# PhantomDriver_ER150D.net
KiCad netlist of a schematic drawn in EAGLE
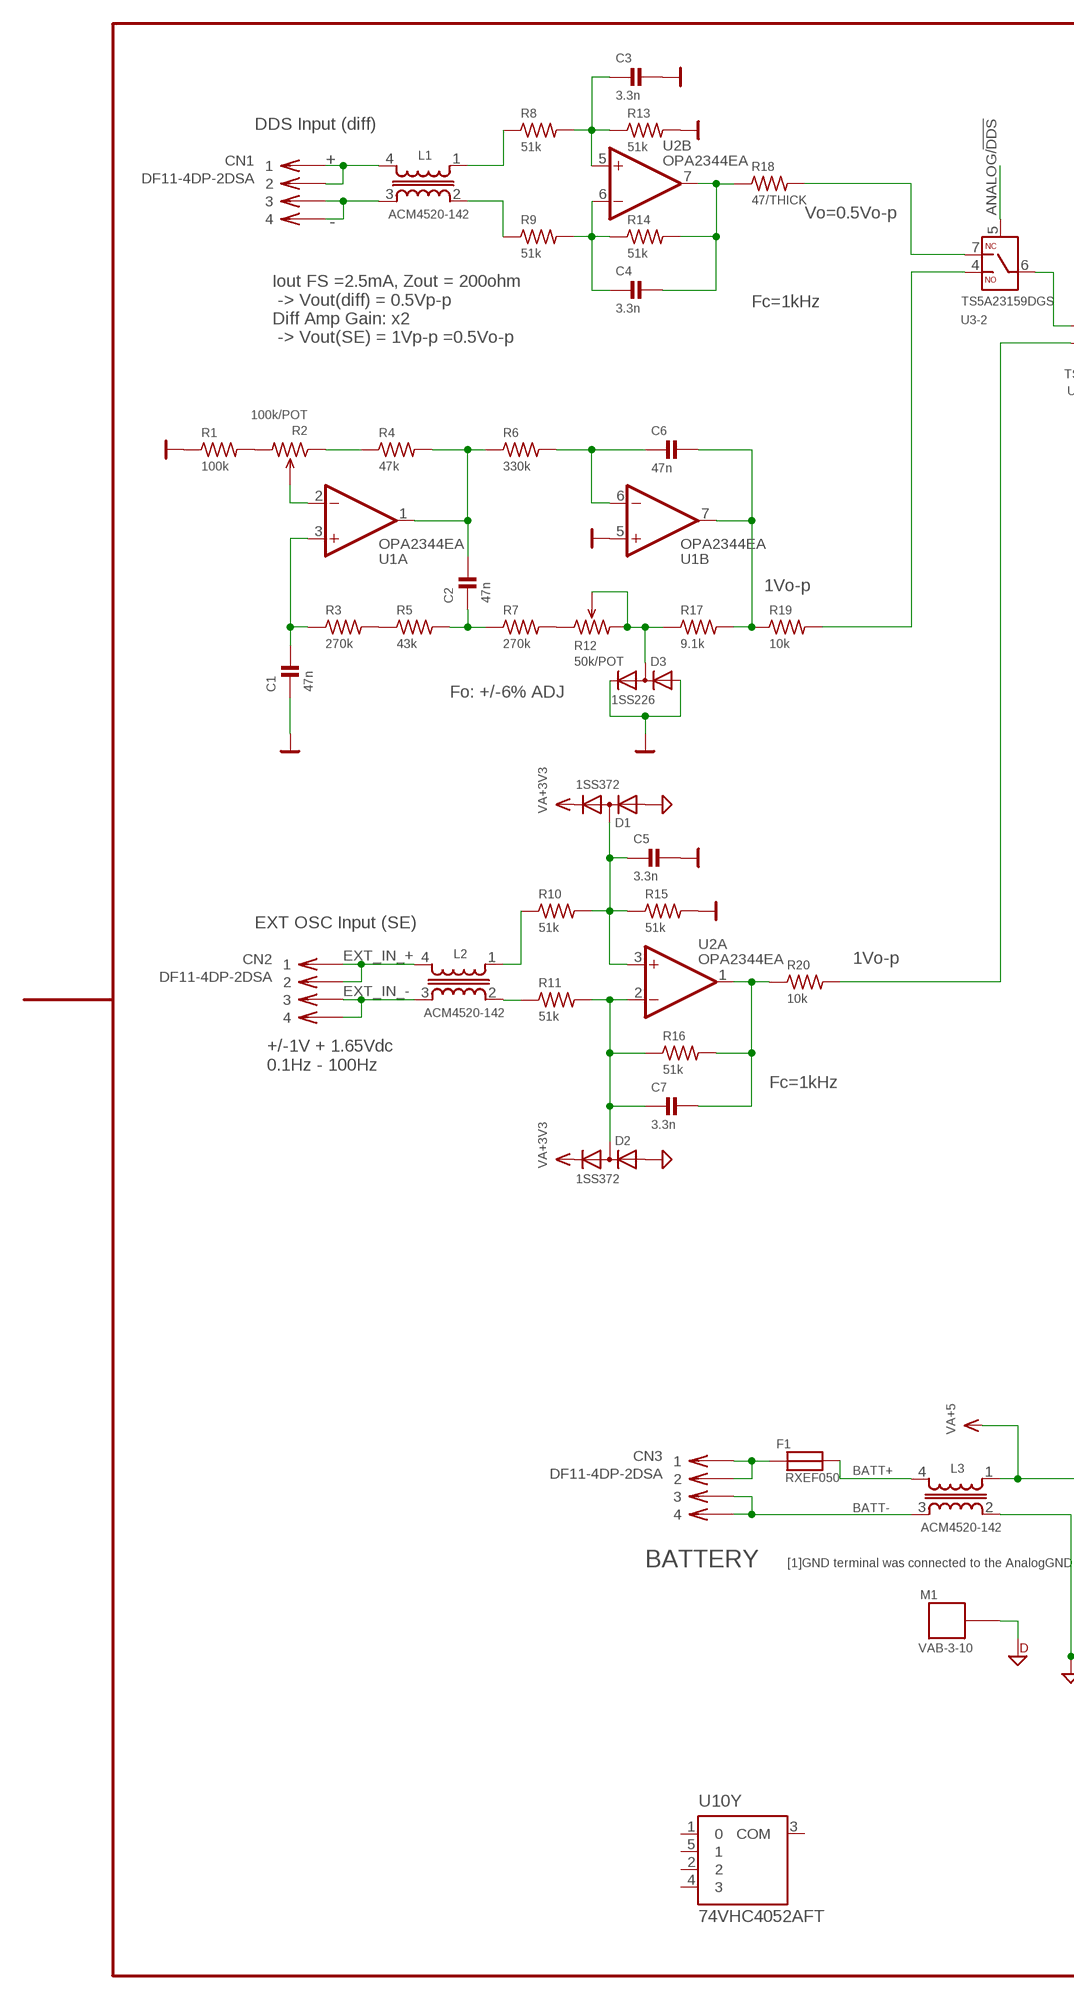
[diagram p0: schematic, sheet 1, part 1 of 2]
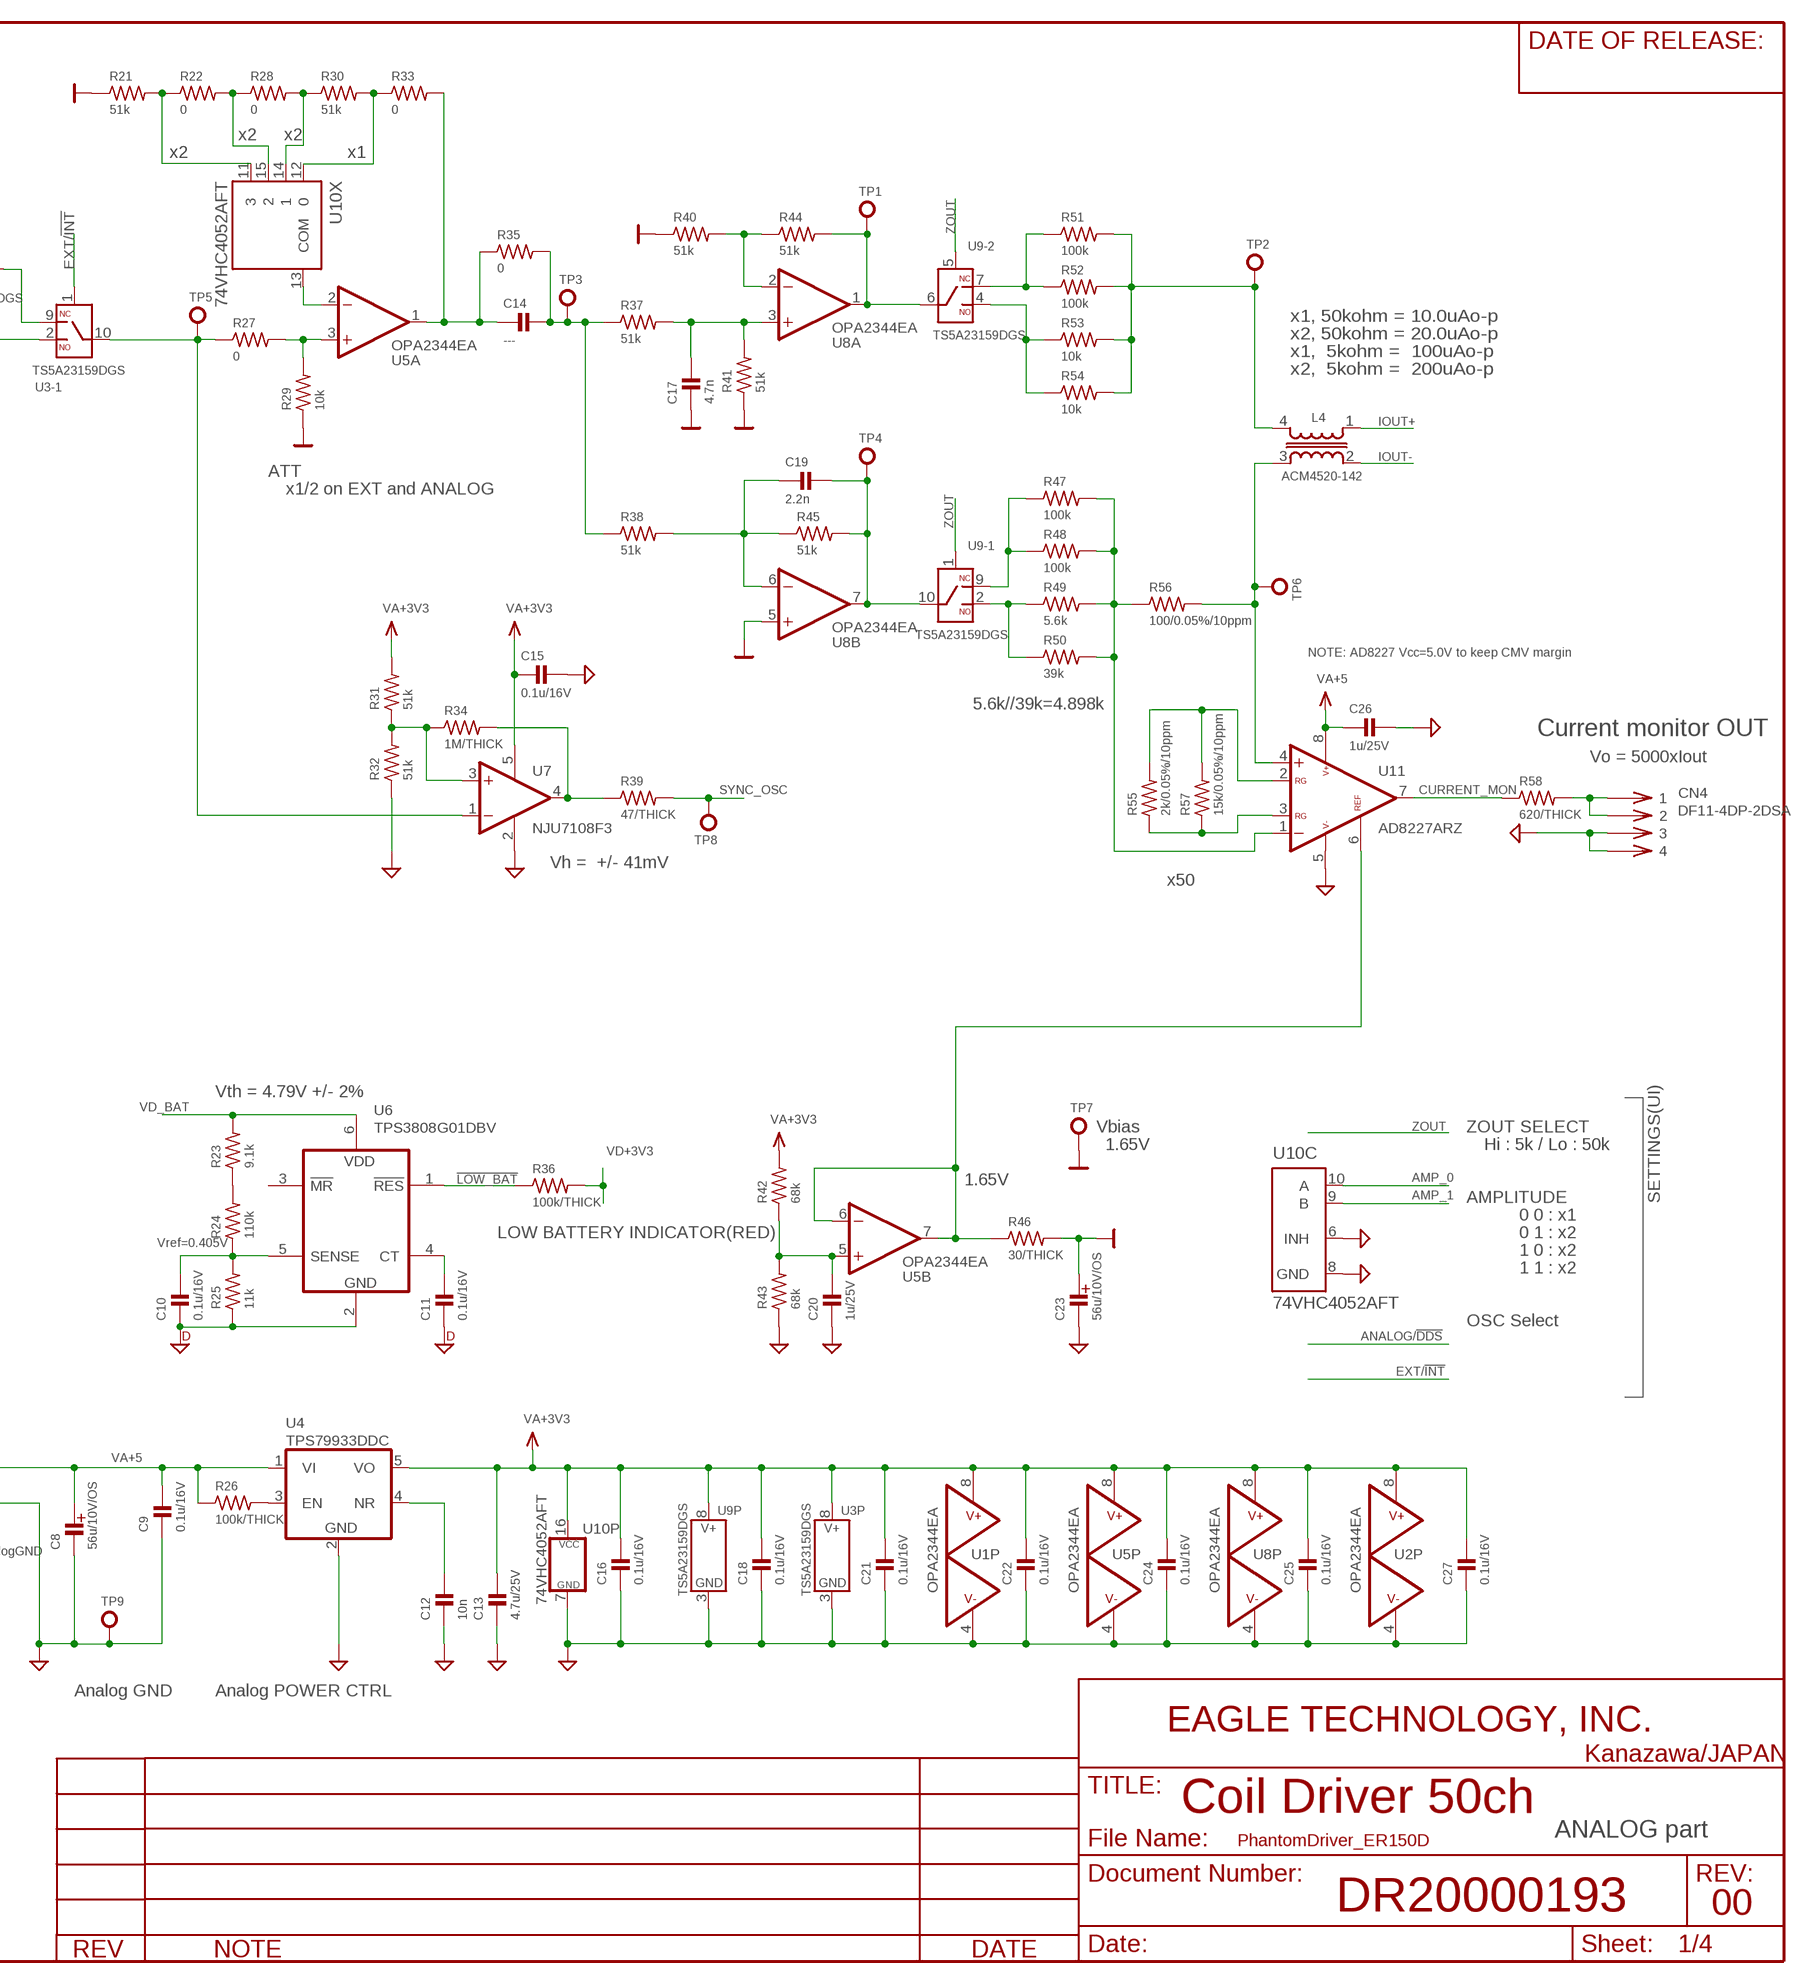
[diagram p1: schematic, sheet 1, part 2 of 2]
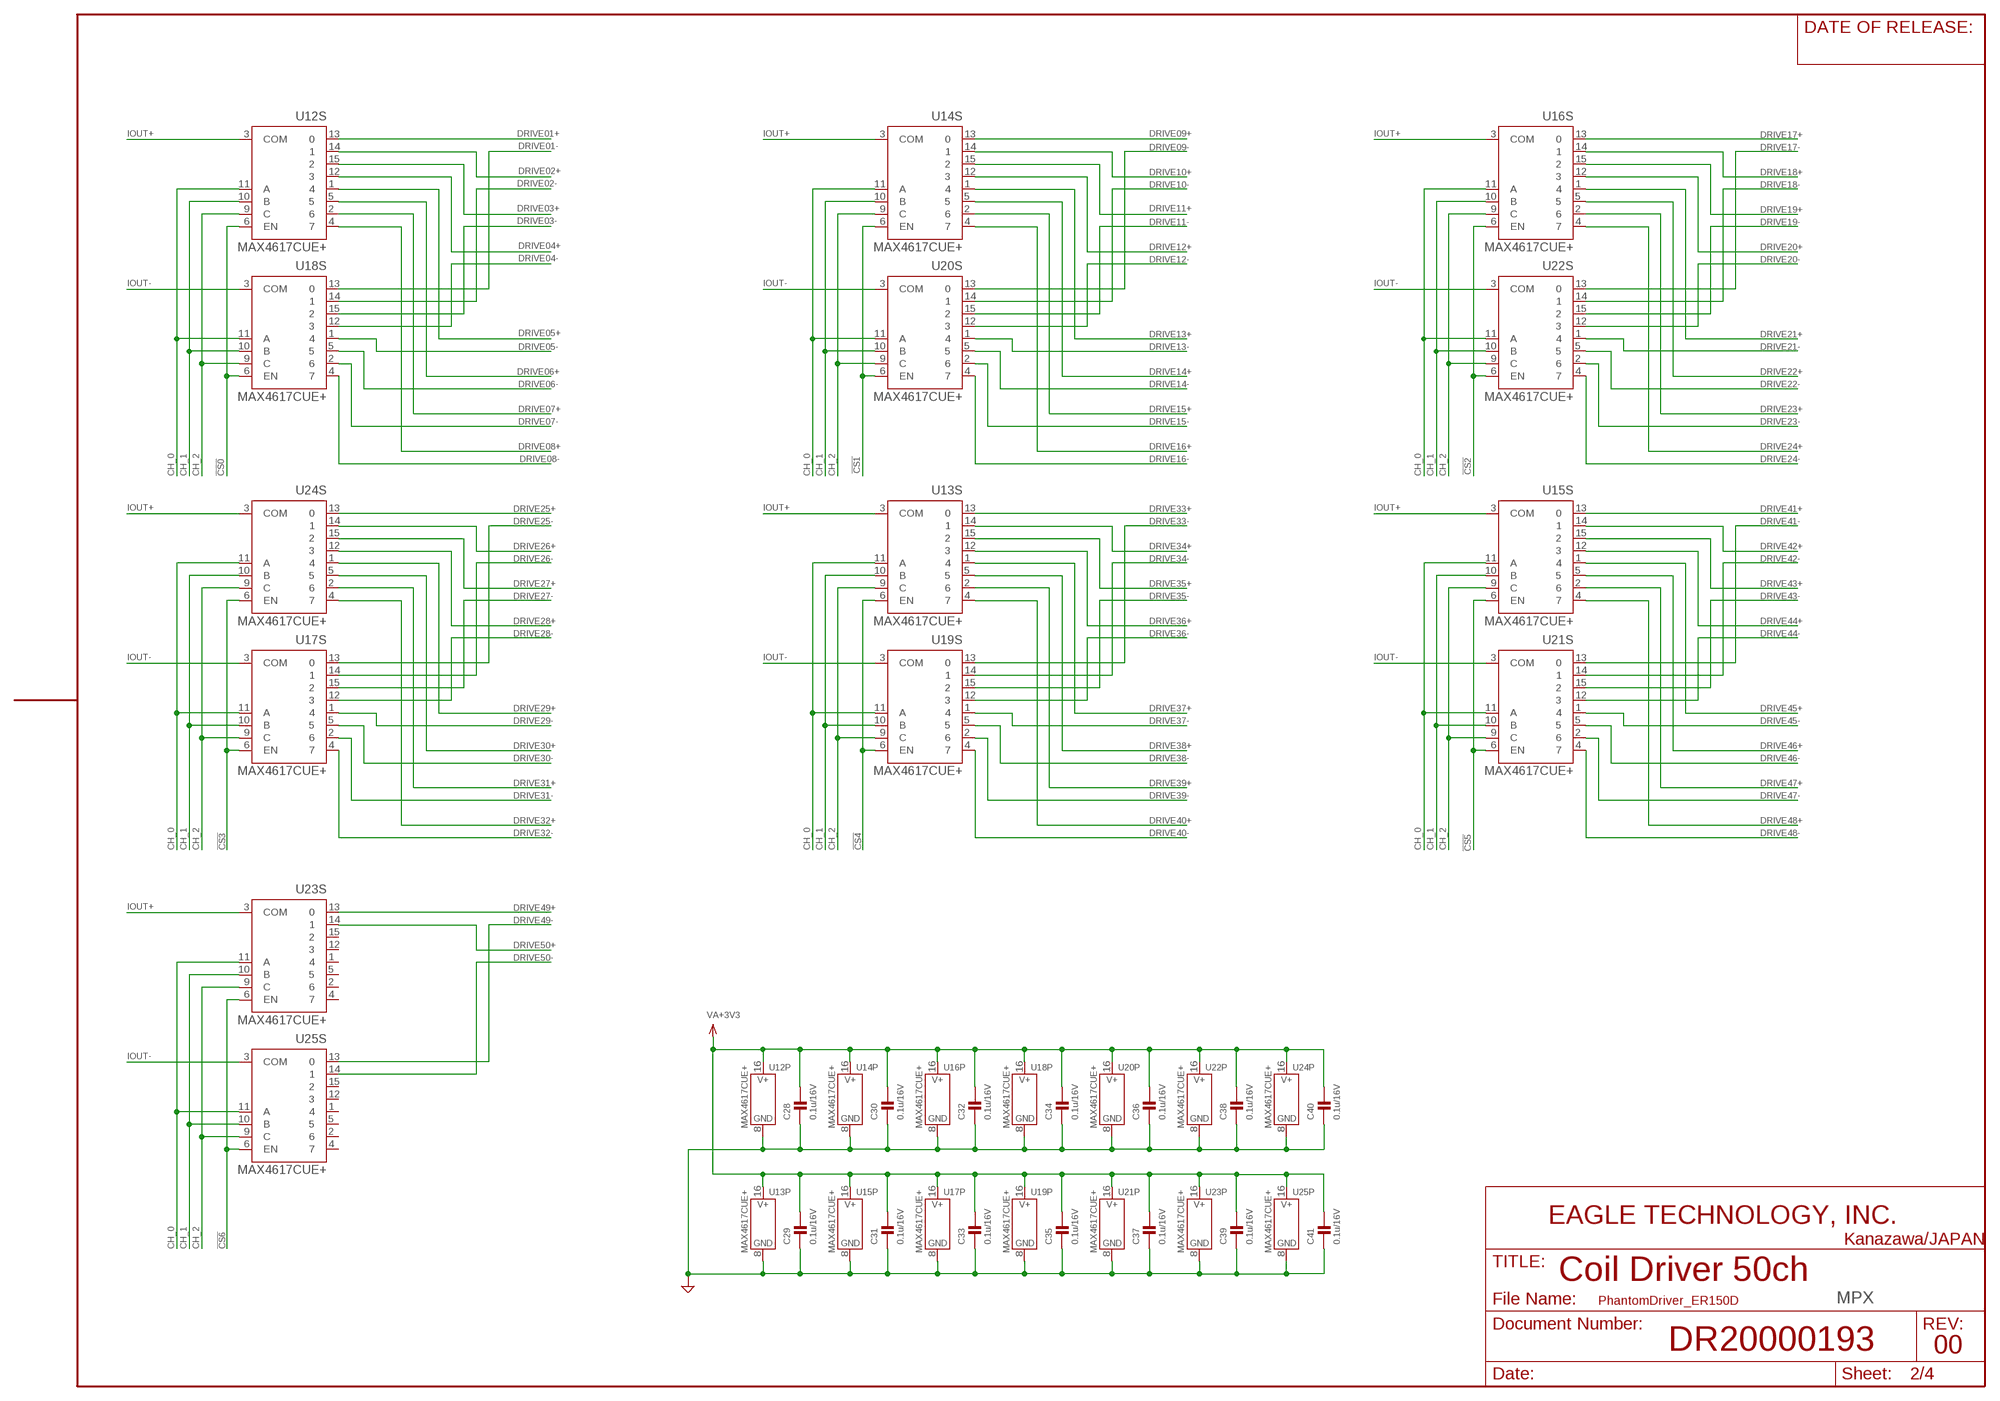
[diagram p2: schematic, sheet 2]
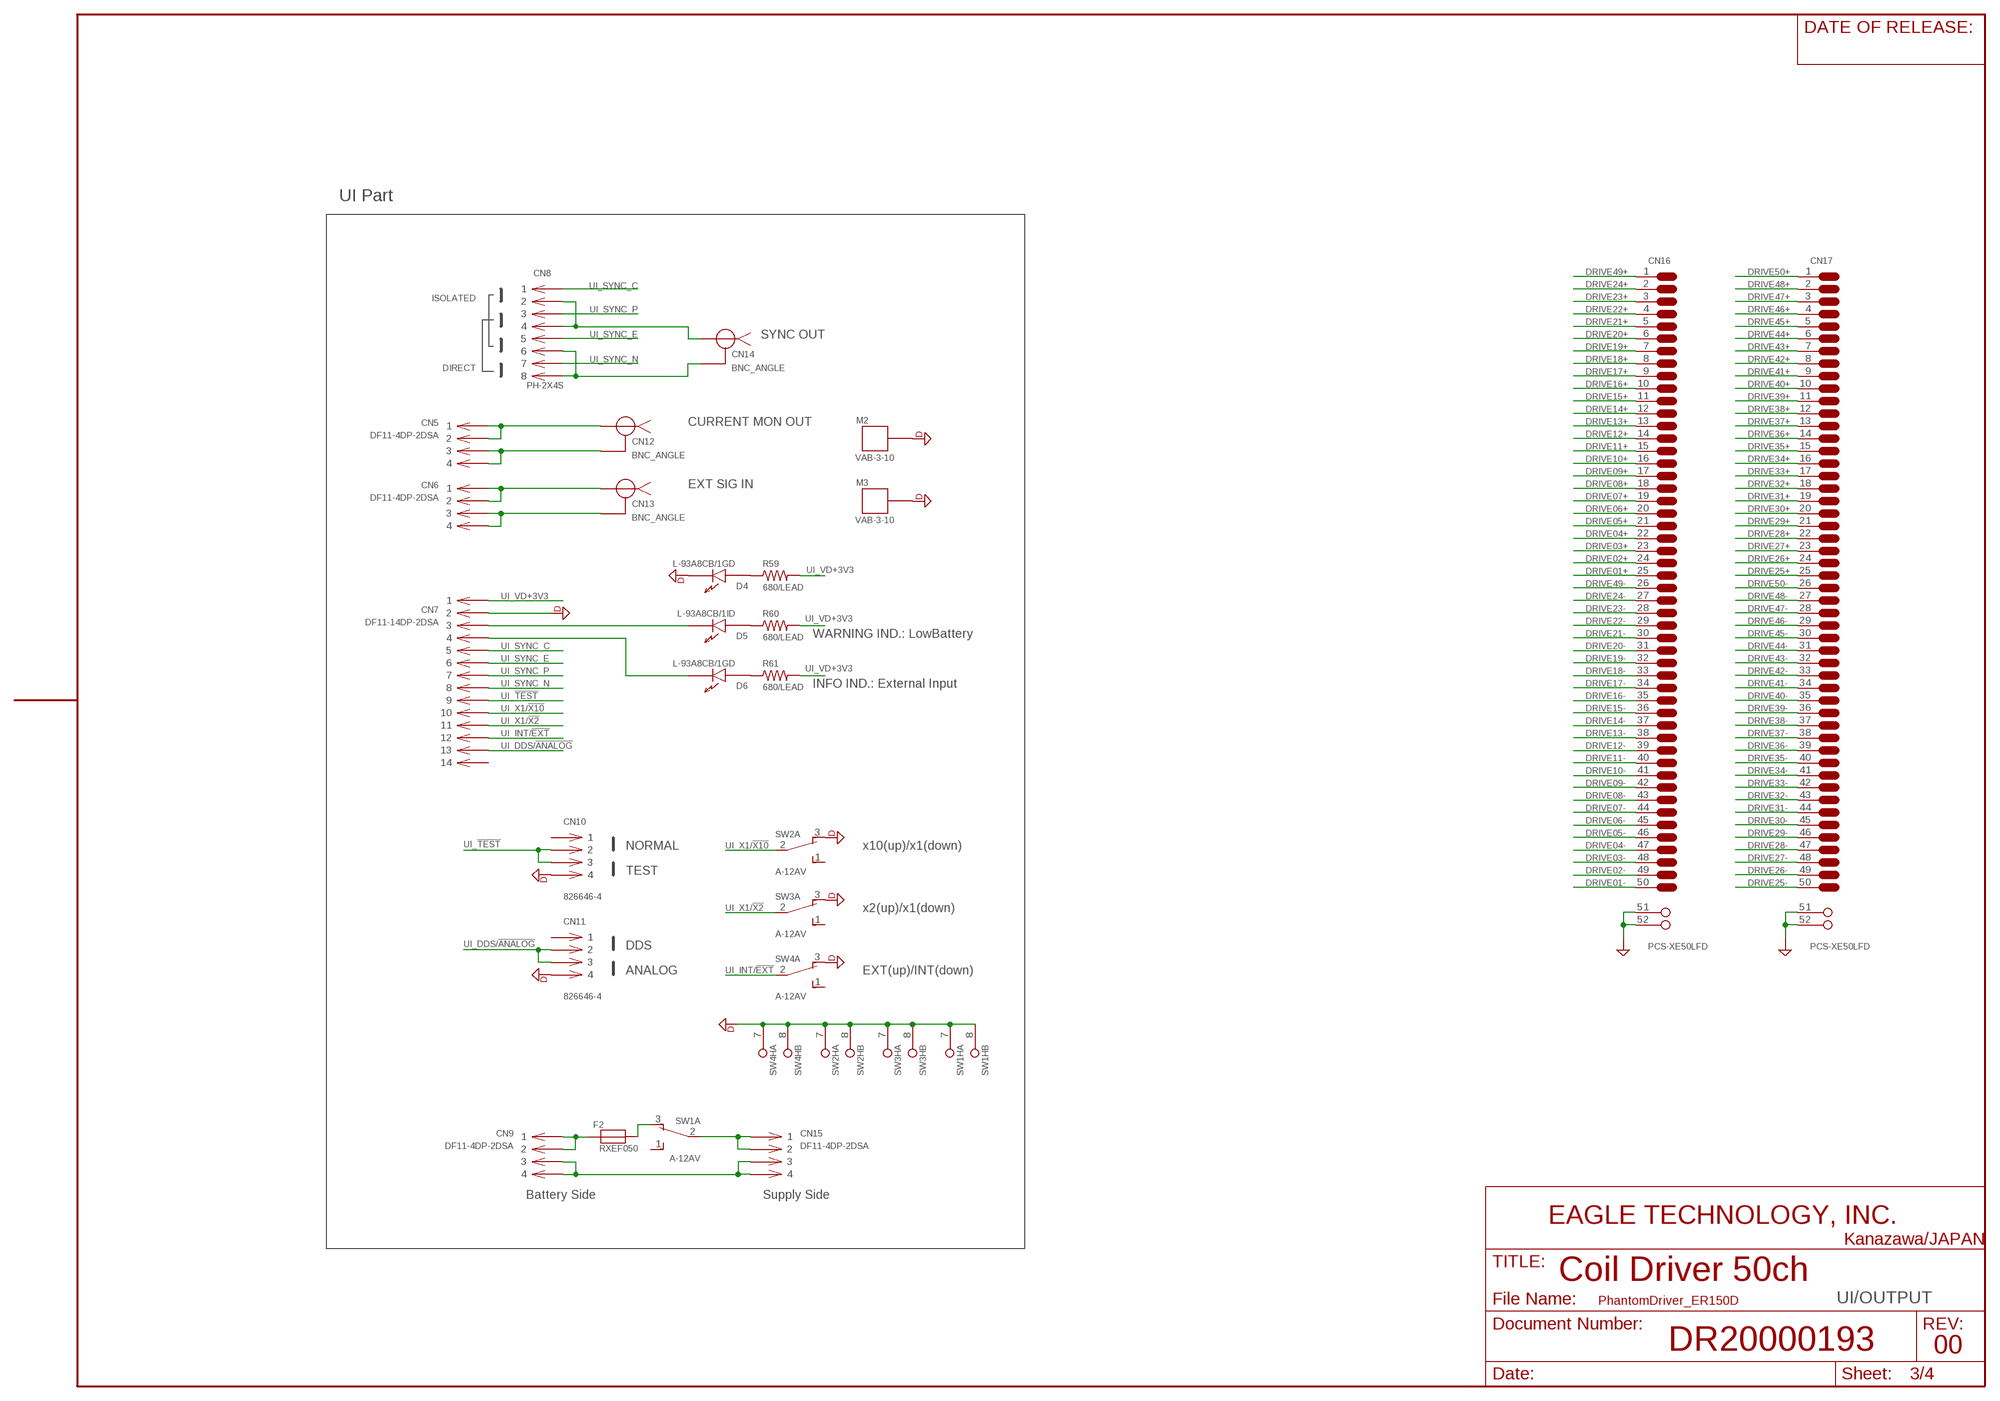
[diagram p3: schematic, sheet 3]
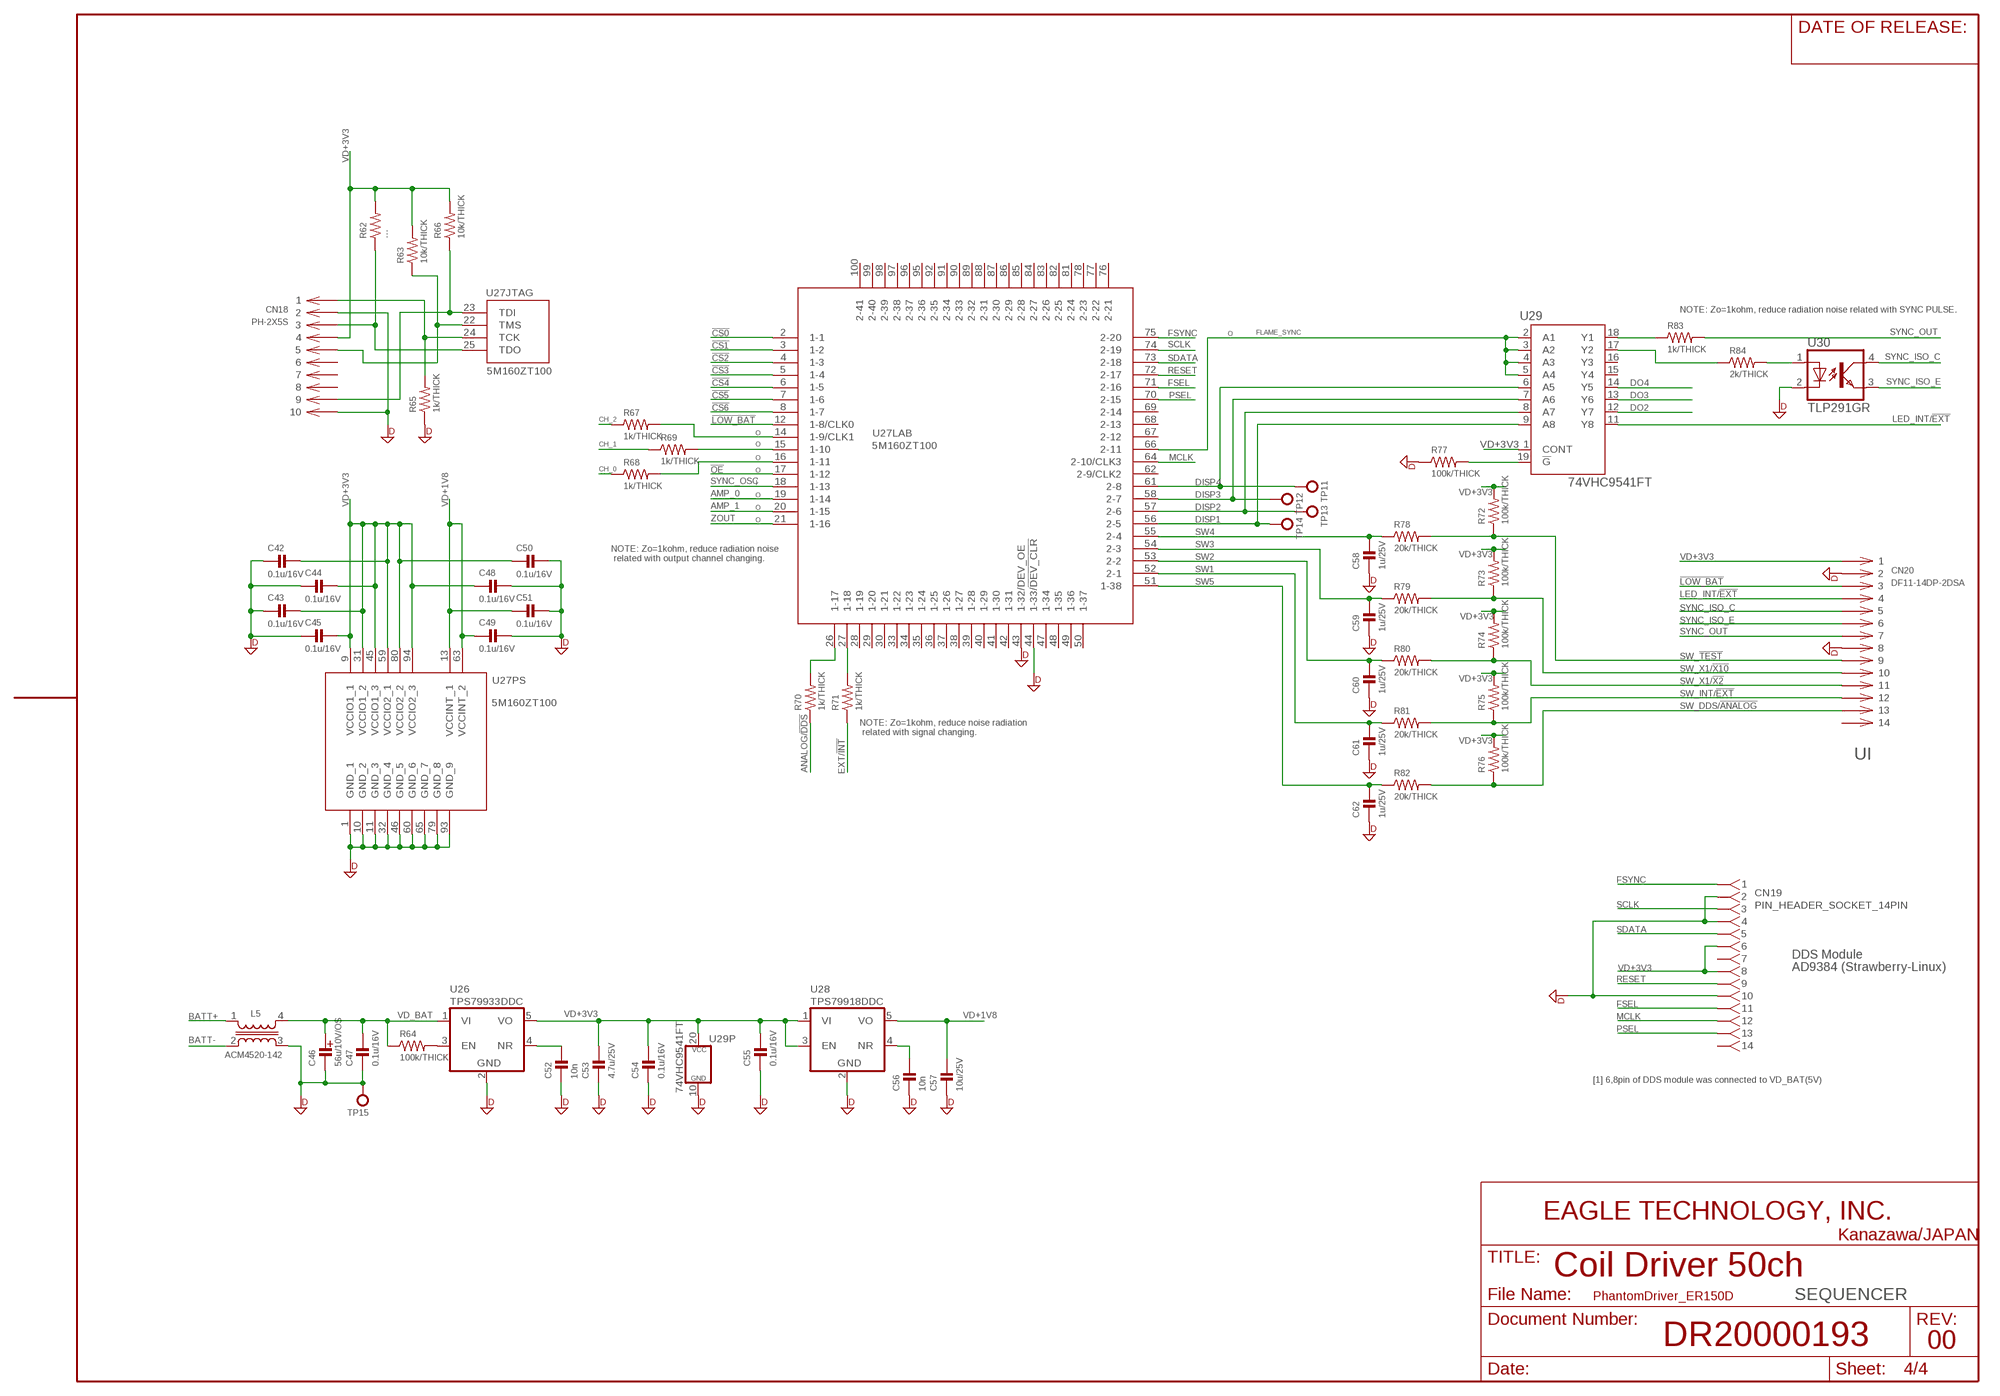
[diagram p4: schematic, sheet 4]

(export (version "E")
  (design (tool "Eeschema 10.0.6"))
  (components
    (comp (ref "C42")
      (value "0.1u/16V")
      (footprint "eagle-import:CM1005")
      (libsource (lib "eagle-import") (part "CSMD1.0X0.5MM"))
    )
    (comp (ref "C43")
      (value "0.1u/16V")
      (footprint "eagle-import:CM1005")
      (libsource (lib "eagle-import") (part "CSMD1.0X0.5MM"))
    )
    (comp (ref "C44")
      (value "0.1u/16V")
      (footprint "eagle-import:CM1005")
      (libsource (lib "eagle-import") (part "CSMD1.0X0.5MM"))
    )
    (comp (ref "C45")
      (value "0.1u/16V")
      (footprint "eagle-import:CM1005")
      (libsource (lib "eagle-import") (part "CSMD1.0X0.5MM"))
    )
    (comp (ref "C46")
      (value "56u/10V/OS")
      (footprint "eagle-import:PHI_6.3")
      (libsource (lib "eagle-import") (part "C_POL6.3-2.5MM"))
    )
    (comp (ref "C47")
      (value "0.1u/16V")
      (footprint "eagle-import:CM1005")
      (libsource (lib "eagle-import") (part "CSMD1.0X0.5MM"))
    )
    (comp (ref "C48")
      (value "0.1u/16V")
      (footprint "eagle-import:CM1005")
      (libsource (lib "eagle-import") (part "CSMD1.0X0.5MM"))
    )
    (comp (ref "C49")
      (value "0.1u/16V")
      (footprint "eagle-import:CM1005")
      (libsource (lib "eagle-import") (part "CSMD1.0X0.5MM"))
    )
    (comp (ref "C50")
      (value "0.1u/16V")
      (footprint "eagle-import:CM1005")
      (libsource (lib "eagle-import") (part "CSMD1.0X0.5MM"))
    )
    (comp (ref "C51")
      (value "0.1u/16V")
      (footprint "eagle-import:CM1005")
      (libsource (lib "eagle-import") (part "CSMD1.0X0.5MM"))
    )
    (comp (ref "C52")
      (value "10n")
      (footprint "eagle-import:CM2012")
      (libsource (lib "eagle-import") (part "CSMD2.0X1.2MM"))
    )
    (comp (ref "C53")
      (value "4.7u/25V")
      (footprint "eagle-import:CM2012")
      (libsource (lib "eagle-import") (part "CSMD2.0X1.2MM"))
    )
    (comp (ref "C54")
      (value "0.1u/16V")
      (footprint "eagle-import:CM1005")
      (libsource (lib "eagle-import") (part "CSMD1.0X0.5MM"))
    )
    (comp (ref "C55")
      (value "0.1u/16V")
      (footprint "eagle-import:CM1005")
      (libsource (lib "eagle-import") (part "CSMD1.0X0.5MM"))
    )
    (comp (ref "C56")
      (value "10n")
      (footprint "eagle-import:CM2012")
      (libsource (lib "eagle-import") (part "CSMD2.0X1.2MM"))
    )
    (comp (ref "C57")
      (value "10u/25V")
      (footprint "eagle-import:CM3216")
      (libsource (lib "eagle-import") (part "CSMD3.2X1.6MM"))
    )
    (comp (ref "C58")
      (value "1u/25V")
      (footprint "eagle-import:CM1608")
      (libsource (lib "eagle-import") (part "CSMD1.6X0.8MM"))
    )
    (comp (ref "C59")
      (value "1u/25V")
      (footprint "eagle-import:CM1608")
      (libsource (lib "eagle-import") (part "CSMD1.6X0.8MM"))
    )
    (comp (ref "C60")
      (value "1u/25V")
      (footprint "eagle-import:CM1608")
      (libsource (lib "eagle-import") (part "CSMD1.6X0.8MM"))
    )
    (comp (ref "C61")
      (value "1u/25V")
      (footprint "eagle-import:CM1608")
      (libsource (lib "eagle-import") (part "CSMD1.6X0.8MM"))
    )
    (comp (ref "C62")
      (value "1u/25V")
      (footprint "eagle-import:CM1608")
      (libsource (lib "eagle-import") (part "CSMD1.6X0.8MM"))
    )
    (comp (ref "CN18")
      (value "PH-2X5S")
      (footprint "eagle-import:PIN_HEADER_10PIN")
      (libsource (lib "eagle-import") (part "PIN_HEADER_10PIN"))
    )
    (comp (ref "CN19")
      (value "PIN_HEADER_SOCKET_14PIN")
      (footprint "eagle-import:PIN_HEADER_SOCKET_14PIN")
      (libsource (lib "eagle-import") (part "PIN_HEADER_SOCKET_14PIN"))
    )
    (comp (ref "CN20")
      (value "DF11-14DP-2DSA")
      (footprint "eagle-import:DF11-14DP-2DSA")
      (libsource (lib "eagle-import") (part "DF11-14DP-2DSA"))
    )
    (comp (ref "L5")
      (value "ACM4520-142")
      (footprint "eagle-import:ACM4520")
      (libsource (lib "eagle-import") (part "ACM4520-142"))
    )
    (comp (ref "R62")
      (value "---")
      (footprint "eagle-import:RM1608")
      (libsource (lib "eagle-import") (part "RSMD1.6X0.8MM"))
    )
    (comp (ref "R63")
      (value "10k/THICK")
      (footprint "eagle-import:RM1608")
      (libsource (lib "eagle-import") (part "RSMD1.6X0.8MM"))
    )
    (comp (ref "R64")
      (value "100k/THICK")
      (footprint "eagle-import:RM1608")
      (libsource (lib "eagle-import") (part "RSMD1.6X0.8MM"))
    )
    (comp (ref "R65")
      (value "1k/THICK")
      (footprint "eagle-import:RM1608")
      (libsource (lib "eagle-import") (part "RSMD1.6X0.8MM"))
    )
    (comp (ref "R66")
      (value "10k/THICK")
      (footprint "eagle-import:RM1608")
      (libsource (lib "eagle-import") (part "RSMD1.6X0.8MM"))
    )
    (comp (ref "R67")
      (value "1k/THICK")
      (footprint "eagle-import:RM1608")
      (libsource (lib "eagle-import") (part "RSMD1.6X0.8MM"))
    )
    (comp (ref "R68")
      (value "1k/THICK")
      (footprint "eagle-import:RM1608")
      (libsource (lib "eagle-import") (part "RSMD1.6X0.8MM"))
    )
    (comp (ref "R69")
      (value "1k/THICK")
      (footprint "eagle-import:RM1608")
      (libsource (lib "eagle-import") (part "RSMD1.6X0.8MM"))
    )
    (comp (ref "R70")
      (value "1k/THICK")
      (footprint "eagle-import:RM1608")
      (libsource (lib "eagle-import") (part "RSMD1.6X0.8MM"))
    )
    (comp (ref "R71")
      (value "1k/THICK")
      (footprint "eagle-import:RM1608")
      (libsource (lib "eagle-import") (part "RSMD1.6X0.8MM"))
    )
    (comp (ref "R72")
      (value "100k/THICK")
      (footprint "eagle-import:RM1608")
      (libsource (lib "eagle-import") (part "RSMD1.6X0.8MM"))
    )
    (comp (ref "R73")
      (value "100k/THICK")
      (footprint "eagle-import:RM1608")
      (libsource (lib "eagle-import") (part "RSMD1.6X0.8MM"))
    )
    (comp (ref "R74")
      (value "100k/THICK")
      (footprint "eagle-import:RM1608")
      (libsource (lib "eagle-import") (part "RSMD1.6X0.8MM"))
    )
    (comp (ref "R75")
      (value "100k/THICK")
      (footprint "eagle-import:RM1608")
      (libsource (lib "eagle-import") (part "RSMD1.6X0.8MM"))
    )
    (comp (ref "R76")
      (value "100k/THICK")
      (footprint "eagle-import:RM1608")
      (libsource (lib "eagle-import") (part "RSMD1.6X0.8MM"))
    )
    (comp (ref "R77")
      (value "100k/THICK")
      (footprint "eagle-import:RM1608")
      (libsource (lib "eagle-import") (part "RSMD1.6X0.8MM"))
    )
    (comp (ref "R78")
      (value "20k/THICK")
      (footprint "eagle-import:RM1608")
      (libsource (lib "eagle-import") (part "RSMD1.6X0.8MM"))
    )
    (comp (ref "R79")
      (value "20k/THICK")
      (footprint "eagle-import:RM1608")
      (libsource (lib "eagle-import") (part "RSMD1.6X0.8MM"))
    )
    (comp (ref "R80")
      (value "20k/THICK")
      (footprint "eagle-import:RM1608")
      (libsource (lib "eagle-import") (part "RSMD1.6X0.8MM"))
    )
    (comp (ref "R81")
      (value "20k/THICK")
      (footprint "eagle-import:RM1608")
      (libsource (lib "eagle-import") (part "RSMD1.6X0.8MM"))
    )
    (comp (ref "R82")
      (value "20k/THICK")
      (footprint "eagle-import:RM1608")
      (libsource (lib "eagle-import") (part "RSMD1.6X0.8MM"))
    )
    (comp (ref "R83")
      (value "1k/THICK")
      (footprint "eagle-import:RM1608")
      (libsource (lib "eagle-import") (part "RSMD1.6X0.8MM"))
    )
    (comp (ref "R84")
      (value "2k/THICK")
      (footprint "eagle-import:RM1608")
      (libsource (lib "eagle-import") (part "RSMD1.6X0.8MM"))
    )
    (comp (ref "TP11")
      (value "TP-1MMPAD")
      (footprint "eagle-import:TP_PAD_1MM")
      (libsource (lib "eagle-import") (part "TP-1MMPAD"))
    )
    (comp (ref "TP12")
      (value "TP-1MMPAD")
      (footprint "eagle-import:TP_PAD_1MM")
      (libsource (lib "eagle-import") (part "TP-1MMPAD"))
    )
    (comp (ref "TP13")
      (value "TP-1MMPAD")
      (footprint "eagle-import:TP_PAD_1MM")
      (libsource (lib "eagle-import") (part "TP-1MMPAD"))
    )
    (comp (ref "TP14")
      (value "TP-1MMPAD")
      (footprint "eagle-import:TP_PAD_1MM")
      (libsource (lib "eagle-import") (part "TP-1MMPAD"))
    )
    (comp (ref "TP15")
      (value "TP-LC3G")
      (footprint "eagle-import:TP_TH_0R9MM")
      (libsource (lib "eagle-import") (part "TP-LC3G"))
    )
    (comp (ref "U26")
      (value "TPS79933DDC")
      (footprint "eagle-import:SOT-23-5")
      (libsource (lib "eagle-import") (part "TPS799DDC33"))
    )
    (comp (ref "U27")
      (value "5M160ZT100")
      (footprint "eagle-import:QFP100_0.5")
      (libsource (lib "eagle-import") (part "5M160ZT100"))
    )
    (comp (ref "U28")
      (value "TPS79918DDC")
      (footprint "eagle-import:SOT-23-5")
      (libsource (lib "eagle-import") (part "TPS799DDC18"))
    )
    (comp (ref "U29")
      (value "74VHC9541FT")
      (footprint "eagle-import:TSSOP20-P-0044-065A")
      (libsource (lib "eagle-import") (part "749541FTVHC"))
    )
    (comp (ref "U30")
      (value "TLP291GR")
      (footprint "eagle-import:SO4(11-3C1)(TOSHIBA)")
      (libsource (lib "eagle-import") (part "TLP291GR"))
    )
    (comp (ref "C28")
      (value "0.1u/16V")
      (footprint "eagle-import:CM1005")
      (libsource (lib "eagle-import") (part "CSMD1.0X0.5MM"))
    )
    (comp (ref "C29")
      (value "0.1u/16V")
      (footprint "eagle-import:CM1005")
      (libsource (lib "eagle-import") (part "CSMD1.0X0.5MM"))
    )
    (comp (ref "C30")
      (value "0.1u/16V")
      (footprint "eagle-import:CM1005")
      (libsource (lib "eagle-import") (part "CSMD1.0X0.5MM"))
    )
    (comp (ref "C31")
      (value "0.1u/16V")
      (footprint "eagle-import:CM1005")
      (libsource (lib "eagle-import") (part "CSMD1.0X0.5MM"))
    )
    (comp (ref "C32")
      (value "0.1u/16V")
      (footprint "eagle-import:CM1005")
      (libsource (lib "eagle-import") (part "CSMD1.0X0.5MM"))
    )
    (comp (ref "C33")
      (value "0.1u/16V")
      (footprint "eagle-import:CM1005")
      (libsource (lib "eagle-import") (part "CSMD1.0X0.5MM"))
    )
    (comp (ref "C34")
      (value "0.1u/16V")
      (footprint "eagle-import:CM1005")
      (libsource (lib "eagle-import") (part "CSMD1.0X0.5MM"))
    )
    (comp (ref "C35")
      (value "0.1u/16V")
      (footprint "eagle-import:CM1005")
      (libsource (lib "eagle-import") (part "CSMD1.0X0.5MM"))
    )
    (comp (ref "C36")
      (value "0.1u/16V")
      (footprint "eagle-import:CM1005")
      (libsource (lib "eagle-import") (part "CSMD1.0X0.5MM"))
    )
    (comp (ref "C37")
      (value "0.1u/16V")
      (footprint "eagle-import:CM1005")
      (libsource (lib "eagle-import") (part "CSMD1.0X0.5MM"))
    )
    (comp (ref "C38")
      (value "0.1u/16V")
      (footprint "eagle-import:CM1005")
      (libsource (lib "eagle-import") (part "CSMD1.0X0.5MM"))
    )
    (comp (ref "C39")
      (value "0.1u/16V")
      (footprint "eagle-import:CM1005")
      (libsource (lib "eagle-import") (part "CSMD1.0X0.5MM"))
    )
    (comp (ref "C40")
      (value "0.1u/16V")
      (footprint "eagle-import:CM1005")
      (libsource (lib "eagle-import") (part "CSMD1.0X0.5MM"))
    )
    (comp (ref "C41")
      (value "0.1u/16V")
      (footprint "eagle-import:CM1005")
      (libsource (lib "eagle-import") (part "CSMD1.0X0.5MM"))
    )
    (comp (ref "U12")
      (value "MAX4617CUE+")
      (footprint "eagle-import:TSSOP16_AEL")
      (libsource (lib "eagle-import") (part "MAX4617CUE+"))
    )
    (comp (ref "U13")
      (value "MAX4617CUE+")
      (footprint "eagle-import:TSSOP16_AEL")
      (libsource (lib "eagle-import") (part "MAX4617CUE+"))
    )
    (comp (ref "U14")
      (value "MAX4617CUE+")
      (footprint "eagle-import:TSSOP16_AEL")
      (libsource (lib "eagle-import") (part "MAX4617CUE+"))
    )
    (comp (ref "U15")
      (value "MAX4617CUE+")
      (footprint "eagle-import:TSSOP16_AEL")
      (libsource (lib "eagle-import") (part "MAX4617CUE+"))
    )
    (comp (ref "U16")
      (value "MAX4617CUE+")
      (footprint "eagle-import:TSSOP16_AEL")
      (libsource (lib "eagle-import") (part "MAX4617CUE+"))
    )
    (comp (ref "U17")
      (value "MAX4617CUE+")
      (footprint "eagle-import:TSSOP16_AEL")
      (libsource (lib "eagle-import") (part "MAX4617CUE+"))
    )
    (comp (ref "U18")
      (value "MAX4617CUE+")
      (footprint "eagle-import:TSSOP16_AEL")
      (libsource (lib "eagle-import") (part "MAX4617CUE+"))
    )
    (comp (ref "U19")
      (value "MAX4617CUE+")
      (footprint "eagle-import:TSSOP16_AEL")
      (libsource (lib "eagle-import") (part "MAX4617CUE+"))
    )
    (comp (ref "U20")
      (value "MAX4617CUE+")
      (footprint "eagle-import:TSSOP16_AEL")
      (libsource (lib "eagle-import") (part "MAX4617CUE+"))
    )
    (comp (ref "U21")
      (value "MAX4617CUE+")
      (footprint "eagle-import:TSSOP16_AEL")
      (libsource (lib "eagle-import") (part "MAX4617CUE+"))
    )
    (comp (ref "U22")
      (value "MAX4617CUE+")
      (footprint "eagle-import:TSSOP16_AEL")
      (libsource (lib "eagle-import") (part "MAX4617CUE+"))
    )
    (comp (ref "U23")
      (value "MAX4617CUE+")
      (footprint "eagle-import:TSSOP16_AEL")
      (libsource (lib "eagle-import") (part "MAX4617CUE+"))
    )
    (comp (ref "U24")
      (value "MAX4617CUE+")
      (footprint "eagle-import:TSSOP16_AEL")
      (libsource (lib "eagle-import") (part "MAX4617CUE+"))
    )
    (comp (ref "U25")
      (value "MAX4617CUE+")
      (footprint "eagle-import:TSSOP16_AEL")
      (libsource (lib "eagle-import") (part "MAX4617CUE+"))
    )
    (comp (ref "C1")
      (value "47n")
      (footprint "eagle-import:CM3216")
      (libsource (lib "eagle-import") (part "CSMD3.2X1.6MM"))
    )
    (comp (ref "C2")
      (value "47n")
      (footprint "eagle-import:CM3216")
      (libsource (lib "eagle-import") (part "CSMD3.2X1.6MM"))
    )
    (comp (ref "C3")
      (value "3.3n")
      (footprint "eagle-import:CM2012")
      (libsource (lib "eagle-import") (part "CSMD2.0X1.2MM"))
    )
    (comp (ref "C4")
      (value "3.3n")
      (footprint "eagle-import:CM2012")
      (libsource (lib "eagle-import") (part "CSMD2.0X1.2MM"))
    )
    (comp (ref "C5")
      (value "3.3n")
      (footprint "eagle-import:CM2012")
      (libsource (lib "eagle-import") (part "CSMD2.0X1.2MM"))
    )
    (comp (ref "C6")
      (value "47n")
      (footprint "eagle-import:CM3216")
      (libsource (lib "eagle-import") (part "CSMD3.2X1.6MM"))
    )
    (comp (ref "C7")
      (value "3.3n")
      (footprint "eagle-import:CM2012")
      (libsource (lib "eagle-import") (part "CSMD2.0X1.2MM"))
    )
    (comp (ref "C8")
      (value "56u/10V/OS")
      (footprint "eagle-import:PHI_6.3")
      (libsource (lib "eagle-import") (part "C_POL6.3-2.5MM"))
    )
    (comp (ref "C9")
      (value "0.1u/16V")
      (footprint "eagle-import:CM1005")
      (libsource (lib "eagle-import") (part "CSMD1.0X0.5MM"))
    )
    (comp (ref "C10")
      (value "0.1u/16V")
      (footprint "eagle-import:CM1005")
      (libsource (lib "eagle-import") (part "CSMD1.0X0.5MM"))
    )
    (comp (ref "C11")
      (value "0.1u/16V")
      (footprint "eagle-import:CM1005")
      (libsource (lib "eagle-import") (part "CSMD1.0X0.5MM"))
    )
    (comp (ref "C12")
      (value "10n")
      (footprint "eagle-import:CM2012")
      (libsource (lib "eagle-import") (part "CSMD2.0X1.2MM"))
    )
    (comp (ref "C13")
      (value "4.7u/25V")
      (footprint "eagle-import:CM2012")
      (libsource (lib "eagle-import") (part "CSMD2.0X1.2MM"))
    )
    (comp (ref "C14")
      (value "---")
      (footprint "eagle-import:CM3216")
      (libsource (lib "eagle-import") (part "CSMD3.2X1.6MM"))
    )
    (comp (ref "C15")
      (value "0.1u/16V")
      (footprint "eagle-import:CM1005")
      (libsource (lib "eagle-import") (part "CSMD1.0X0.5MM"))
    )
    (comp (ref "C16")
      (value "0.1u/16V")
      (footprint "eagle-import:CM1005")
      (libsource (lib "eagle-import") (part "CSMD1.0X0.5MM"))
    )
    (comp (ref "C17")
      (value "4.7n")
      (footprint "eagle-import:CM2012")
      (libsource (lib "eagle-import") (part "CSMD2.0X1.2MM"))
    )
    (comp (ref "C18")
      (value "0.1u/16V")
      (footprint "eagle-import:CM1005")
      (libsource (lib "eagle-import") (part "CSMD1.0X0.5MM"))
    )
    (comp (ref "C19")
      (value "2.2n")
      (footprint "eagle-import:CM2012")
      (libsource (lib "eagle-import") (part "CSMD2.0X1.2MM"))
    )
    (comp (ref "C20")
      (value "1u/25V")
      (footprint "eagle-import:CM1608")
      (libsource (lib "eagle-import") (part "CSMD1.6X0.8MM"))
    )
    (comp (ref "C21")
      (value "0.1u/16V")
      (footprint "eagle-import:CM1005")
      (libsource (lib "eagle-import") (part "CSMD1.0X0.5MM"))
    )
    (comp (ref "C22")
      (value "0.1u/16V")
      (footprint "eagle-import:CM1005")
      (libsource (lib "eagle-import") (part "CSMD1.0X0.5MM"))
    )
    (comp (ref "C23")
      (value "56u/10V/OS")
      (footprint "eagle-import:PHI_6.3")
      (libsource (lib "eagle-import") (part "C_POL6.3-2.5MM"))
    )
    (comp (ref "C24")
      (value "0.1u/16V")
      (footprint "eagle-import:CM1005")
      (libsource (lib "eagle-import") (part "CSMD1.0X0.5MM"))
    )
    (comp (ref "C25")
      (value "0.1u/16V")
      (footprint "eagle-import:CM1005")
      (libsource (lib "eagle-import") (part "CSMD1.0X0.5MM"))
    )
    (comp (ref "C26")
      (value "1u/25V")
      (footprint "eagle-import:CM1608")
      (libsource (lib "eagle-import") (part "CSMD1.6X0.8MM"))
    )
    (comp (ref "C27")
      (value "0.1u/16V")
      (footprint "eagle-import:CM1005")
      (libsource (lib "eagle-import") (part "CSMD1.0X0.5MM"))
    )
    (comp (ref "CN1")
      (value "DF11-4DP-2DSA")
      (footprint "eagle-import:DF11-4DP-2DSA")
      (libsource (lib "eagle-import") (part "DF11-4DP-2DSA"))
    )
    (comp (ref "CN2")
      (value "DF11-4DP-2DSA")
      (footprint "eagle-import:DF11-4DP-2DSA")
      (libsource (lib "eagle-import") (part "DF11-4DP-2DSA"))
    )
    (comp (ref "CN3")
      (value "DF11-4DP-2DSA")
      (footprint "eagle-import:DF11-4DP-2DSA")
      (libsource (lib "eagle-import") (part "DF11-4DP-2DSA"))
    )
    (comp (ref "CN4")
      (value "DF11-4DP-2DSA")
      (footprint "eagle-import:DF11-4DP-2DSA")
      (libsource (lib "eagle-import") (part "DF11-4DP-2DSA"))
    )
    (comp (ref "D1")
      (value "1SS372")
      (footprint "eagle-import:SC70-3-R")
      (libsource (lib "eagle-import") (part "1SS372"))
    )
    (comp (ref "D2")
      (value "1SS372")
      (footprint "eagle-import:SC70-3-R")
      (libsource (lib "eagle-import") (part "1SS372"))
    )
    (comp (ref "D3")
      (value "1SS226")
      (footprint "eagle-import:SOT23")
      (libsource (lib "eagle-import") (part "1SS226"))
    )
    (comp (ref "F1")
      (value "RXEF050")
      (footprint "eagle-import:8X3_5.08")
      (libsource (lib "eagle-import") (part "RXEF050"))
    )
    (comp (ref "L1")
      (value "ACM4520-142")
      (footprint "eagle-import:ACM4520")
      (libsource (lib "eagle-import") (part "ACM4520-142"))
    )
    (comp (ref "L2")
      (value "ACM4520-142")
      (footprint "eagle-import:ACM4520")
      (libsource (lib "eagle-import") (part "ACM4520-142"))
    )
    (comp (ref "L3")
      (value "ACM4520-142")
      (footprint "eagle-import:ACM4520")
      (libsource (lib "eagle-import") (part "ACM4520-142"))
    )
    (comp (ref "L4")
      (value "ACM4520-142")
      (footprint "eagle-import:ACM4520")
      (libsource (lib "eagle-import") (part "ACM4520-142"))
    )
    (comp (ref "M1")
      (value "VAB-3-10")
      (footprint "eagle-import:VAB_3_10_CONTACT")
      (libsource (lib "eagle-import") (part "VAB-3-10"))
    )
    (comp (ref "R1")
      (value "100k")
      (footprint "eagle-import:RM1608")
      (libsource (lib "eagle-import") (part "RSMD1.6X0.8MM"))
    )
    (comp (ref "R2")
      (value "100k/POT")
      (footprint "eagle-import:CT-6")
      (libsource (lib "eagle-import") (part "R_POT"))
    )
    (comp (ref "R3")
      (value "270k")
      (footprint "eagle-import:RM1608")
      (libsource (lib "eagle-import") (part "RSMD1.6X0.8MM"))
    )
    (comp (ref "R4")
      (value "47k")
      (footprint "eagle-import:RM1608")
      (libsource (lib "eagle-import") (part "RSMD1.6X0.8MM"))
    )
    (comp (ref "R5")
      (value "43k")
      (footprint "eagle-import:RM1608")
      (libsource (lib "eagle-import") (part "RSMD1.6X0.8MM"))
    )
    (comp (ref "R6")
      (value "330k")
      (footprint "eagle-import:RM1608")
      (libsource (lib "eagle-import") (part "RSMD1.6X0.8MM"))
    )
    (comp (ref "R7")
      (value "270k")
      (footprint "eagle-import:RM1608")
      (libsource (lib "eagle-import") (part "RSMD1.6X0.8MM"))
    )
    (comp (ref "R8")
      (value "51k")
      (footprint "eagle-import:RM1608")
      (libsource (lib "eagle-import") (part "RSMD1.6X0.8MM"))
    )
    (comp (ref "R9")
      (value "51k")
      (footprint "eagle-import:RM1608")
      (libsource (lib "eagle-import") (part "RSMD1.6X0.8MM"))
    )
    (comp (ref "R10")
      (value "51k")
      (footprint "eagle-import:RM1608")
      (libsource (lib "eagle-import") (part "RSMD1.6X0.8MM"))
    )
    (comp (ref "R11")
      (value "51k")
      (footprint "eagle-import:RM1608")
      (libsource (lib "eagle-import") (part "RSMD1.6X0.8MM"))
    )
    (comp (ref "R12")
      (value "50k/POT")
      (footprint "eagle-import:CT-6")
      (libsource (lib "eagle-import") (part "R_POT"))
    )
    (comp (ref "R13")
      (value "51k")
      (footprint "eagle-import:RM1608")
      (libsource (lib "eagle-import") (part "RSMD1.6X0.8MM"))
    )
    (comp (ref "R14")
      (value "51k")
      (footprint "eagle-import:RM1608")
      (libsource (lib "eagle-import") (part "RSMD1.6X0.8MM"))
    )
    (comp (ref "R15")
      (value "51k")
      (footprint "eagle-import:RM1608")
      (libsource (lib "eagle-import") (part "RSMD1.6X0.8MM"))
    )
    (comp (ref "R16")
      (value "51k")
      (footprint "eagle-import:RM1608")
      (libsource (lib "eagle-import") (part "RSMD1.6X0.8MM"))
    )
    (comp (ref "R17")
      (value "9.1k")
      (footprint "eagle-import:RM1608")
      (libsource (lib "eagle-import") (part "RSMD1.6X0.8MM"))
    )
    (comp (ref "R18")
      (value "47/THICK")
      (footprint "eagle-import:RM1608")
      (libsource (lib "eagle-import") (part "RSMD1.6X0.8MM"))
    )
    (comp (ref "R19")
      (value "10k")
      (footprint "eagle-import:RM1608")
      (libsource (lib "eagle-import") (part "RSMD1.6X0.8MM"))
    )
    (comp (ref "R20")
      (value "10k")
      (footprint "eagle-import:RM1608")
      (libsource (lib "eagle-import") (part "RSMD1.6X0.8MM"))
    )
    (comp (ref "R21")
      (value "51k")
      (footprint "eagle-import:RM1608")
      (libsource (lib "eagle-import") (part "RSMD1.6X0.8MM"))
    )
    (comp (ref "R22")
      (value "0")
      (footprint "eagle-import:RM1608")
      (libsource (lib "eagle-import") (part "RSMD1.6X0.8MM"))
    )
    (comp (ref "R23")
      (value "9.1k")
      (footprint "eagle-import:RM1608")
      (libsource (lib "eagle-import") (part "RSMD1.6X0.8MM"))
    )
    (comp (ref "R24")
      (value "110k")
      (footprint "eagle-import:RM1608")
      (libsource (lib "eagle-import") (part "RSMD1.6X0.8MM"))
    )
    (comp (ref "R25")
      (value "11k")
      (footprint "eagle-import:RM1608")
      (libsource (lib "eagle-import") (part "RSMD1.6X0.8MM"))
    )
    (comp (ref "R26")
      (value "100k/THICK")
      (footprint "eagle-import:RM1608")
      (libsource (lib "eagle-import") (part "RSMD1.6X0.8MM"))
    )
    (comp (ref "R27")
      (value "0")
      (footprint "eagle-import:RM1608")
      (libsource (lib "eagle-import") (part "RSMD1.6X0.8MM"))
    )
    (comp (ref "R28")
      (value "0")
      (footprint "eagle-import:RM1608")
      (libsource (lib "eagle-import") (part "RSMD1.6X0.8MM"))
    )
    (comp (ref "R29")
      (value "10k")
      (footprint "eagle-import:RM1608")
      (libsource (lib "eagle-import") (part "RSMD1.6X0.8MM"))
    )
    (comp (ref "R30")
      (value "51k")
      (footprint "eagle-import:RM1608")
      (libsource (lib "eagle-import") (part "RSMD1.6X0.8MM"))
    )
    (comp (ref "R31")
      (value "51k")
      (footprint "eagle-import:RM1608")
      (libsource (lib "eagle-import") (part "RSMD1.6X0.8MM"))
    )
    (comp (ref "R32")
      (value "51k")
      (footprint "eagle-import:RM1608")
      (libsource (lib "eagle-import") (part "RSMD1.6X0.8MM"))
    )
    (comp (ref "R33")
      (value "0")
      (footprint "eagle-import:RM1608")
      (libsource (lib "eagle-import") (part "RSMD1.6X0.8MM"))
    )
    (comp (ref "R34")
      (value "1M/THICK")
      (footprint "eagle-import:RM1608")
      (libsource (lib "eagle-import") (part "RSMD1.6X0.8MM"))
    )
    (comp (ref "R35")
      (value "0")
      (footprint "eagle-import:RM1608")
      (libsource (lib "eagle-import") (part "RSMD1.6X0.8MM"))
    )
    (comp (ref "R36")
      (value "100k/THICK")
      (footprint "eagle-import:RM1608")
      (libsource (lib "eagle-import") (part "RSMD1.6X0.8MM"))
    )
    (comp (ref "R37")
      (value "51k")
      (footprint "eagle-import:RM1608")
      (libsource (lib "eagle-import") (part "RSMD1.6X0.8MM"))
    )
    (comp (ref "R38")
      (value "51k")
      (footprint "eagle-import:RM1608")
      (libsource (lib "eagle-import") (part "RSMD1.6X0.8MM"))
    )
    (comp (ref "R39")
      (value "47/THICK")
      (footprint "eagle-import:RM1608")
      (libsource (lib "eagle-import") (part "RSMD1.6X0.8MM"))
    )
    (comp (ref "R40")
      (value "51k")
      (footprint "eagle-import:RM1608")
      (libsource (lib "eagle-import") (part "RSMD1.6X0.8MM"))
    )
    (comp (ref "R41")
      (value "51k")
      (footprint "eagle-import:RM1608")
      (libsource (lib "eagle-import") (part "RSMD1.6X0.8MM"))
    )
    (comp (ref "R42")
      (value "68k")
      (footprint "eagle-import:RM1608")
      (libsource (lib "eagle-import") (part "RSMD1.6X0.8MM"))
    )
    (comp (ref "R43")
      (value "68k")
      (footprint "eagle-import:RM1608")
      (libsource (lib "eagle-import") (part "RSMD1.6X0.8MM"))
    )
    (comp (ref "R44")
      (value "51k")
      (footprint "eagle-import:RM1608")
      (libsource (lib "eagle-import") (part "RSMD1.6X0.8MM"))
    )
    (comp (ref "R45")
      (value "51k")
      (footprint "eagle-import:RM1608")
      (libsource (lib "eagle-import") (part "RSMD1.6X0.8MM"))
    )
    (comp (ref "R46")
      (value "30/THICK")
      (footprint "eagle-import:RM1608")
      (libsource (lib "eagle-import") (part "RSMD1.6X0.8MM"))
    )
    (comp (ref "R47")
      (value "100k")
      (footprint "eagle-import:RM1608")
      (libsource (lib "eagle-import") (part "RSMD1.6X0.8MM"))
    )
    (comp (ref "R48")
      (value "100k")
      (footprint "eagle-import:RM1608")
      (libsource (lib "eagle-import") (part "RSMD1.6X0.8MM"))
    )
    (comp (ref "R49")
      (value "5.6k")
      (footprint "eagle-import:RM1608")
      (libsource (lib "eagle-import") (part "RSMD1.6X0.8MM"))
    )
    (comp (ref "R50")
      (value "39k")
      (footprint "eagle-import:RM1608")
      (libsource (lib "eagle-import") (part "RSMD1.6X0.8MM"))
    )
    (comp (ref "R51")
      (value "100k")
      (footprint "eagle-import:RM1608")
      (libsource (lib "eagle-import") (part "RSMD1.6X0.8MM"))
    )
    (comp (ref "R52")
      (value "100k")
      (footprint "eagle-import:RM1608")
      (libsource (lib "eagle-import") (part "RSMD1.6X0.8MM"))
    )
    (comp (ref "R53")
      (value "10k")
      (footprint "eagle-import:RM1608")
      (libsource (lib "eagle-import") (part "RSMD1.6X0.8MM"))
    )
    (comp (ref "R54")
      (value "10k")
      (footprint "eagle-import:RM1608")
      (libsource (lib "eagle-import") (part "RSMD1.6X0.8MM"))
    )
    (comp (ref "R55")
      (value "2k/0.05%/10ppm")
      (footprint "eagle-import:RM1608")
      (libsource (lib "eagle-import") (part "RSMD1.6X0.8MM"))
    )
    (comp (ref "R56")
      (value "100/0.05%/10ppm")
      (footprint "eagle-import:RM1608")
      (libsource (lib "eagle-import") (part "RSMD1.6X0.8MM"))
    )
    (comp (ref "R57")
      (value "15k/0.05%/10ppm")
      (footprint "eagle-import:RM1608")
      (libsource (lib "eagle-import") (part "RSMD1.6X0.8MM"))
    )
    (comp (ref "R58")
      (value "620/THICK")
      (footprint "eagle-import:RM1608")
      (libsource (lib "eagle-import") (part "RSMD1.6X0.8MM"))
    )
    (comp (ref "TP1")
      (value "TP-LC3G")
      (footprint "eagle-import:TP_TH_0R9MM")
      (libsource (lib "eagle-import") (part "TP-LC3G"))
    )
    (comp (ref "TP2")
      (value "TP-LC3G")
      (footprint "eagle-import:TP_TH_0R9MM")
      (libsource (lib "eagle-import") (part "TP-LC3G"))
    )
    (comp (ref "TP3")
      (value "TP-LC3G")
      (footprint "eagle-import:TP_TH_0R9MM")
      (libsource (lib "eagle-import") (part "TP-LC3G"))
    )
    (comp (ref "TP4")
      (value "TP-LC3G")
      (footprint "eagle-import:TP_TH_0R9MM")
      (libsource (lib "eagle-import") (part "TP-LC3G"))
    )
    (comp (ref "TP5")
      (value "TP-LC3G")
      (footprint "eagle-import:TP_TH_0R9MM")
      (libsource (lib "eagle-import") (part "TP-LC3G"))
    )
    (comp (ref "TP6")
      (value "TP-LC3G")
      (footprint "eagle-import:TP_TH_0R9MM")
      (libsource (lib "eagle-import") (part "TP-LC3G"))
    )
    (comp (ref "TP7")
      (value "TP-LC3G")
      (footprint "eagle-import:TP_TH_0R9MM")
      (libsource (lib "eagle-import") (part "TP-LC3G"))
    )
    (comp (ref "TP8")
      (value "TP-LC3G")
      (footprint "eagle-import:TP_TH_0R9MM")
      (libsource (lib "eagle-import") (part "TP-LC3G"))
    )
    (comp (ref "TP9")
      (value "TP-LC3G")
      (footprint "eagle-import:TP_TH_0R9MM")
      (libsource (lib "eagle-import") (part "TP-LC3G"))
    )
    (comp (ref "U1")
      (value "OPA2344EA")
      (footprint "eagle-import:MSO8_AEL")
      (libsource (lib "eagle-import") (part "OPA2344EA"))
    )
    (comp (ref "U2")
      (value "OPA2344EA")
      (footprint "eagle-import:MSO8_AEL")
      (libsource (lib "eagle-import") (part "OPA2344EA"))
    )
    (comp (ref "U3")
      (value "TS5A23159DGS")
      (footprint "eagle-import:MSOP10")
      (libsource (lib "eagle-import") (part "TS5A23159DGS"))
    )
    (comp (ref "U4")
      (value "TPS79933DDC")
      (footprint "eagle-import:SOT-23-5")
      (libsource (lib "eagle-import") (part "TPS799DDC33"))
    )
    (comp (ref "U5")
      (value "OPA2344EA")
      (footprint "eagle-import:MSO8_AEL")
      (libsource (lib "eagle-import") (part "OPA2344EA"))
    )
    (comp (ref "U6")
      (value "TPS3808G01DBV")
      (footprint "eagle-import:SOT-23")
      (libsource (lib "eagle-import") (part "TPS3808GDBV01"))
    )
    (comp (ref "U7")
      (value "NJU7108F3")
      (footprint "eagle-import:SC88A")
      (libsource (lib "eagle-import") (part "NJU7108F3"))
    )
    (comp (ref "U8")
      (value "OPA2344EA")
      (footprint "eagle-import:MSO8_AEL")
      (libsource (lib "eagle-import") (part "OPA2344EA"))
    )
    (comp (ref "U9")
      (value "TS5A23159DGS")
      (footprint "eagle-import:MSOP10")
      (libsource (lib "eagle-import") (part "TS5A23159DGS"))
    )
    (comp (ref "U10")
      (value "74VHC4052AFT")
      (footprint "eagle-import:TSSOP16-P-044-065A")
      (libsource (lib "eagle-import") (part "744052AFTVHC"))
    )
    (comp (ref "U11")
      (value "AD8227ARZ")
      (footprint "eagle-import:SO8_AEL")
      (libsource (lib "eagle-import") (part "AD8227RZA"))
    )
    (comp (ref "CN5")
      (value "DF11-4DP-2DSA")
      (footprint "eagle-import:DF11-4DP-2DSA")
      (libsource (lib "eagle-import") (part "DF11-4DP-2DSA"))
    )
    (comp (ref "CN6")
      (value "DF11-4DP-2DSA")
      (footprint "eagle-import:DF11-4DP-2DSA")
      (libsource (lib "eagle-import") (part "DF11-4DP-2DSA"))
    )
    (comp (ref "CN7")
      (value "DF11-14DP-2DSA")
      (footprint "eagle-import:DF11-14DP-2DSA")
      (libsource (lib "eagle-import") (part "DF11-14DP-2DSA"))
    )
    (comp (ref "CN8")
      (value "PH-2X4S")
      (footprint "eagle-import:PIN_HEADER_8PIN")
      (libsource (lib "eagle-import") (part "PH-2X4S"))
    )
    (comp (ref "CN9")
      (value "DF11-4DP-2DSA")
      (footprint "eagle-import:DF11-4DP-2DSA")
      (libsource (lib "eagle-import") (part "DF11-4DP-2DSA"))
    )
    (comp (ref "CN10")
      (value "826646-4")
      (footprint "eagle-import:PIN_HEADER_4PIN")
      (libsource (lib "eagle-import") (part "PH-1X4"))
    )
    (comp (ref "CN11")
      (value "826646-4")
      (footprint "eagle-import:PIN_HEADER_4PIN")
      (libsource (lib "eagle-import") (part "PH-1X4"))
    )
    (comp (ref "CN12")
      (value "BNC_ANGLE")
      (footprint "eagle-import:BNC_F_ANGLE")
      (libsource (lib "eagle-import") (part "BNC_ANGLE"))
    )
    (comp (ref "CN13")
      (value "BNC_ANGLE")
      (footprint "eagle-import:BNC_F_ANGLE")
      (libsource (lib "eagle-import") (part "BNC_ANGLE"))
    )
    (comp (ref "CN14")
      (value "BNC_ANGLE")
      (footprint "eagle-import:BNC_F_ANGLE")
      (libsource (lib "eagle-import") (part "BNC_ANGLE"))
    )
    (comp (ref "CN15")
      (value "DF11-4DP-2DSA")
      (footprint "eagle-import:DF11-4DP-2DSA")
      (libsource (lib "eagle-import") (part "DF11-4DP-2DSA"))
    )
    (comp (ref "CN16")
      (value "PCS-XE50LFD")
      (footprint "eagle-import:50LFD2")
      (libsource (lib "eagle-import") (part "PCS-XE50LFD"))
    )
    (comp (ref "CN17")
      (value "PCS-XE50LFD")
      (footprint "eagle-import:50LFD2")
      (libsource (lib "eagle-import") (part "PCS-XE50LFD"))
    )
    (comp (ref "D4")
      (value "L-93A8CB/1GD")
      (footprint "eagle-import:L-93A8CB")
      (libsource (lib "eagle-import") (part "L-93A8CB/1GD"))
    )
    (comp (ref "D5")
      (value "L-93A8CB/1ID")
      (footprint "eagle-import:L-93A8CB")
      (libsource (lib "eagle-import") (part "L-93A8CB/1ID"))
    )
    (comp (ref "D6")
      (value "L-93A8CB/1GD")
      (footprint "eagle-import:L-93A8CB")
      (libsource (lib "eagle-import") (part "L-93A8CB/1GD"))
    )
    (comp (ref "F2")
      (value "RXEF050")
      (footprint "eagle-import:8X3_5.08")
      (libsource (lib "eagle-import") (part "RXEF050"))
    )
    (comp (ref "M2")
      (value "VAB-3-10")
      (footprint "eagle-import:VAB_3_10_CONTACT")
      (libsource (lib "eagle-import") (part "VAB-3-10"))
    )
    (comp (ref "M3")
      (value "VAB-3-10")
      (footprint "eagle-import:VAB_3_10_CONTACT")
      (libsource (lib "eagle-import") (part "VAB-3-10"))
    )
    (comp (ref "R59")
      (value "680/LEAD")
      (footprint "eagle-import:0207_2V")
      (libsource (lib "eagle-import") (part "R0207/2V"))
    )
    (comp (ref "R60")
      (value "680/LEAD")
      (footprint "eagle-import:0207_2V")
      (libsource (lib "eagle-import") (part "R0207/2V"))
    )
    (comp (ref "R61")
      (value "680/LEAD")
      (footprint "eagle-import:0207_2V")
      (libsource (lib "eagle-import") (part "R0207/2V"))
    )
    (comp (ref "SW1")
      (value "A-12AV")
      (footprint "eagle-import:A-12_")
      (libsource (lib "eagle-import") (part "A-1V2A"))
    )
    (comp (ref "SW2")
      (value "A-12AV")
      (footprint "eagle-import:A-12_")
      (libsource (lib "eagle-import") (part "A-1V2A"))
    )
    (comp (ref "SW3")
      (value "A-12AV")
      (footprint "eagle-import:A-12_")
      (libsource (lib "eagle-import") (part "A-1V2A"))
    )
    (comp (ref "SW4")
      (value "A-12AV")
      (footprint "eagle-import:A-12_")
      (libsource (lib "eagle-import") (part "A-1V2A"))
    )
  )
  (nets
    (net (code "1") (name "0V") (class "Default")
      (node (ref "C1") (pin "2") (pinfunction "2_2") (pintype "passive"))
      (node (ref "C17") (pin "2") (pinfunction "2_2") (pintype "passive"))
      (node (ref "C23") (pin "POS") (pinfunction "POS_POS") (pintype "passive"))
      (node (ref "C3") (pin "1") (pinfunction "1_1") (pintype "passive"))
      (node (ref "C5") (pin "1") (pinfunction "1_1") (pintype "passive"))
      (node (ref "D3") (pin "1") (pinfunction "A_1") (pintype "passive"))
      (node (ref "D3") (pin "2") (pinfunction "C_2") (pintype "passive"))
      (node (ref "R1") (pin "1") (pinfunction "1_1") (pintype "passive"))
      (node (ref "R13") (pin "2") (pinfunction "2_2") (pintype "passive"))
      (node (ref "R15") (pin "2") (pinfunction "2_2") (pintype "passive"))
      (node (ref "R21") (pin "1") (pinfunction "1_1") (pintype "passive"))
      (node (ref "R29") (pin "1") (pinfunction "1_1") (pintype "passive"))
      (node (ref "R40") (pin "1") (pinfunction "1_1") (pintype "passive"))
      (node (ref "R41") (pin "1") (pinfunction "1_1") (pintype "passive"))
      (node (ref "R46") (pin "2") (pinfunction "2_2") (pintype "passive"))
      (node (ref "TP7") (pin "1") (pinfunction "MP_1") (pintype "passive"))
      (node (ref "U1") (pin "5") (pinfunction "+IN_5") (pintype "input"))
      (node (ref "U8") (pin "5") (pinfunction "+IN_5") (pintype "input"))
    )
    (net (code "2") (name "AGND") (class "Default")
      (node (ref "C12") (pin "2") (pinfunction "2_2") (pintype "passive"))
      (node (ref "C13") (pin "2") (pinfunction "2_2") (pintype "passive"))
      (node (ref "C15") (pin "1") (pinfunction "1_1") (pintype "passive"))
      (node (ref "C16") (pin "2") (pinfunction "2_2") (pintype "passive"))
      (node (ref "C18") (pin "2") (pinfunction "2_2") (pintype "passive"))
      (node (ref "C20") (pin "2") (pinfunction "2_2") (pintype "passive"))
      (node (ref "C21") (pin "2") (pinfunction "2_2") (pintype "passive"))
      (node (ref "C22") (pin "2") (pinfunction "2_2") (pintype "passive"))
      (node (ref "C23") (pin "NEG") (pinfunction "NEG_NEG") (pintype "passive"))
      (node (ref "C24") (pin "2") (pinfunction "2_2") (pintype "passive"))
      (node (ref "C25") (pin "2") (pinfunction "2_2") (pintype "passive"))
      (node (ref "C26") (pin "1") (pinfunction "1_1") (pintype "passive"))
      (node (ref "C27") (pin "2") (pinfunction "2_2") (pintype "passive"))
      (node (ref "C28") (pin "2") (pinfunction "2_2") (pintype "passive"))
      (node (ref "C29") (pin "2") (pinfunction "2_2") (pintype "passive"))
      (node (ref "C30") (pin "2") (pinfunction "2_2") (pintype "passive"))
      (node (ref "C31") (pin "2") (pinfunction "2_2") (pintype "passive"))
      (node (ref "C32") (pin "2") (pinfunction "2_2") (pintype "passive"))
      (node (ref "C33") (pin "2") (pinfunction "2_2") (pintype "passive"))
      (node (ref "C34") (pin "2") (pinfunction "2_2") (pintype "passive"))
      (node (ref "C35") (pin "2") (pinfunction "2_2") (pintype "passive"))
      (node (ref "C36") (pin "2") (pinfunction "2_2") (pintype "passive"))
      (node (ref "C37") (pin "2") (pinfunction "2_2") (pintype "passive"))
      (node (ref "C38") (pin "2") (pinfunction "2_2") (pintype "passive"))
      (node (ref "C39") (pin "2") (pinfunction "2_2") (pintype "passive"))
      (node (ref "C40") (pin "2") (pinfunction "2_2") (pintype "passive"))
      (node (ref "C41") (pin "2") (pinfunction "2_2") (pintype "passive"))
      (node (ref "C8") (pin "NEG") (pinfunction "NEG_NEG") (pintype "passive"))
      (node (ref "C9") (pin "2") (pinfunction "2_2") (pintype "passive"))
      (node (ref "CN16") (pin "51") (pinfunction "G1_51") (pintype "bidirectional"))
      (node (ref "CN16") (pin "52") (pinfunction "G2_52") (pintype "bidirectional"))
      (node (ref "CN17") (pin "51") (pinfunction "G1_51") (pintype "bidirectional"))
      (node (ref "CN17") (pin "52") (pinfunction "G2_52") (pintype "bidirectional"))
      (node (ref "CN4") (pin "3") (pinfunction "3_3") (pintype "bidirectional"))
      (node (ref "CN4") (pin "4") (pinfunction "4_4") (pintype "bidirectional"))
      (node (ref "D1") (pin "1") (pinfunction "A_1") (pintype "passive"))
      (node (ref "D2") (pin "1") (pinfunction "A_1") (pintype "passive"))
      (node (ref "L3") (pin "2") (pinfunction "3_2") (pintype "passive"))
      (node (ref "R32") (pin "1") (pinfunction "1_1") (pintype "passive"))
      (node (ref "R43") (pin "1") (pinfunction "1_1") (pintype "passive"))
      (node (ref "TP9") (pin "1") (pinfunction "MP_1") (pintype "passive"))
      (node (ref "U1") (pin "4") (pinfunction "V-_4") (pintype "power_in"))
      (node (ref "U10") (pin "6") (pinfunction "INH_6") (pintype "input"))
      (node (ref "U10") (pin "7") (pinfunction "GND_7") (pintype "power_in"))
      (node (ref "U10") (pin "8") (pinfunction "GND_8") (pintype "input"))
      (node (ref "U11") (pin "5") (pinfunction "V-_5") (pintype "power_in"))
      (node (ref "U12") (pin "8") (pinfunction "V-_8") (pintype "power_in"))
      (node (ref "U13") (pin "8") (pinfunction "V-_8") (pintype "power_in"))
      (node (ref "U14") (pin "8") (pinfunction "V-_8") (pintype "power_in"))
      (node (ref "U15") (pin "8") (pinfunction "V-_8") (pintype "power_in"))
      (node (ref "U16") (pin "8") (pinfunction "V-_8") (pintype "power_in"))
      (node (ref "U17") (pin "8") (pinfunction "V-_8") (pintype "power_in"))
      (node (ref "U18") (pin "8") (pinfunction "V-_8") (pintype "power_in"))
      (node (ref "U19") (pin "8") (pinfunction "V-_8") (pintype "power_in"))
      (node (ref "U2") (pin "4") (pinfunction "V-_4") (pintype "power_in"))
      (node (ref "U20") (pin "8") (pinfunction "V-_8") (pintype "power_in"))
      (node (ref "U21") (pin "8") (pinfunction "V-_8") (pintype "power_in"))
      (node (ref "U22") (pin "8") (pinfunction "V-_8") (pintype "power_in"))
      (node (ref "U23") (pin "8") (pinfunction "V-_8") (pintype "power_in"))
      (node (ref "U24") (pin "8") (pinfunction "V-_8") (pintype "power_in"))
      (node (ref "U25") (pin "8") (pinfunction "V-_8") (pintype "power_in"))
      (node (ref "U3") (pin "3") (pinfunction "V-_3") (pintype "power_in"))
      (node (ref "U4") (pin "2") (pinfunction "GND_2") (pintype "passive"))
      (node (ref "U5") (pin "4") (pinfunction "V-_4") (pintype "power_in"))
      (node (ref "U7") (pin "2") (pinfunction "V-_2") (pintype "power_in"))
      (node (ref "U8") (pin "4") (pinfunction "V-_4") (pintype "power_in"))
      (node (ref "U9") (pin "3") (pinfunction "V-_3") (pintype "power_in"))
    )
    (net (code "3") (name "AMP_0") (class "Default")
      (node (ref "U10") (pin "10") (pinfunction "A_10") (pintype "input"))
      (node (ref "U27") (pin "19") (pinfunction "1-14_19") (pintype "bidirectional"))
    )
    (net (code "4") (name "AMP_1") (class "Default")
      (node (ref "U10") (pin "9") (pinfunction "B_9") (pintype "input"))
      (node (ref "U27") (pin "20") (pinfunction "1-15_20") (pintype "bidirectional"))
    )
    (net (code "5") (name "ANALOG{slash}~{DDS}") (class "Default")
      (node (ref "R70") (pin "1") (pinfunction "1_1") (pintype "passive"))
      (node (ref "U3") (pin "5") (pinfunction "IN_5") (pintype "input"))
    )
    (net (code "6") (name "BATT+") (class "Default")
      (node (ref "F1") (pin "2") (pinfunction "2_2") (pintype "passive"))
      (node (ref "L3") (pin "4") (pinfunction "2_4") (pintype "passive"))
      (node (ref "L5") (pin "1") (pinfunction "1_1") (pintype "passive"))
    )
    (net (code "7") (name "BATT-") (class "Default")
      (node (ref "CN3") (pin "3") (pinfunction "3_3") (pintype "bidirectional"))
      (node (ref "CN3") (pin "4") (pinfunction "4_4") (pintype "bidirectional"))
      (node (ref "L3") (pin "3") (pinfunction "4_3") (pintype "passive"))
      (node (ref "L5") (pin "2") (pinfunction "3_2") (pintype "passive"))
    )
    (net (code "8") (name "CH_0") (class "Default")
      (node (ref "R68") (pin "1") (pinfunction "1_1") (pintype "passive"))
      (node (ref "U12") (pin "11") (pinfunction "A_11") (pintype "input"))
      (node (ref "U13") (pin "11") (pinfunction "A_11") (pintype "input"))
      (node (ref "U14") (pin "11") (pinfunction "A_11") (pintype "input"))
      (node (ref "U15") (pin "11") (pinfunction "A_11") (pintype "input"))
      (node (ref "U16") (pin "11") (pinfunction "A_11") (pintype "input"))
      (node (ref "U17") (pin "11") (pinfunction "A_11") (pintype "input"))
      (node (ref "U18") (pin "11") (pinfunction "A_11") (pintype "input"))
      (node (ref "U19") (pin "11") (pinfunction "A_11") (pintype "input"))
      (node (ref "U20") (pin "11") (pinfunction "A_11") (pintype "input"))
      (node (ref "U21") (pin "11") (pinfunction "A_11") (pintype "input"))
      (node (ref "U22") (pin "11") (pinfunction "A_11") (pintype "input"))
      (node (ref "U23") (pin "11") (pinfunction "A_11") (pintype "input"))
      (node (ref "U24") (pin "11") (pinfunction "A_11") (pintype "input"))
      (node (ref "U25") (pin "11") (pinfunction "A_11") (pintype "input"))
    )
    (net (code "9") (name "CH_1") (class "Default")
      (node (ref "R69") (pin "1") (pinfunction "1_1") (pintype "passive"))
      (node (ref "U12") (pin "10") (pinfunction "B_10") (pintype "input"))
      (node (ref "U13") (pin "10") (pinfunction "B_10") (pintype "input"))
      (node (ref "U14") (pin "10") (pinfunction "B_10") (pintype "input"))
      (node (ref "U15") (pin "10") (pinfunction "B_10") (pintype "input"))
      (node (ref "U16") (pin "10") (pinfunction "B_10") (pintype "input"))
      (node (ref "U17") (pin "10") (pinfunction "B_10") (pintype "input"))
      (node (ref "U18") (pin "10") (pinfunction "B_10") (pintype "input"))
      (node (ref "U19") (pin "10") (pinfunction "B_10") (pintype "input"))
      (node (ref "U20") (pin "10") (pinfunction "B_10") (pintype "input"))
      (node (ref "U21") (pin "10") (pinfunction "B_10") (pintype "input"))
      (node (ref "U22") (pin "10") (pinfunction "B_10") (pintype "input"))
      (node (ref "U23") (pin "10") (pinfunction "B_10") (pintype "input"))
      (node (ref "U24") (pin "10") (pinfunction "B_10") (pintype "input"))
      (node (ref "U25") (pin "10") (pinfunction "B_10") (pintype "input"))
    )
    (net (code "10") (name "CH_2") (class "Default")
      (node (ref "R67") (pin "1") (pinfunction "1_1") (pintype "passive"))
      (node (ref "U12") (pin "9") (pinfunction "C_9") (pintype "input"))
      (node (ref "U13") (pin "9") (pinfunction "C_9") (pintype "input"))
      (node (ref "U14") (pin "9") (pinfunction "C_9") (pintype "input"))
      (node (ref "U15") (pin "9") (pinfunction "C_9") (pintype "input"))
      (node (ref "U16") (pin "9") (pinfunction "C_9") (pintype "input"))
      (node (ref "U17") (pin "9") (pinfunction "C_9") (pintype "input"))
      (node (ref "U18") (pin "9") (pinfunction "C_9") (pintype "input"))
      (node (ref "U19") (pin "9") (pinfunction "C_9") (pintype "input"))
      (node (ref "U20") (pin "9") (pinfunction "C_9") (pintype "input"))
      (node (ref "U21") (pin "9") (pinfunction "C_9") (pintype "input"))
      (node (ref "U22") (pin "9") (pinfunction "C_9") (pintype "input"))
      (node (ref "U23") (pin "9") (pinfunction "C_9") (pintype "input"))
      (node (ref "U24") (pin "9") (pinfunction "C_9") (pintype "input"))
      (node (ref "U25") (pin "9") (pinfunction "C_9") (pintype "input"))
    )
    (net (code "11") (name "CURRENT_MON") (class "Default")
      (node (ref "R58") (pin "1") (pinfunction "1_1") (pintype "passive"))
      (node (ref "U11") (pin "7") (pinfunction "OUT_7") (pintype "output"))
    )
    (net (code "12") (name "DGND") (class "Default")
      (node (ref "C10") (pin "2") (pinfunction "2_2") (pintype "passive"))
      (node (ref "C11") (pin "2") (pinfunction "2_2") (pintype "passive"))
      (node (ref "C42") (pin "2") (pinfunction "2_2") (pintype "passive"))
      (node (ref "C43") (pin "2") (pinfunction "2_2") (pintype "passive"))
      (node (ref "C44") (pin "2") (pinfunction "2_2") (pintype "passive"))
      (node (ref "C45") (pin "2") (pinfunction "2_2") (pintype "passive"))
      (node (ref "C46") (pin "NEG") (pinfunction "NEG_NEG") (pintype "passive"))
      (node (ref "C47") (pin "2") (pinfunction "2_2") (pintype "passive"))
      (node (ref "C48") (pin "1") (pinfunction "1_1") (pintype "passive"))
      (node (ref "C49") (pin "1") (pinfunction "1_1") (pintype "passive"))
      (node (ref "C50") (pin "1") (pinfunction "1_1") (pintype "passive"))
      (node (ref "C51") (pin "1") (pinfunction "1_1") (pintype "passive"))
      (node (ref "C52") (pin "2") (pinfunction "2_2") (pintype "passive"))
      (node (ref "C53") (pin "2") (pinfunction "2_2") (pintype "passive"))
      (node (ref "C54") (pin "2") (pinfunction "2_2") (pintype "passive"))
      (node (ref "C55") (pin "2") (pinfunction "2_2") (pintype "passive"))
      (node (ref "C56") (pin "2") (pinfunction "2_2") (pintype "passive"))
      (node (ref "C57") (pin "2") (pinfunction "2_2") (pintype "passive"))
      (node (ref "C58") (pin "2") (pinfunction "2_2") (pintype "passive"))
      (node (ref "C59") (pin "2") (pinfunction "2_2") (pintype "passive"))
      (node (ref "C60") (pin "2") (pinfunction "2_2") (pintype "passive"))
      (node (ref "C61") (pin "2") (pinfunction "2_2") (pintype "passive"))
      (node (ref "C62") (pin "2") (pinfunction "2_2") (pintype "passive"))
      (node (ref "CN10") (pin "4") (pinfunction "4_4") (pintype "bidirectional"))
      (node (ref "CN11") (pin "4") (pinfunction "4_4") (pintype "bidirectional"))
      (node (ref "CN18") (pin "10") (pinfunction "10_10") (pintype "bidirectional"))
      (node (ref "CN18") (pin "2") (pinfunction "2_2") (pintype "bidirectional"))
      (node (ref "CN19") (pin "10") (pinfunction "10_10") (pintype "bidirectional"))
      (node (ref "CN19") (pin "2") (pinfunction "2_2") (pintype "bidirectional"))
      (node (ref "CN19") (pin "4") (pinfunction "4_4") (pintype "bidirectional"))
      (node (ref "CN20") (pin "2") (pinfunction "2_2") (pintype "bidirectional"))
      (node (ref "CN20") (pin "8") (pinfunction "8_8") (pintype "bidirectional"))
      (node (ref "CN7") (pin "2") (pinfunction "2_2") (pintype "bidirectional"))
      (node (ref "D4") (pin "C") (pinfunction "K1_C") (pintype "passive"))
      (node (ref "L5") (pin "3") (pinfunction "4_3") (pintype "passive"))
      (node (ref "M1") (pin "CASE1") (pinfunction "P$1_CASE1") (pintype "bidirectional"))
      (node (ref "M2") (pin "CASE1") (pinfunction "P$1_CASE1") (pintype "bidirectional"))
      (node (ref "M3") (pin "CASE1") (pinfunction "P$1_CASE1") (pintype "bidirectional"))
      (node (ref "R25") (pin "1") (pinfunction "1_1") (pintype "passive"))
      (node (ref "R65") (pin "1") (pinfunction "1_1") (pintype "passive"))
      (node (ref "R77") (pin "1") (pinfunction "1_1") (pintype "passive"))
      (node (ref "SW1") (pin "7") (pinfunction "BRACKET_7") (pintype "passive"))
      (node (ref "SW1") (pin "8") (pinfunction "BRACKET_8") (pintype "passive"))
      (node (ref "SW2") (pin "3") (pinfunction "NC_3") (pintype "passive"))
      (node (ref "SW2") (pin "7") (pinfunction "BRACKET_7") (pintype "passive"))
      (node (ref "SW2") (pin "8") (pinfunction "BRACKET_8") (pintype "passive"))
      (node (ref "SW3") (pin "3") (pinfunction "NC_3") (pintype "passive"))
      (node (ref "SW3") (pin "7") (pinfunction "BRACKET_7") (pintype "passive"))
      (node (ref "SW3") (pin "8") (pinfunction "BRACKET_8") (pintype "passive"))
      (node (ref "SW4") (pin "3") (pinfunction "NC_3") (pintype "passive"))
      (node (ref "SW4") (pin "7") (pinfunction "BRACKET_7") (pintype "passive"))
      (node (ref "SW4") (pin "8") (pinfunction "BRACKET_8") (pintype "passive"))
      (node (ref "TP15") (pin "1") (pinfunction "MP_1") (pintype "passive"))
      (node (ref "U26") (pin "2") (pinfunction "GND_2") (pintype "passive"))
      (node (ref "U27") (pin "1") (pinfunction "GND_1_1") (pintype "power_in"))
      (node (ref "U27") (pin "10") (pinfunction "GND_2_10") (pintype "power_in"))
      (node (ref "U27") (pin "11") (pinfunction "GND_3_11") (pintype "power_in"))
      (node (ref "U27") (pin "32") (pinfunction "GND_4_32") (pintype "power_in"))
      (node (ref "U27") (pin "43") (pinfunction "1-32/DEV_OE_43") (pintype "bidirectional"))
      (node (ref "U27") (pin "44") (pinfunction "1-33/~{DEV_CLR}_44") (pintype "bidirectional"))
      (node (ref "U27") (pin "46") (pinfunction "GND_5_46") (pintype "power_in"))
      (node (ref "U27") (pin "60") (pinfunction "GND_6_60") (pintype "power_in"))
      (node (ref "U27") (pin "65") (pinfunction "GND_7_65") (pintype "power_in"))
      (node (ref "U27") (pin "79") (pinfunction "GND_8_79") (pintype "power_in"))
      (node (ref "U27") (pin "93") (pinfunction "GND_9_93") (pintype "power_in"))
      (node (ref "U28") (pin "2") (pinfunction "GND_2") (pintype "passive"))
      (node (ref "U29") (pin "10") (pinfunction "GND_10") (pintype "power_in"))
      (node (ref "U30") (pin "2") (pinfunction "C_2") (pintype "passive"))
      (node (ref "U6") (pin "2") (pinfunction "GND_2") (pintype "power_in"))
    )
    (net (code "13") (name "DISP1") (class "Default")
      (node (ref "TP14") (pin "P$1") (pinfunction "MP_P$1") (pintype "passive"))
      (node (ref "U27") (pin "56") (pinfunction "2-5_56") (pintype "bidirectional"))
      (node (ref "U29") (pin "9") (pinfunction "A8_9") (pintype "input"))
    )
    (net (code "14") (name "DISP2") (class "Default")
      (node (ref "TP13") (pin "P$1") (pinfunction "MP_P$1") (pintype "passive"))
      (node (ref "U27") (pin "57") (pinfunction "2-6_57") (pintype "bidirectional"))
      (node (ref "U29") (pin "8") (pinfunction "A7_8") (pintype "input"))
    )
    (net (code "15") (name "DISP3") (class "Default")
      (node (ref "TP12") (pin "P$1") (pinfunction "MP_P$1") (pintype "passive"))
      (node (ref "U27") (pin "58") (pinfunction "2-7_58") (pintype "bidirectional"))
      (node (ref "U29") (pin "7") (pinfunction "A6_7") (pintype "input"))
    )
    (net (code "16") (name "DISP4") (class "Default")
      (node (ref "TP11") (pin "P$1") (pinfunction "MP_P$1") (pintype "passive"))
      (node (ref "U27") (pin "61") (pinfunction "2-8_61") (pintype "bidirectional"))
      (node (ref "U29") (pin "6") (pinfunction "A5_6") (pintype "input"))
    )
    (net (code "17") (name "DO2") (class "Default")
      (node (ref "U29") (pin "12") (pinfunction "Y7_12") (pintype "output"))
    )
    (net (code "18") (name "DO3") (class "Default")
      (node (ref "U29") (pin "13") (pinfunction "Y6_13") (pintype "output"))
    )
    (net (code "19") (name "DO4") (class "Default")
      (node (ref "U29") (pin "14") (pinfunction "Y5_14") (pintype "output"))
    )
    (net (code "20") (name "DRIVE01+") (class "Default")
      (node (ref "CN16") (pin "25") (pinfunction "25_25") (pintype "bidirectional"))
      (node (ref "U12") (pin "13") (pinfunction "0_13") (pintype "bidirectional"))
    )
    (net (code "21") (name "DRIVE01-") (class "Default")
      (node (ref "CN16") (pin "50") (pinfunction "50_50") (pintype "bidirectional"))
      (node (ref "U18") (pin "13") (pinfunction "0_13") (pintype "bidirectional"))
    )
    (net (code "22") (name "DRIVE02+") (class "Default")
      (node (ref "CN16") (pin "24") (pinfunction "24_24") (pintype "bidirectional"))
      (node (ref "U12") (pin "14") (pinfunction "1_14") (pintype "bidirectional"))
    )
    (net (code "23") (name "DRIVE02-") (class "Default")
      (node (ref "CN16") (pin "49") (pinfunction "49_49") (pintype "bidirectional"))
      (node (ref "U18") (pin "14") (pinfunction "1_14") (pintype "bidirectional"))
    )
    (net (code "24") (name "DRIVE03+") (class "Default")
      (node (ref "CN16") (pin "23") (pinfunction "23_23") (pintype "bidirectional"))
      (node (ref "U12") (pin "15") (pinfunction "2_15") (pintype "bidirectional"))
    )
    (net (code "25") (name "DRIVE03-") (class "Default")
      (node (ref "CN16") (pin "48") (pinfunction "48_48") (pintype "bidirectional"))
      (node (ref "U18") (pin "15") (pinfunction "2_15") (pintype "bidirectional"))
    )
    (net (code "26") (name "DRIVE04+") (class "Default")
      (node (ref "CN16") (pin "22") (pinfunction "22_22") (pintype "bidirectional"))
      (node (ref "U12") (pin "12") (pinfunction "3_12") (pintype "bidirectional"))
    )
    (net (code "27") (name "DRIVE04-") (class "Default")
      (node (ref "CN16") (pin "47") (pinfunction "47_47") (pintype "bidirectional"))
      (node (ref "U18") (pin "12") (pinfunction "3_12") (pintype "bidirectional"))
    )
    (net (code "28") (name "DRIVE05+") (class "Default")
      (node (ref "CN16") (pin "21") (pinfunction "21_21") (pintype "bidirectional"))
      (node (ref "U12") (pin "1") (pinfunction "4_1") (pintype "bidirectional"))
    )
    (net (code "29") (name "DRIVE05-") (class "Default")
      (node (ref "CN16") (pin "46") (pinfunction "46_46") (pintype "bidirectional"))
      (node (ref "U18") (pin "1") (pinfunction "4_1") (pintype "bidirectional"))
    )
    (net (code "30") (name "DRIVE06+") (class "Default")
      (node (ref "CN16") (pin "20") (pinfunction "20_20") (pintype "bidirectional"))
      (node (ref "U12") (pin "5") (pinfunction "5_5") (pintype "bidirectional"))
    )
    (net (code "31") (name "DRIVE06-") (class "Default")
      (node (ref "CN16") (pin "45") (pinfunction "45_45") (pintype "bidirectional"))
      (node (ref "U18") (pin "5") (pinfunction "5_5") (pintype "bidirectional"))
    )
    (net (code "32") (name "DRIVE07+") (class "Default")
      (node (ref "CN16") (pin "19") (pinfunction "19_19") (pintype "bidirectional"))
      (node (ref "U12") (pin "2") (pinfunction "6_2") (pintype "bidirectional"))
    )
    (net (code "33") (name "DRIVE07-") (class "Default")
      (node (ref "CN16") (pin "44") (pinfunction "44_44") (pintype "bidirectional"))
      (node (ref "U18") (pin "2") (pinfunction "6_2") (pintype "bidirectional"))
    )
    (net (code "34") (name "DRIVE08+") (class "Default")
      (node (ref "CN16") (pin "18") (pinfunction "18_18") (pintype "bidirectional"))
      (node (ref "U12") (pin "4") (pinfunction "7_4") (pintype "bidirectional"))
    )
    (net (code "35") (name "DRIVE08-") (class "Default")
      (node (ref "CN16") (pin "43") (pinfunction "43_43") (pintype "bidirectional"))
      (node (ref "U18") (pin "4") (pinfunction "7_4") (pintype "bidirectional"))
    )
    (net (code "36") (name "DRIVE09+") (class "Default")
      (node (ref "CN16") (pin "17") (pinfunction "17_17") (pintype "bidirectional"))
      (node (ref "U14") (pin "13") (pinfunction "0_13") (pintype "bidirectional"))
    )
    (net (code "37") (name "DRIVE09-") (class "Default")
      (node (ref "CN16") (pin "42") (pinfunction "42_42") (pintype "bidirectional"))
      (node (ref "U20") (pin "13") (pinfunction "0_13") (pintype "bidirectional"))
    )
    (net (code "38") (name "DRIVE10+") (class "Default")
      (node (ref "CN16") (pin "16") (pinfunction "16_16") (pintype "bidirectional"))
      (node (ref "U14") (pin "14") (pinfunction "1_14") (pintype "bidirectional"))
    )
    (net (code "39") (name "DRIVE10-") (class "Default")
      (node (ref "CN16") (pin "41") (pinfunction "41_41") (pintype "bidirectional"))
      (node (ref "U20") (pin "14") (pinfunction "1_14") (pintype "bidirectional"))
    )
    (net (code "40") (name "DRIVE11+") (class "Default")
      (node (ref "CN16") (pin "15") (pinfunction "15_15") (pintype "bidirectional"))
      (node (ref "U14") (pin "15") (pinfunction "2_15") (pintype "bidirectional"))
    )
    (net (code "41") (name "DRIVE11-") (class "Default")
      (node (ref "CN16") (pin "40") (pinfunction "40_40") (pintype "bidirectional"))
      (node (ref "U20") (pin "15") (pinfunction "2_15") (pintype "bidirectional"))
    )
    (net (code "42") (name "DRIVE12+") (class "Default")
      (node (ref "CN16") (pin "14") (pinfunction "14_14") (pintype "bidirectional"))
      (node (ref "U14") (pin "12") (pinfunction "3_12") (pintype "bidirectional"))
    )
    (net (code "43") (name "DRIVE12-") (class "Default")
      (node (ref "CN16") (pin "39") (pinfunction "39_39") (pintype "bidirectional"))
      (node (ref "U20") (pin "12") (pinfunction "3_12") (pintype "bidirectional"))
    )
    (net (code "44") (name "DRIVE13+") (class "Default")
      (node (ref "CN16") (pin "13") (pinfunction "13_13") (pintype "bidirectional"))
      (node (ref "U14") (pin "1") (pinfunction "4_1") (pintype "bidirectional"))
    )
    (net (code "45") (name "DRIVE13-") (class "Default")
      (node (ref "CN16") (pin "38") (pinfunction "38_38") (pintype "bidirectional"))
      (node (ref "U20") (pin "1") (pinfunction "4_1") (pintype "bidirectional"))
    )
    (net (code "46") (name "DRIVE14+") (class "Default")
      (node (ref "CN16") (pin "12") (pinfunction "12_12") (pintype "bidirectional"))
      (node (ref "U14") (pin "5") (pinfunction "5_5") (pintype "bidirectional"))
    )
    (net (code "47") (name "DRIVE14-") (class "Default")
      (node (ref "CN16") (pin "37") (pinfunction "37_37") (pintype "bidirectional"))
      (node (ref "U20") (pin "5") (pinfunction "5_5") (pintype "bidirectional"))
    )
    (net (code "48") (name "DRIVE15+") (class "Default")
      (node (ref "CN16") (pin "11") (pinfunction "11_11") (pintype "bidirectional"))
      (node (ref "U14") (pin "2") (pinfunction "6_2") (pintype "bidirectional"))
    )
    (net (code "49") (name "DRIVE15-") (class "Default")
      (node (ref "CN16") (pin "36") (pinfunction "36_36") (pintype "bidirectional"))
      (node (ref "U20") (pin "2") (pinfunction "6_2") (pintype "bidirectional"))
    )
    (net (code "50") (name "DRIVE16+") (class "Default")
      (node (ref "CN16") (pin "10") (pinfunction "10_10") (pintype "bidirectional"))
      (node (ref "U14") (pin "4") (pinfunction "7_4") (pintype "bidirectional"))
    )
    (net (code "51") (name "DRIVE16-") (class "Default")
      (node (ref "CN16") (pin "35") (pinfunction "35_35") (pintype "bidirectional"))
      (node (ref "U20") (pin "4") (pinfunction "7_4") (pintype "bidirectional"))
    )
    (net (code "52") (name "DRIVE17+") (class "Default")
      (node (ref "CN16") (pin "9") (pinfunction "9_9") (pintype "bidirectional"))
      (node (ref "U16") (pin "13") (pinfunction "0_13") (pintype "bidirectional"))
    )
    (net (code "53") (name "DRIVE17-") (class "Default")
      (node (ref "CN16") (pin "34") (pinfunction "34_34") (pintype "bidirectional"))
      (node (ref "U22") (pin "13") (pinfunction "0_13") (pintype "bidirectional"))
    )
    (net (code "54") (name "DRIVE18+") (class "Default")
      (node (ref "CN16") (pin "8") (pinfunction "8_8") (pintype "bidirectional"))
      (node (ref "U16") (pin "14") (pinfunction "1_14") (pintype "bidirectional"))
    )
    (net (code "55") (name "DRIVE18-") (class "Default")
      (node (ref "CN16") (pin "33") (pinfunction "33_33") (pintype "bidirectional"))
      (node (ref "U22") (pin "14") (pinfunction "1_14") (pintype "bidirectional"))
    )
    (net (code "56") (name "DRIVE19+") (class "Default")
      (node (ref "CN16") (pin "7") (pinfunction "7_7") (pintype "bidirectional"))
      (node (ref "U16") (pin "15") (pinfunction "2_15") (pintype "bidirectional"))
    )
    (net (code "57") (name "DRIVE19-") (class "Default")
      (node (ref "CN16") (pin "32") (pinfunction "32_32") (pintype "bidirectional"))
      (node (ref "U22") (pin "15") (pinfunction "2_15") (pintype "bidirectional"))
    )
    (net (code "58") (name "DRIVE20+") (class "Default")
      (node (ref "CN16") (pin "6") (pinfunction "6_6") (pintype "bidirectional"))
      (node (ref "U16") (pin "12") (pinfunction "3_12") (pintype "bidirectional"))
    )
    (net (code "59") (name "DRIVE20-") (class "Default")
      (node (ref "CN16") (pin "31") (pinfunction "31_31") (pintype "bidirectional"))
      (node (ref "U22") (pin "12") (pinfunction "3_12") (pintype "bidirectional"))
    )
    (net (code "60") (name "DRIVE21+") (class "Default")
      (node (ref "CN16") (pin "5") (pinfunction "5_5") (pintype "bidirectional"))
      (node (ref "U16") (pin "1") (pinfunction "4_1") (pintype "bidirectional"))
    )
    (net (code "61") (name "DRIVE21-") (class "Default")
      (node (ref "CN16") (pin "30") (pinfunction "30_30") (pintype "bidirectional"))
      (node (ref "U22") (pin "1") (pinfunction "4_1") (pintype "bidirectional"))
    )
    (net (code "62") (name "DRIVE22+") (class "Default")
      (node (ref "CN16") (pin "4") (pinfunction "4_4") (pintype "bidirectional"))
      (node (ref "U16") (pin "5") (pinfunction "5_5") (pintype "bidirectional"))
    )
    (net (code "63") (name "DRIVE22-") (class "Default")
      (node (ref "CN16") (pin "29") (pinfunction "29_29") (pintype "bidirectional"))
      (node (ref "U22") (pin "5") (pinfunction "5_5") (pintype "bidirectional"))
    )
    (net (code "64") (name "DRIVE23+") (class "Default")
      (node (ref "CN16") (pin "3") (pinfunction "3_3") (pintype "bidirectional"))
      (node (ref "U16") (pin "2") (pinfunction "6_2") (pintype "bidirectional"))
    )
    (net (code "65") (name "DRIVE23-") (class "Default")
      (node (ref "CN16") (pin "28") (pinfunction "28_28") (pintype "bidirectional"))
      (node (ref "U22") (pin "2") (pinfunction "6_2") (pintype "bidirectional"))
    )
    (net (code "66") (name "DRIVE24+") (class "Default")
      (node (ref "CN16") (pin "2") (pinfunction "2_2") (pintype "bidirectional"))
      (node (ref "U16") (pin "4") (pinfunction "7_4") (pintype "bidirectional"))
    )
    (net (code "67") (name "DRIVE24-") (class "Default")
      (node (ref "CN16") (pin "27") (pinfunction "27_27") (pintype "bidirectional"))
      (node (ref "U22") (pin "4") (pinfunction "7_4") (pintype "bidirectional"))
    )
    (net (code "68") (name "DRIVE25+") (class "Default")
      (node (ref "CN17") (pin "25") (pinfunction "25_25") (pintype "bidirectional"))
      (node (ref "U24") (pin "13") (pinfunction "0_13") (pintype "bidirectional"))
    )
    (net (code "69") (name "DRIVE25-") (class "Default")
      (node (ref "CN17") (pin "50") (pinfunction "50_50") (pintype "bidirectional"))
      (node (ref "U17") (pin "13") (pinfunction "0_13") (pintype "bidirectional"))
    )
    (net (code "70") (name "DRIVE26+") (class "Default")
      (node (ref "CN17") (pin "24") (pinfunction "24_24") (pintype "bidirectional"))
      (node (ref "U24") (pin "14") (pinfunction "1_14") (pintype "bidirectional"))
    )
    (net (code "71") (name "DRIVE26-") (class "Default")
      (node (ref "CN17") (pin "49") (pinfunction "49_49") (pintype "bidirectional"))
      (node (ref "U17") (pin "14") (pinfunction "1_14") (pintype "bidirectional"))
    )
    (net (code "72") (name "DRIVE27+") (class "Default")
      (node (ref "CN17") (pin "23") (pinfunction "23_23") (pintype "bidirectional"))
      (node (ref "U24") (pin "15") (pinfunction "2_15") (pintype "bidirectional"))
    )
    (net (code "73") (name "DRIVE27-") (class "Default")
      (node (ref "CN17") (pin "48") (pinfunction "48_48") (pintype "bidirectional"))
      (node (ref "U17") (pin "15") (pinfunction "2_15") (pintype "bidirectional"))
    )
    (net (code "74") (name "DRIVE28+") (class "Default")
      (node (ref "CN17") (pin "22") (pinfunction "22_22") (pintype "bidirectional"))
      (node (ref "U24") (pin "12") (pinfunction "3_12") (pintype "bidirectional"))
    )
    (net (code "75") (name "DRIVE28-") (class "Default")
      (node (ref "CN17") (pin "47") (pinfunction "47_47") (pintype "bidirectional"))
      (node (ref "U17") (pin "12") (pinfunction "3_12") (pintype "bidirectional"))
    )
    (net (code "76") (name "DRIVE29+") (class "Default")
      (node (ref "CN17") (pin "21") (pinfunction "21_21") (pintype "bidirectional"))
      (node (ref "U24") (pin "1") (pinfunction "4_1") (pintype "bidirectional"))
    )
    (net (code "77") (name "DRIVE29-") (class "Default")
      (node (ref "CN17") (pin "46") (pinfunction "46_46") (pintype "bidirectional"))
      (node (ref "U17") (pin "1") (pinfunction "4_1") (pintype "bidirectional"))
    )
    (net (code "78") (name "DRIVE30+") (class "Default")
      (node (ref "CN17") (pin "20") (pinfunction "20_20") (pintype "bidirectional"))
      (node (ref "U24") (pin "5") (pinfunction "5_5") (pintype "bidirectional"))
    )
    (net (code "79") (name "DRIVE30-") (class "Default")
      (node (ref "CN17") (pin "45") (pinfunction "45_45") (pintype "bidirectional"))
      (node (ref "U17") (pin "5") (pinfunction "5_5") (pintype "bidirectional"))
    )
    (net (code "80") (name "DRIVE31+") (class "Default")
      (node (ref "CN17") (pin "19") (pinfunction "19_19") (pintype "bidirectional"))
      (node (ref "U24") (pin "2") (pinfunction "6_2") (pintype "bidirectional"))
    )
    (net (code "81") (name "DRIVE31-") (class "Default")
      (node (ref "CN17") (pin "44") (pinfunction "44_44") (pintype "bidirectional"))
      (node (ref "U17") (pin "2") (pinfunction "6_2") (pintype "bidirectional"))
    )
    (net (code "82") (name "DRIVE32+") (class "Default")
      (node (ref "CN17") (pin "18") (pinfunction "18_18") (pintype "bidirectional"))
      (node (ref "U24") (pin "4") (pinfunction "7_4") (pintype "bidirectional"))
    )
    (net (code "83") (name "DRIVE32-") (class "Default")
      (node (ref "CN17") (pin "43") (pinfunction "43_43") (pintype "bidirectional"))
      (node (ref "U17") (pin "4") (pinfunction "7_4") (pintype "bidirectional"))
    )
    (net (code "84") (name "DRIVE33+") (class "Default")
      (node (ref "CN17") (pin "17") (pinfunction "17_17") (pintype "bidirectional"))
      (node (ref "U13") (pin "13") (pinfunction "0_13") (pintype "bidirectional"))
    )
    (net (code "85") (name "DRIVE33-") (class "Default")
      (node (ref "CN17") (pin "42") (pinfunction "42_42") (pintype "bidirectional"))
      (node (ref "U19") (pin "13") (pinfunction "0_13") (pintype "bidirectional"))
    )
    (net (code "86") (name "DRIVE34+") (class "Default")
      (node (ref "CN17") (pin "16") (pinfunction "16_16") (pintype "bidirectional"))
      (node (ref "U13") (pin "14") (pinfunction "1_14") (pintype "bidirectional"))
    )
    (net (code "87") (name "DRIVE34-") (class "Default")
      (node (ref "CN17") (pin "41") (pinfunction "41_41") (pintype "bidirectional"))
      (node (ref "U19") (pin "14") (pinfunction "1_14") (pintype "bidirectional"))
    )
    (net (code "88") (name "DRIVE35+") (class "Default")
      (node (ref "CN17") (pin "15") (pinfunction "15_15") (pintype "bidirectional"))
      (node (ref "U13") (pin "15") (pinfunction "2_15") (pintype "bidirectional"))
    )
    (net (code "89") (name "DRIVE35-") (class "Default")
      (node (ref "CN17") (pin "40") (pinfunction "40_40") (pintype "bidirectional"))
      (node (ref "U19") (pin "15") (pinfunction "2_15") (pintype "bidirectional"))
    )
    (net (code "90") (name "DRIVE36+") (class "Default")
      (node (ref "CN17") (pin "14") (pinfunction "14_14") (pintype "bidirectional"))
      (node (ref "U13") (pin "12") (pinfunction "3_12") (pintype "bidirectional"))
    )
    (net (code "91") (name "DRIVE36-") (class "Default")
      (node (ref "CN17") (pin "39") (pinfunction "39_39") (pintype "bidirectional"))
      (node (ref "U19") (pin "12") (pinfunction "3_12") (pintype "bidirectional"))
    )
    (net (code "92") (name "DRIVE37+") (class "Default")
      (node (ref "CN17") (pin "13") (pinfunction "13_13") (pintype "bidirectional"))
      (node (ref "U13") (pin "1") (pinfunction "4_1") (pintype "bidirectional"))
    )
    (net (code "93") (name "DRIVE37-") (class "Default")
      (node (ref "CN17") (pin "38") (pinfunction "38_38") (pintype "bidirectional"))
      (node (ref "U19") (pin "1") (pinfunction "4_1") (pintype "bidirectional"))
    )
    (net (code "94") (name "DRIVE38+") (class "Default")
      (node (ref "CN17") (pin "12") (pinfunction "12_12") (pintype "bidirectional"))
      (node (ref "U13") (pin "5") (pinfunction "5_5") (pintype "bidirectional"))
    )
    (net (code "95") (name "DRIVE38-") (class "Default")
      (node (ref "CN17") (pin "37") (pinfunction "37_37") (pintype "bidirectional"))
      (node (ref "U19") (pin "5") (pinfunction "5_5") (pintype "bidirectional"))
    )
    (net (code "96") (name "DRIVE39+") (class "Default")
      (node (ref "CN17") (pin "11") (pinfunction "11_11") (pintype "bidirectional"))
      (node (ref "U13") (pin "2") (pinfunction "6_2") (pintype "bidirectional"))
    )
    (net (code "97") (name "DRIVE39-") (class "Default")
      (node (ref "CN17") (pin "36") (pinfunction "36_36") (pintype "bidirectional"))
      (node (ref "U19") (pin "2") (pinfunction "6_2") (pintype "bidirectional"))
    )
    (net (code "98") (name "DRIVE40+") (class "Default")
      (node (ref "CN17") (pin "10") (pinfunction "10_10") (pintype "bidirectional"))
      (node (ref "U13") (pin "4") (pinfunction "7_4") (pintype "bidirectional"))
    )
    (net (code "99") (name "DRIVE40-") (class "Default")
      (node (ref "CN17") (pin "35") (pinfunction "35_35") (pintype "bidirectional"))
      (node (ref "U19") (pin "4") (pinfunction "7_4") (pintype "bidirectional"))
    )
    (net (code "100") (name "DRIVE41+") (class "Default")
      (node (ref "CN17") (pin "9") (pinfunction "9_9") (pintype "bidirectional"))
      (node (ref "U15") (pin "13") (pinfunction "0_13") (pintype "bidirectional"))
    )
    (net (code "101") (name "DRIVE41-") (class "Default")
      (node (ref "CN17") (pin "34") (pinfunction "34_34") (pintype "bidirectional"))
      (node (ref "U21") (pin "13") (pinfunction "0_13") (pintype "bidirectional"))
    )
    (net (code "102") (name "DRIVE42+") (class "Default")
      (node (ref "CN17") (pin "8") (pinfunction "8_8") (pintype "bidirectional"))
      (node (ref "U15") (pin "14") (pinfunction "1_14") (pintype "bidirectional"))
    )
    (net (code "103") (name "DRIVE42-") (class "Default")
      (node (ref "CN17") (pin "33") (pinfunction "33_33") (pintype "bidirectional"))
      (node (ref "U21") (pin "14") (pinfunction "1_14") (pintype "bidirectional"))
    )
    (net (code "104") (name "DRIVE43+") (class "Default")
      (node (ref "CN17") (pin "7") (pinfunction "7_7") (pintype "bidirectional"))
      (node (ref "U15") (pin "15") (pinfunction "2_15") (pintype "bidirectional"))
    )
    (net (code "105") (name "DRIVE43-") (class "Default")
      (node (ref "CN17") (pin "32") (pinfunction "32_32") (pintype "bidirectional"))
      (node (ref "U21") (pin "15") (pinfunction "2_15") (pintype "bidirectional"))
    )
    (net (code "106") (name "DRIVE44+") (class "Default")
      (node (ref "CN17") (pin "6") (pinfunction "6_6") (pintype "bidirectional"))
      (node (ref "U15") (pin "12") (pinfunction "3_12") (pintype "bidirectional"))
    )
    (net (code "107") (name "DRIVE44-") (class "Default")
      (node (ref "CN17") (pin "31") (pinfunction "31_31") (pintype "bidirectional"))
      (node (ref "U21") (pin "12") (pinfunction "3_12") (pintype "bidirectional"))
    )
    (net (code "108") (name "DRIVE45+") (class "Default")
      (node (ref "CN17") (pin "5") (pinfunction "5_5") (pintype "bidirectional"))
      (node (ref "U15") (pin "1") (pinfunction "4_1") (pintype "bidirectional"))
    )
    (net (code "109") (name "DRIVE45-") (class "Default")
      (node (ref "CN17") (pin "30") (pinfunction "30_30") (pintype "bidirectional"))
      (node (ref "U21") (pin "1") (pinfunction "4_1") (pintype "bidirectional"))
    )
    (net (code "110") (name "DRIVE46+") (class "Default")
      (node (ref "CN17") (pin "4") (pinfunction "4_4") (pintype "bidirectional"))
      (node (ref "U15") (pin "5") (pinfunction "5_5") (pintype "bidirectional"))
    )
    (net (code "111") (name "DRIVE46-") (class "Default")
      (node (ref "CN17") (pin "29") (pinfunction "29_29") (pintype "bidirectional"))
      (node (ref "U21") (pin "5") (pinfunction "5_5") (pintype "bidirectional"))
    )
    (net (code "112") (name "DRIVE47+") (class "Default")
      (node (ref "CN17") (pin "3") (pinfunction "3_3") (pintype "bidirectional"))
      (node (ref "U15") (pin "2") (pinfunction "6_2") (pintype "bidirectional"))
    )
    (net (code "113") (name "DRIVE47-") (class "Default")
      (node (ref "CN17") (pin "28") (pinfunction "28_28") (pintype "bidirectional"))
      (node (ref "U21") (pin "2") (pinfunction "6_2") (pintype "bidirectional"))
    )
    (net (code "114") (name "DRIVE48+") (class "Default")
      (node (ref "CN17") (pin "2") (pinfunction "2_2") (pintype "bidirectional"))
      (node (ref "U15") (pin "4") (pinfunction "7_4") (pintype "bidirectional"))
    )
    (net (code "115") (name "DRIVE48-") (class "Default")
      (node (ref "CN17") (pin "27") (pinfunction "27_27") (pintype "bidirectional"))
      (node (ref "U21") (pin "4") (pinfunction "7_4") (pintype "bidirectional"))
    )
    (net (code "116") (name "DRIVE49+") (class "Default")
      (node (ref "CN16") (pin "1") (pinfunction "1_1") (pintype "bidirectional"))
      (node (ref "U23") (pin "13") (pinfunction "0_13") (pintype "bidirectional"))
    )
    (net (code "117") (name "DRIVE49-") (class "Default")
      (node (ref "CN16") (pin "26") (pinfunction "26_26") (pintype "bidirectional"))
      (node (ref "U25") (pin "13") (pinfunction "0_13") (pintype "bidirectional"))
    )
    (net (code "118") (name "DRIVE50+") (class "Default")
      (node (ref "CN17") (pin "1") (pinfunction "1_1") (pintype "bidirectional"))
      (node (ref "U23") (pin "14") (pinfunction "1_14") (pintype "bidirectional"))
    )
    (net (code "119") (name "DRIVE50-") (class "Default")
      (node (ref "CN17") (pin "26") (pinfunction "26_26") (pintype "bidirectional"))
      (node (ref "U25") (pin "14") (pinfunction "1_14") (pintype "bidirectional"))
    )
    (net (code "120") (name "EXT_IN_+") (class "Default")
      (node (ref "CN2") (pin "1") (pinfunction "1_1") (pintype "bidirectional"))
      (node (ref "CN2") (pin "2") (pinfunction "2_2") (pintype "bidirectional"))
      (node (ref "L2") (pin "4") (pinfunction "2_4") (pintype "passive"))
    )
    (net (code "121") (name "EXT_IN_-") (class "Default")
      (node (ref "CN2") (pin "3") (pinfunction "3_3") (pintype "bidirectional"))
      (node (ref "CN2") (pin "4") (pinfunction "4_4") (pintype "bidirectional"))
      (node (ref "L2") (pin "3") (pinfunction "4_3") (pintype "passive"))
    )
    (net (code "122") (name "EXT{slash}~{INT}") (class "Default")
      (node (ref "R71") (pin "1") (pinfunction "1_1") (pintype "passive"))
      (node (ref "U3") (pin "1") (pinfunction "IN_1") (pintype "input"))
    )
    (net (code "123") (name "FLAME_SYNC") (class "Default")
      (node (ref "U27") (pin "66") (pinfunction "2-11_66") (pintype "bidirectional"))
      (node (ref "U29") (pin "2") (pinfunction "A1_2") (pintype "input"))
      (node (ref "U29") (pin "3") (pinfunction "A2_3") (pintype "input"))
      (node (ref "U29") (pin "4") (pinfunction "A3_4") (pintype "input"))
      (node (ref "U29") (pin "5") (pinfunction "A4_5") (pintype "input"))
    )
    (net (code "124") (name "FSEL") (class "Default")
      (node (ref "CN19") (pin "11") (pinfunction "11_11") (pintype "bidirectional"))
      (node (ref "U27") (pin "71") (pinfunction "2-16_71") (pintype "bidirectional"))
    )
    (net (code "125") (name "FSYNC") (class "Default")
      (node (ref "CN19") (pin "1") (pinfunction "1_1") (pintype "bidirectional"))
      (node (ref "U27") (pin "75") (pinfunction "2-20_75") (pintype "bidirectional"))
    )
    (net (code "126") (name "IOUT+") (class "Default")
      (node (ref "L4") (pin "1") (pinfunction "1_1") (pintype "passive"))
      (node (ref "U12") (pin "3") (pinfunction "COM_3") (pintype "bidirectional"))
      (node (ref "U13") (pin "3") (pinfunction "COM_3") (pintype "bidirectional"))
      (node (ref "U14") (pin "3") (pinfunction "COM_3") (pintype "bidirectional"))
      (node (ref "U15") (pin "3") (pinfunction "COM_3") (pintype "bidirectional"))
      (node (ref "U16") (pin "3") (pinfunction "COM_3") (pintype "bidirectional"))
      (node (ref "U23") (pin "3") (pinfunction "COM_3") (pintype "bidirectional"))
      (node (ref "U24") (pin "3") (pinfunction "COM_3") (pintype "bidirectional"))
    )
    (net (code "127") (name "IOUT-") (class "Default")
      (node (ref "L4") (pin "2") (pinfunction "3_2") (pintype "passive"))
      (node (ref "U17") (pin "3") (pinfunction "COM_3") (pintype "bidirectional"))
      (node (ref "U18") (pin "3") (pinfunction "COM_3") (pintype "bidirectional"))
      (node (ref "U19") (pin "3") (pinfunction "COM_3") (pintype "bidirectional"))
      (node (ref "U20") (pin "3") (pinfunction "COM_3") (pintype "bidirectional"))
      (node (ref "U21") (pin "3") (pinfunction "COM_3") (pintype "bidirectional"))
      (node (ref "U22") (pin "3") (pinfunction "COM_3") (pintype "bidirectional"))
      (node (ref "U25") (pin "3") (pinfunction "COM_3") (pintype "bidirectional"))
    )
    (net (code "128") (name "LED_INT{slash}~{EXT}") (class "Default")
      (node (ref "CN20") (pin "4") (pinfunction "4_4") (pintype "bidirectional"))
      (node (ref "U29") (pin "11") (pinfunction "Y8_11") (pintype "output"))
    )
    (net (code "129") (name "MCLK") (class "Default")
      (node (ref "CN19") (pin "12") (pinfunction "12_12") (pintype "bidirectional"))
      (node (ref "U27") (pin "64") (pinfunction "2-10/CLK3_64") (pintype "bidirectional"))
    )
    (net (code "130") (name "Net-(C2-Pad2)") (class "Default")
      (node (ref "C2") (pin "2") (pinfunction "2_2") (pintype "passive"))
      (node (ref "R5") (pin "2") (pinfunction "2_2") (pintype "passive"))
      (node (ref "R7") (pin "1") (pinfunction "1_1") (pintype "passive"))
    )
    (net (code "131") (name "Net-(CN3-Pad1)") (class "Default")
      (node (ref "CN3") (pin "1") (pinfunction "1_1") (pintype "bidirectional"))
      (node (ref "CN3") (pin "2") (pinfunction "2_2") (pintype "bidirectional"))
      (node (ref "F1") (pin "1") (pinfunction "1_1") (pintype "passive"))
    )
    (net (code "132") (name "Net-(CN4-Pad1)") (class "Default")
      (node (ref "CN4") (pin "1") (pinfunction "1_1") (pintype "bidirectional"))
      (node (ref "CN4") (pin "2") (pinfunction "2_2") (pintype "bidirectional"))
      (node (ref "R58") (pin "2") (pinfunction "2_2") (pintype "passive"))
    )
    (net (code "133") (name "Net-(CN9-Pad1)") (class "Default")
      (node (ref "CN9") (pin "1") (pinfunction "1_1") (pintype "bidirectional"))
      (node (ref "CN9") (pin "2") (pinfunction "2_2") (pintype "bidirectional"))
      (node (ref "F2") (pin "1") (pinfunction "1_1") (pintype "passive"))
    )
    (net (code "134") (name "Net-(CN12-PadP$1)") (class "Default")
      (node (ref "CN12") (pin "P$1") (pinfunction "P$1_P$1") (pintype "bidirectional"))
      (node (ref "CN5") (pin "1") (pinfunction "1_1") (pintype "bidirectional"))
      (node (ref "CN5") (pin "2") (pinfunction "2_2") (pintype "bidirectional"))
    )
    (net (code "135") (name "Net-(CN12-PadP$2)") (class "Default")
      (node (ref "CN12") (pin "P$2") (pinfunction "P$2_P$2") (pintype "bidirectional"))
      (node (ref "CN5") (pin "3") (pinfunction "3_3") (pintype "bidirectional"))
      (node (ref "CN5") (pin "4") (pinfunction "4_4") (pintype "bidirectional"))
    )
    (net (code "136") (name "Net-(CN13-PadP$1)") (class "Default")
      (node (ref "CN13") (pin "P$1") (pinfunction "P$1_P$1") (pintype "bidirectional"))
      (node (ref "CN6") (pin "1") (pinfunction "1_1") (pintype "bidirectional"))
      (node (ref "CN6") (pin "2") (pinfunction "2_2") (pintype "bidirectional"))
    )
    (net (code "137") (name "Net-(CN13-PadP$2)") (class "Default")
      (node (ref "CN13") (pin "P$2") (pinfunction "P$2_P$2") (pintype "bidirectional"))
      (node (ref "CN6") (pin "3") (pinfunction "3_3") (pintype "bidirectional"))
      (node (ref "CN6") (pin "4") (pinfunction "4_4") (pintype "bidirectional"))
    )
    (net (code "138") (name "Net-(CN14-PadP$1)") (class "Default")
      (node (ref "CN14") (pin "P$1") (pinfunction "P$1_P$1") (pintype "bidirectional"))
      (node (ref "CN8") (pin "2") (pinfunction "2_2") (pintype "bidirectional"))
      (node (ref "CN8") (pin "4") (pinfunction "4_4") (pintype "bidirectional"))
    )
    (net (code "139") (name "Net-(CN14-PadP$2)") (class "Default")
      (node (ref "CN14") (pin "P$2") (pinfunction "P$2_P$2") (pintype "bidirectional"))
      (node (ref "CN8") (pin "6") (pinfunction "6_6") (pintype "bidirectional"))
      (node (ref "CN8") (pin "8") (pinfunction "8_8") (pintype "bidirectional"))
    )
    (net (code "140") (name "Net-(CN15-Pad3)") (class "Default")
      (node (ref "CN15") (pin "3") (pinfunction "3_3") (pintype "bidirectional"))
      (node (ref "CN15") (pin "4") (pinfunction "4_4") (pintype "bidirectional"))
      (node (ref "CN9") (pin "3") (pinfunction "3_3") (pintype "bidirectional"))
      (node (ref "CN9") (pin "4") (pinfunction "4_4") (pintype "bidirectional"))
    )
    (net (code "141") (name "Net-(D1-AC)") (class "Default")
      (node (ref "C5") (pin "2") (pinfunction "2_2") (pintype "passive"))
      (node (ref "D1") (pin "3") (pinfunction "AC_3") (pintype "passive"))
      (node (ref "R10") (pin "2") (pinfunction "2_2") (pintype "passive"))
      (node (ref "R15") (pin "1") (pinfunction "1_1") (pintype "passive"))
      (node (ref "U2") (pin "3") (pinfunction "+IN_3") (pintype "input"))
    )
    (net (code "142") (name "Net-(D2-AC)") (class "Default")
      (node (ref "C7") (pin "2") (pinfunction "2_2") (pintype "passive"))
      (node (ref "D2") (pin "3") (pinfunction "AC_3") (pintype "passive"))
      (node (ref "R11") (pin "2") (pinfunction "2_2") (pintype "passive"))
      (node (ref "R16") (pin "1") (pinfunction "1_1") (pintype "passive"))
      (node (ref "U2") (pin "2") (pinfunction "-IN_2") (pintype "input"))
    )
    (net (code "143") (name "Net-(D3-AC)") (class "Default")
      (node (ref "D3") (pin "3") (pinfunction "AC_3") (pintype "passive"))
      (node (ref "R12") (pin "2") (pinfunction "2_2") (pintype "passive"))
      (node (ref "R12") (pin "3") (pinfunction "3_3") (pintype "passive"))
      (node (ref "R17") (pin "1") (pinfunction "1_1") (pintype "passive"))
    )
    (net (code "144") (name "Net-(D4-A1)") (class "Default")
      (node (ref "D4") (pin "A") (pinfunction "A1_A") (pintype "passive"))
      (node (ref "R59") (pin "1") (pinfunction "1_1") (pintype "passive"))
    )
    (net (code "145") (name "Net-(D5-A1)") (class "Default")
      (node (ref "D5") (pin "A") (pinfunction "A1_A") (pintype "passive"))
      (node (ref "R60") (pin "1") (pinfunction "1_1") (pintype "passive"))
    )
    (net (code "146") (name "Net-(D5-K1)") (class "Default")
      (node (ref "CN7") (pin "3") (pinfunction "3_3") (pintype "bidirectional"))
      (node (ref "D5") (pin "C") (pinfunction "K1_C") (pintype "passive"))
    )
    (net (code "147") (name "Net-(D6-A1)") (class "Default")
      (node (ref "D6") (pin "A") (pinfunction "A1_A") (pintype "passive"))
      (node (ref "R61") (pin "1") (pinfunction "1_1") (pintype "passive"))
    )
    (net (code "148") (name "Net-(D6-K1)") (class "Default")
      (node (ref "CN7") (pin "4") (pinfunction "4_4") (pintype "bidirectional"))
      (node (ref "D6") (pin "C") (pinfunction "K1_C") (pintype "passive"))
    )
    (net (code "149") (name "Net-(L1-2)") (class "Default")
      (node (ref "CN1") (pin "1") (pinfunction "1_1") (pintype "bidirectional"))
      (node (ref "CN1") (pin "2") (pinfunction "2_2") (pintype "bidirectional"))
      (node (ref "L1") (pin "4") (pinfunction "2_4") (pintype "passive"))
    )
    (net (code "150") (name "Net-(L1-3)") (class "Default")
      (node (ref "L1") (pin "2") (pinfunction "3_2") (pintype "passive"))
      (node (ref "R9") (pin "1") (pinfunction "1_1") (pintype "passive"))
    )
    (net (code "151") (name "Net-(L1-4)") (class "Default")
      (node (ref "CN1") (pin "3") (pinfunction "3_3") (pintype "bidirectional"))
      (node (ref "CN1") (pin "4") (pinfunction "4_4") (pintype "bidirectional"))
      (node (ref "L1") (pin "3") (pinfunction "4_3") (pintype "passive"))
    )
    (net (code "152") (name "Net-(L1-Pad1)") (class "Default")
      (node (ref "L1") (pin "1") (pinfunction "1_1") (pintype "passive"))
      (node (ref "R8") (pin "1") (pinfunction "1_1") (pintype "passive"))
    )
    (net (code "153") (name "Net-(L2-3)") (class "Default")
      (node (ref "L2") (pin "2") (pinfunction "3_2") (pintype "passive"))
      (node (ref "R11") (pin "1") (pinfunction "1_1") (pintype "passive"))
    )
    (net (code "154") (name "Net-(L2-Pad1)") (class "Default")
      (node (ref "L2") (pin "1") (pinfunction "1_1") (pintype "passive"))
      (node (ref "R10") (pin "1") (pinfunction "1_1") (pintype "passive"))
    )
    (net (code "155") (name "Net-(L4-2)") (class "Default")
      (node (ref "L4") (pin "4") (pinfunction "2_4") (pintype "passive"))
      (node (ref "R51") (pin "2") (pinfunction "2_2") (pintype "passive"))
      (node (ref "R52") (pin "2") (pinfunction "2_2") (pintype "passive"))
      (node (ref "R53") (pin "2") (pinfunction "2_2") (pintype "passive"))
      (node (ref "R54") (pin "2") (pinfunction "2_2") (pintype "passive"))
      (node (ref "TP2") (pin "1") (pinfunction "MP_1") (pintype "passive"))
    )
    (net (code "156") (name "Net-(L4-4)") (class "Default")
      (node (ref "L4") (pin "3") (pinfunction "4_3") (pintype "passive"))
      (node (ref "R56") (pin "2") (pinfunction "2_2") (pintype "passive"))
      (node (ref "TP6") (pin "1") (pinfunction "MP_1") (pintype "passive"))
      (node (ref "U11") (pin "4") (pinfunction "+IN_4") (pintype "input"))
    )
    (net (code "157") (name "Net-(R1-Pad2)") (class "Default")
      (node (ref "R1") (pin "2") (pinfunction "2_2") (pintype "passive"))
      (node (ref "R2") (pin "3") (pinfunction "3_3") (pintype "passive"))
    )
    (net (code "158") (name "Net-(R2-Pad1)") (class "Default")
      (node (ref "R2") (pin "1") (pinfunction "1_1") (pintype "passive"))
      (node (ref "R4") (pin "1") (pinfunction "1_1") (pintype "passive"))
    )
    (net (code "159") (name "Net-(R3-Pad2)") (class "Default")
      (node (ref "R3") (pin "2") (pinfunction "2_2") (pintype "passive"))
      (node (ref "R5") (pin "1") (pinfunction "1_1") (pintype "passive"))
    )
    (net (code "160") (name "Net-(R12-Pad1)") (class "Default")
      (node (ref "R12") (pin "1") (pinfunction "1_1") (pintype "passive"))
      (node (ref "R7") (pin "2") (pinfunction "2_2") (pintype "passive"))
    )
    (net (code "161") (name "Net-(R23-Pad1)") (class "Default")
      (node (ref "R23") (pin "1") (pinfunction "1_1") (pintype "passive"))
      (node (ref "R24") (pin "2") (pinfunction "2_2") (pintype "passive"))
    )
    (net (code "162") (name "Net-(SW1A-C)") (class "Default")
      (node (ref "CN15") (pin "1") (pinfunction "1_1") (pintype "bidirectional"))
      (node (ref "CN15") (pin "2") (pinfunction "2_2") (pintype "bidirectional"))
      (node (ref "SW1") (pin "2") (pinfunction "C_2") (pintype "passive"))
    )
    (net (code "163") (name "Net-(SW1A-NC)") (class "Default")
      (node (ref "F2") (pin "2") (pinfunction "2_2") (pintype "passive"))
      (node (ref "SW1") (pin "3") (pinfunction "NC_3") (pintype "passive"))
    )
    (net (code "164") (name "Net-(TP1-MP)") (class "Default")
      (node (ref "R44") (pin "2") (pinfunction "2_2") (pintype "passive"))
      (node (ref "TP1") (pin "1") (pinfunction "MP_1") (pintype "passive"))
      (node (ref "U8") (pin "1") (pinfunction "OUT_1") (pintype "output"))
      (node (ref "U9") (pin "6") (pinfunction "COM_6") (pintype "bidirectional"))
    )
    (net (code "165") (name "Net-(TP3-MP)") (class "Default")
      (node (ref "C14") (pin "1") (pinfunction "1_1") (pintype "passive"))
      (node (ref "R35") (pin "2") (pinfunction "2_2") (pintype "passive"))
      (node (ref "R37") (pin "1") (pinfunction "1_1") (pintype "passive"))
      (node (ref "R38") (pin "1") (pinfunction "1_1") (pintype "passive"))
      (node (ref "TP3") (pin "1") (pinfunction "MP_1") (pintype "passive"))
    )
    (net (code "166") (name "Net-(TP4-MP)") (class "Default")
      (node (ref "C19") (pin "1") (pinfunction "1_1") (pintype "passive"))
      (node (ref "R45") (pin "2") (pinfunction "2_2") (pintype "passive"))
      (node (ref "TP4") (pin "1") (pinfunction "MP_1") (pintype "passive"))
      (node (ref "U8") (pin "7") (pinfunction "OUT_7") (pintype "output"))
      (node (ref "U9") (pin "10") (pinfunction "COM_10") (pintype "bidirectional"))
    )
    (net (code "167") (name "Net-(TP5-MP)") (class "Default")
      (node (ref "R27") (pin "1") (pinfunction "1_1") (pintype "passive"))
      (node (ref "TP5") (pin "1") (pinfunction "MP_1") (pintype "passive"))
      (node (ref "U3") (pin "10") (pinfunction "COM_10") (pintype "bidirectional"))
      (node (ref "U7") (pin "1") (pinfunction "-IN_1") (pintype "input"))
    )
    (net (code "168") (name "Net-(U1A-+IN)") (class "Default")
      (node (ref "C1") (pin "1") (pinfunction "1_1") (pintype "passive"))
      (node (ref "R3") (pin "1") (pinfunction "1_1") (pintype "passive"))
      (node (ref "U1") (pin "3") (pinfunction "+IN_3") (pintype "input"))
    )
    (net (code "169") (name "Net-(U1A--IN)") (class "Default")
      (node (ref "R2") (pin "2") (pinfunction "2_2") (pintype "passive"))
      (node (ref "U1") (pin "2") (pinfunction "-IN_2") (pintype "input"))
    )
    (net (code "170") (name "Net-(U1A-OUT)") (class "Default")
      (node (ref "C2") (pin "1") (pinfunction "1_1") (pintype "passive"))
      (node (ref "R4") (pin "2") (pinfunction "2_2") (pintype "passive"))
      (node (ref "R6") (pin "1") (pinfunction "1_1") (pintype "passive"))
      (node (ref "U1") (pin "1") (pinfunction "OUT_1") (pintype "output"))
    )
    (net (code "171") (name "Net-(U1B--IN)") (class "Default")
      (node (ref "C6") (pin "2") (pinfunction "2_2") (pintype "passive"))
      (node (ref "R6") (pin "2") (pinfunction "2_2") (pintype "passive"))
      (node (ref "U1") (pin "6") (pinfunction "-IN_6") (pintype "input"))
    )
    (net (code "172") (name "Net-(U1B-OUT)") (class "Default")
      (node (ref "C6") (pin "1") (pinfunction "1_1") (pintype "passive"))
      (node (ref "R17") (pin "2") (pinfunction "2_2") (pintype "passive"))
      (node (ref "R19") (pin "1") (pinfunction "1_1") (pintype "passive"))
      (node (ref "U1") (pin "7") (pinfunction "OUT_7") (pintype "output"))
    )
    (net (code "173") (name "Net-(U2A-OUT)") (class "Default")
      (node (ref "C7") (pin "1") (pinfunction "1_1") (pintype "passive"))
      (node (ref "R16") (pin "2") (pinfunction "2_2") (pintype "passive"))
      (node (ref "R20") (pin "1") (pinfunction "1_1") (pintype "passive"))
      (node (ref "U2") (pin "1") (pinfunction "OUT_1") (pintype "output"))
    )
    (net (code "174") (name "Net-(U2B-+IN)") (class "Default")
      (node (ref "C3") (pin "2") (pinfunction "2_2") (pintype "passive"))
      (node (ref "R13") (pin "1") (pinfunction "1_1") (pintype "passive"))
      (node (ref "R8") (pin "2") (pinfunction "2_2") (pintype "passive"))
      (node (ref "U2") (pin "5") (pinfunction "+IN_5") (pintype "input"))
    )
    (net (code "175") (name "Net-(U2B--IN)") (class "Default")
      (node (ref "C4") (pin "2") (pinfunction "2_2") (pintype "passive"))
      (node (ref "R14") (pin "1") (pinfunction "1_1") (pintype "passive"))
      (node (ref "R9") (pin "2") (pinfunction "2_2") (pintype "passive"))
      (node (ref "U2") (pin "6") (pinfunction "-IN_6") (pintype "input"))
    )
    (net (code "176") (name "Net-(U2B-OUT)") (class "Default")
      (node (ref "C4") (pin "1") (pinfunction "1_1") (pintype "passive"))
      (node (ref "R14") (pin "2") (pinfunction "2_2") (pintype "passive"))
      (node (ref "R18") (pin "1") (pinfunction "1_1") (pintype "passive"))
      (node (ref "U2") (pin "7") (pinfunction "OUT_7") (pintype "output"))
    )
    (net (code "177") (name "Net-(U3A-NC)") (class "Default")
      (node (ref "U3") (pin "6") (pinfunction "COM_6") (pintype "bidirectional"))
      (node (ref "U3") (pin "9") (pinfunction "NC_9") (pintype "bidirectional"))
    )
    (net (code "178") (name "Net-(U3A-NO)") (class "Default")
      (node (ref "R20") (pin "2") (pinfunction "2_2") (pintype "passive"))
      (node (ref "U3") (pin "2") (pinfunction "NO_2") (pintype "bidirectional"))
    )
    (net (code "179") (name "Net-(U3B-NC)") (class "Default")
      (node (ref "R18") (pin "2") (pinfunction "2_2") (pintype "passive"))
      (node (ref "U3") (pin "7") (pinfunction "NC_7") (pintype "bidirectional"))
    )
    (net (code "180") (name "Net-(U3B-NO)") (class "Default")
      (node (ref "R19") (pin "2") (pinfunction "2_2") (pintype "passive"))
      (node (ref "U3") (pin "4") (pinfunction "NO_4") (pintype "bidirectional"))
    )
    (net (code "181") (name "Net-(U4-EN)") (class "Default")
      (node (ref "R26") (pin "2") (pinfunction "2_2") (pintype "passive"))
      (node (ref "U4") (pin "3") (pinfunction "EN_3") (pintype "input"))
    )
    (net (code "182") (name "Net-(U4-NR)") (class "Default")
      (node (ref "C12") (pin "1") (pinfunction "1_1") (pintype "passive"))
      (node (ref "U4") (pin "4") (pinfunction "NR_4") (pintype "passive"))
    )
    (net (code "183") (name "Net-(U5A-+IN)") (class "Default")
      (node (ref "R27") (pin "2") (pinfunction "2_2") (pintype "passive"))
      (node (ref "R29") (pin "2") (pinfunction "2_2") (pintype "passive"))
      (node (ref "U5") (pin "3") (pinfunction "+IN_3") (pintype "input"))
    )
    (net (code "184") (name "Net-(U5A-OUT)") (class "Default")
      (node (ref "C14") (pin "2") (pinfunction "2_2") (pintype "passive"))
      (node (ref "R33") (pin "2") (pinfunction "2_2") (pintype "passive"))
      (node (ref "R35") (pin "1") (pinfunction "1_1") (pintype "passive"))
      (node (ref "U5") (pin "1") (pinfunction "OUT_1") (pintype "output"))
    )
    (net (code "185") (name "Net-(U5B-+IN)") (class "Default")
      (node (ref "C20") (pin "1") (pinfunction "1_1") (pintype "passive"))
      (node (ref "R42") (pin "1") (pinfunction "1_1") (pintype "passive"))
      (node (ref "R43") (pin "2") (pinfunction "2_2") (pintype "passive"))
      (node (ref "U5") (pin "5") (pinfunction "+IN_5") (pintype "input"))
    )
    (net (code "186") (name "Net-(U6-CT)") (class "Default")
      (node (ref "C11") (pin "1") (pinfunction "1_1") (pintype "passive"))
      (node (ref "U6") (pin "4") (pinfunction "CT_4") (pintype "passive"))
    )
    (net (code "187") (name "Net-(U6-SENSE)") (class "Default")
      (node (ref "C10") (pin "1") (pinfunction "1_1") (pintype "passive"))
      (node (ref "R24") (pin "1") (pinfunction "1_1") (pintype "passive"))
      (node (ref "R25") (pin "2") (pinfunction "2_2") (pintype "passive"))
      (node (ref "U6") (pin "5") (pinfunction "SENSE_5") (pintype "bidirectional"))
    )
    (net (code "188") (name "Net-(U7-+IN)") (class "Default")
      (node (ref "R31") (pin "1") (pinfunction "1_1") (pintype "passive"))
      (node (ref "R32") (pin "2") (pinfunction "2_2") (pintype "passive"))
      (node (ref "R34") (pin "1") (pinfunction "1_1") (pintype "passive"))
      (node (ref "U7") (pin "3") (pinfunction "+IN_3") (pintype "input"))
    )
    (net (code "189") (name "Net-(U7-OUT)") (class "Default")
      (node (ref "R34") (pin "2") (pinfunction "2_2") (pintype "passive"))
      (node (ref "R39") (pin "1") (pinfunction "1_1") (pintype "passive"))
      (node (ref "U7") (pin "4") (pinfunction "OUT_4") (pintype "output"))
    )
    (net (code "190") (name "Net-(U8A-+IN)") (class "Default")
      (node (ref "C17") (pin "1") (pinfunction "1_1") (pintype "passive"))
      (node (ref "R37") (pin "2") (pinfunction "2_2") (pintype "passive"))
      (node (ref "R41") (pin "2") (pinfunction "2_2") (pintype "passive"))
      (node (ref "U8") (pin "3") (pinfunction "+IN_3") (pintype "input"))
    )
    (net (code "191") (name "Net-(U8A--IN)") (class "Default")
      (node (ref "R40") (pin "2") (pinfunction "2_2") (pintype "passive"))
      (node (ref "R44") (pin "1") (pinfunction "1_1") (pintype "passive"))
      (node (ref "U8") (pin "2") (pinfunction "-IN_2") (pintype "input"))
    )
    (net (code "192") (name "Net-(U8B--IN)") (class "Default")
      (node (ref "C19") (pin "2") (pinfunction "2_2") (pintype "passive"))
      (node (ref "R38") (pin "2") (pinfunction "2_2") (pintype "passive"))
      (node (ref "R45") (pin "1") (pinfunction "1_1") (pintype "passive"))
      (node (ref "U8") (pin "6") (pinfunction "-IN_6") (pintype "input"))
    )
    (net (code "193") (name "Net-(U9A-NC)") (class "Default")
      (node (ref "R47") (pin "1") (pinfunction "1_1") (pintype "passive"))
      (node (ref "R48") (pin "1") (pinfunction "1_1") (pintype "passive"))
      (node (ref "U9") (pin "9") (pinfunction "NC_9") (pintype "bidirectional"))
    )
    (net (code "194") (name "Net-(U9A-NO)") (class "Default")
      (node (ref "R49") (pin "1") (pinfunction "1_1") (pintype "passive"))
      (node (ref "R50") (pin "1") (pinfunction "1_1") (pintype "passive"))
      (node (ref "U9") (pin "2") (pinfunction "NO_2") (pintype "bidirectional"))
    )
    (net (code "195") (name "Net-(U9B-NC)") (class "Default")
      (node (ref "R51") (pin "1") (pinfunction "1_1") (pintype "passive"))
      (node (ref "R52") (pin "1") (pinfunction "1_1") (pintype "passive"))
      (node (ref "U9") (pin "7") (pinfunction "NC_7") (pintype "bidirectional"))
    )
    (net (code "196") (name "Net-(U9B-NO)") (class "Default")
      (node (ref "R53") (pin "1") (pinfunction "1_1") (pintype "passive"))
      (node (ref "R54") (pin "1") (pinfunction "1_1") (pintype "passive"))
      (node (ref "U9") (pin "4") (pinfunction "NO_4") (pintype "bidirectional"))
    )
    (net (code "197") (name "Net-(U10C-0)") (class "Default")
      (node (ref "R30") (pin "2") (pinfunction "2_2") (pintype "passive"))
      (node (ref "R33") (pin "1") (pinfunction "1_1") (pintype "passive"))
      (node (ref "U10") (pin "12") (pinfunction "0_12") (pintype "bidirectional"))
    )
    (net (code "198") (name "Net-(U10C-1)") (class "Default")
      (node (ref "R28") (pin "2") (pinfunction "2_2") (pintype "passive"))
      (node (ref "R30") (pin "1") (pinfunction "1_1") (pintype "passive"))
      (node (ref "U10") (pin "14") (pinfunction "1_14") (pintype "bidirectional"))
    )
    (net (code "199") (name "Net-(U10C-2)") (class "Default")
      (node (ref "R22") (pin "2") (pinfunction "2_2") (pintype "passive"))
      (node (ref "R28") (pin "1") (pinfunction "1_1") (pintype "passive"))
      (node (ref "U10") (pin "15") (pinfunction "2_15") (pintype "bidirectional"))
    )
    (net (code "200") (name "Net-(U10C-3)") (class "Default")
      (node (ref "R21") (pin "2") (pinfunction "2_2") (pintype "passive"))
      (node (ref "R22") (pin "1") (pinfunction "1_1") (pintype "passive"))
      (node (ref "U10") (pin "11") (pinfunction "3_11") (pintype "bidirectional"))
    )
    (net (code "201") (name "Net-(U10C-COM)") (class "Default")
      (node (ref "U10") (pin "13") (pinfunction "COM_13") (pintype "bidirectional"))
      (node (ref "U5") (pin "2") (pinfunction "-IN_2") (pintype "input"))
    )
    (net (code "202") (name "Net-(U11--IN)") (class "Default")
      (node (ref "R47") (pin "2") (pinfunction "2_2") (pintype "passive"))
      (node (ref "R48") (pin "2") (pinfunction "2_2") (pintype "passive"))
      (node (ref "R49") (pin "2") (pinfunction "2_2") (pintype "passive"))
      (node (ref "R50") (pin "2") (pinfunction "2_2") (pintype "passive"))
      (node (ref "R56") (pin "1") (pinfunction "1_1") (pintype "passive"))
      (node (ref "U11") (pin "1") (pinfunction "-IN_1") (pintype "input"))
    )
    (net (code "203") (name "Net-(U11-REF)") (class "Default")
      (node (ref "R46") (pin "1") (pinfunction "1_1") (pintype "passive"))
      (node (ref "U11") (pin "6") (pinfunction "REF_6") (pintype "passive"))
      (node (ref "U5") (pin "6") (pinfunction "-IN_6") (pintype "input"))
      (node (ref "U5") (pin "7") (pinfunction "OUT_7") (pintype "output"))
    )
    (net (code "204") (name "Net-(U11-RG1)") (class "Default")
      (node (ref "R55") (pin "2") (pinfunction "2_2") (pintype "passive"))
      (node (ref "R57") (pin "2") (pinfunction "2_2") (pintype "passive"))
      (node (ref "U11") (pin "2") (pinfunction "RG1_2") (pintype "passive"))
    )
    (net (code "205") (name "Net-(U11-RG2)") (class "Default")
      (node (ref "R55") (pin "1") (pinfunction "1_1") (pintype "passive"))
      (node (ref "R57") (pin "1") (pinfunction "1_1") (pintype "passive"))
      (node (ref "U11") (pin "3") (pinfunction "RG2_3") (pintype "passive"))
    )
    (net (code "206") (name "Net-(U26-EN)") (class "Default")
      (node (ref "R64") (pin "2") (pinfunction "2_2") (pintype "passive"))
      (node (ref "U26") (pin "3") (pinfunction "EN_3") (pintype "input"))
    )
    (net (code "207") (name "Net-(U26-NR)") (class "Default")
      (node (ref "C52") (pin "1") (pinfunction "1_1") (pintype "passive"))
      (node (ref "U26") (pin "4") (pinfunction "NR_4") (pintype "passive"))
    )
    (net (code "208") (name "Net-(U27A-TCK)") (class "Default")
      (node (ref "CN18") (pin "1") (pinfunction "1_1") (pintype "bidirectional"))
      (node (ref "R65") (pin "2") (pinfunction "2_2") (pintype "passive"))
      (node (ref "U27") (pin "24") (pinfunction "TCK_24") (pintype "bidirectional"))
    )
    (net (code "209") (name "Net-(U27A-TDI)") (class "Default")
      (node (ref "CN18") (pin "9") (pinfunction "9_9") (pintype "bidirectional"))
      (node (ref "R66") (pin "1") (pinfunction "1_1") (pintype "passive"))
      (node (ref "U27") (pin "23") (pinfunction "TDI_23") (pintype "bidirectional"))
    )
    (net (code "210") (name "Net-(U27A-TDO)") (class "Default")
      (node (ref "CN18") (pin "3") (pinfunction "3_3") (pintype "bidirectional"))
      (node (ref "R62") (pin "1") (pinfunction "1_1") (pintype "passive"))
      (node (ref "U27") (pin "25") (pinfunction "TDO_25") (pintype "bidirectional"))
    )
    (net (code "211") (name "Net-(U27A-TMS)") (class "Default")
      (node (ref "CN18") (pin "5") (pinfunction "5_5") (pintype "bidirectional"))
      (node (ref "R63") (pin "1") (pinfunction "1_1") (pintype "passive"))
      (node (ref "U27") (pin "22") (pinfunction "TMS_22") (pintype "bidirectional"))
    )
    (net (code "212") (name "Net-(U27B-1-9{slash}CLK1)") (class "Default")
      (node (ref "R67") (pin "2") (pinfunction "2_2") (pintype "passive"))
      (node (ref "U27") (pin "14") (pinfunction "1-9/CLK1_14") (pintype "bidirectional"))
    )
    (net (code "213") (name "Net-(U27B-1-10)") (class "Default")
      (node (ref "R69") (pin "2") (pinfunction "2_2") (pintype "passive"))
      (node (ref "U27") (pin "15") (pinfunction "1-10_15") (pintype "bidirectional"))
    )
    (net (code "214") (name "Net-(U27B-1-11)") (class "Default")
      (node (ref "R68") (pin "2") (pinfunction "2_2") (pintype "passive"))
      (node (ref "U27") (pin "16") (pinfunction "1-11_16") (pintype "bidirectional"))
    )
    (net (code "215") (name "Net-(U27B-1-17)") (class "Default")
      (node (ref "R70") (pin "2") (pinfunction "2_2") (pintype "passive"))
      (node (ref "U27") (pin "26") (pinfunction "1-17_26") (pintype "bidirectional"))
    )
    (net (code "216") (name "Net-(U27B-1-18)") (class "Default")
      (node (ref "R71") (pin "2") (pinfunction "2_2") (pintype "passive"))
      (node (ref "U27") (pin "27") (pinfunction "1-18_27") (pintype "bidirectional"))
    )
    (net (code "217") (name "Net-(U28-NR)") (class "Default")
      (node (ref "C56") (pin "1") (pinfunction "1_1") (pintype "passive"))
      (node (ref "U28") (pin "4") (pinfunction "NR_4") (pintype "passive"))
    )
    (net (code "218") (name "Net-(U29A-Y1)") (class "Default")
      (node (ref "R83") (pin "1") (pinfunction "1_1") (pintype "passive"))
      (node (ref "U29") (pin "18") (pinfunction "Y1_18") (pintype "output"))
    )
    (net (code "219") (name "Net-(U29A-Y2)") (class "Default")
      (node (ref "R84") (pin "1") (pinfunction "1_1") (pintype "passive"))
      (node (ref "U29") (pin "17") (pinfunction "Y2_17") (pintype "output"))
    )
    (net (code "220") (name "Net-(U29A-~{G})") (class "Default")
      (node (ref "R77") (pin "2") (pinfunction "2_2") (pintype "passive"))
      (node (ref "U29") (pin "19") (pinfunction "~{G}_19") (pintype "input"))
    )
    (net (code "221") (name "Net-(U30-A)") (class "Default")
      (node (ref "R84") (pin "2") (pinfunction "2_2") (pintype "passive"))
      (node (ref "U30") (pin "1") (pinfunction "A_1") (pintype "passive"))
    )
    (net (code "222") (name "PSEL") (class "Default")
      (node (ref "CN19") (pin "13") (pinfunction "13_13") (pintype "bidirectional"))
      (node (ref "U27") (pin "70") (pinfunction "2-15_70") (pintype "bidirectional"))
    )
    (net (code "223") (name "RESET") (class "Default")
      (node (ref "CN19") (pin "9") (pinfunction "9_9") (pintype "bidirectional"))
      (node (ref "U27") (pin "72") (pinfunction "2-17_72") (pintype "bidirectional"))
    )
    (net (code "224") (name "SCLK") (class "Default")
      (node (ref "CN19") (pin "3") (pinfunction "3_3") (pintype "bidirectional"))
      (node (ref "U27") (pin "74") (pinfunction "2-19_74") (pintype "bidirectional"))
    )
    (net (code "225") (name "SDATA") (class "Default")
      (node (ref "CN19") (pin "5") (pinfunction "5_5") (pintype "bidirectional"))
      (node (ref "U27") (pin "73") (pinfunction "2-18_73") (pintype "bidirectional"))
    )
    (net (code "226") (name "SW1") (class "Default")
      (node (ref "C61") (pin "1") (pinfunction "1_1") (pintype "passive"))
      (node (ref "R81") (pin "1") (pinfunction "1_1") (pintype "passive"))
      (node (ref "U27") (pin "52") (pinfunction "2-1_52") (pintype "bidirectional"))
    )
    (net (code "227") (name "SW2") (class "Default")
      (node (ref "C60") (pin "1") (pinfunction "1_1") (pintype "passive"))
      (node (ref "R80") (pin "1") (pinfunction "1_1") (pintype "passive"))
      (node (ref "U27") (pin "53") (pinfunction "2-2_53") (pintype "bidirectional"))
    )
    (net (code "228") (name "SW3") (class "Default")
      (node (ref "C59") (pin "1") (pinfunction "1_1") (pintype "passive"))
      (node (ref "R79") (pin "1") (pinfunction "1_1") (pintype "passive"))
      (node (ref "U27") (pin "54") (pinfunction "2-3_54") (pintype "bidirectional"))
    )
    (net (code "229") (name "SW4") (class "Default")
      (node (ref "C58") (pin "1") (pinfunction "1_1") (pintype "passive"))
      (node (ref "R78") (pin "1") (pinfunction "1_1") (pintype "passive"))
      (node (ref "U27") (pin "55") (pinfunction "2-4_55") (pintype "bidirectional"))
    )
    (net (code "230") (name "SW5") (class "Default")
      (node (ref "C62") (pin "1") (pinfunction "1_1") (pintype "passive"))
      (node (ref "R82") (pin "1") (pinfunction "1_1") (pintype "passive"))
      (node (ref "U27") (pin "51") (pinfunction "1-38_51") (pintype "bidirectional"))
    )
    (net (code "231") (name "SW_DDS{slash}~{ANALOG}") (class "Default")
      (node (ref "CN20") (pin "13") (pinfunction "13_13") (pintype "bidirectional"))
      (node (ref "R76") (pin "1") (pinfunction "1_1") (pintype "passive"))
      (node (ref "R82") (pin "2") (pinfunction "2_2") (pintype "passive"))
    )
    (net (code "232") (name "SW_INT{slash}~{EXT}") (class "Default")
      (node (ref "CN20") (pin "12") (pinfunction "12_12") (pintype "bidirectional"))
      (node (ref "R75") (pin "1") (pinfunction "1_1") (pintype "passive"))
      (node (ref "R81") (pin "2") (pinfunction "2_2") (pintype "passive"))
    )
    (net (code "233") (name "SW_X1{slash}~{X2}") (class "Default")
      (node (ref "CN20") (pin "11") (pinfunction "11_11") (pintype "bidirectional"))
      (node (ref "R74") (pin "1") (pinfunction "1_1") (pintype "passive"))
      (node (ref "R80") (pin "2") (pinfunction "2_2") (pintype "passive"))
    )
    (net (code "234") (name "SW_X1{slash}~{X10}") (class "Default")
      (node (ref "CN20") (pin "10") (pinfunction "10_10") (pintype "bidirectional"))
      (node (ref "R73") (pin "1") (pinfunction "1_1") (pintype "passive"))
      (node (ref "R79") (pin "2") (pinfunction "2_2") (pintype "passive"))
    )
    (net (code "235") (name "SW_~{TEST}") (class "Default")
      (node (ref "CN20") (pin "9") (pinfunction "9_9") (pintype "bidirectional"))
      (node (ref "R72") (pin "1") (pinfunction "1_1") (pintype "passive"))
      (node (ref "R78") (pin "2") (pinfunction "2_2") (pintype "passive"))
    )
    (net (code "236") (name "SYNC_ISO_C") (class "Default")
      (node (ref "CN20") (pin "5") (pinfunction "5_5") (pintype "bidirectional"))
      (node (ref "U30") (pin "4") (pinfunction "COL_4") (pintype "passive"))
    )
    (net (code "237") (name "SYNC_ISO_E") (class "Default")
      (node (ref "CN20") (pin "6") (pinfunction "6_6") (pintype "bidirectional"))
      (node (ref "U30") (pin "3") (pinfunction "EMI_3") (pintype "passive"))
    )
    (net (code "238") (name "SYNC_OSC") (class "Default")
      (node (ref "R39") (pin "2") (pinfunction "2_2") (pintype "passive"))
      (node (ref "TP8") (pin "1") (pinfunction "MP_1") (pintype "passive"))
      (node (ref "U27") (pin "18") (pinfunction "1-13_18") (pintype "bidirectional"))
    )
    (net (code "239") (name "SYNC_OUT") (class "Default")
      (node (ref "CN20") (pin "7") (pinfunction "7_7") (pintype "bidirectional"))
      (node (ref "R83") (pin "2") (pinfunction "2_2") (pintype "passive"))
    )
    (net (code "240") (name "UI_DDS{slash}~{ANALOG}") (class "Default")
      (node (ref "CN11") (pin "2") (pinfunction "2_2") (pintype "bidirectional"))
      (node (ref "CN11") (pin "3") (pinfunction "3_3") (pintype "bidirectional"))
      (node (ref "CN7") (pin "13") (pinfunction "13_13") (pintype "bidirectional"))
    )
    (net (code "241") (name "UI_INT{slash}~{EXT}") (class "Default")
      (node (ref "CN7") (pin "12") (pinfunction "12_12") (pintype "bidirectional"))
      (node (ref "SW4") (pin "2") (pinfunction "C_2") (pintype "passive"))
    )
    (net (code "242") (name "UI_SYNC_C") (class "Default")
      (node (ref "CN7") (pin "5") (pinfunction "5_5") (pintype "bidirectional"))
      (node (ref "CN8") (pin "1") (pinfunction "1_1") (pintype "bidirectional"))
    )
    (net (code "243") (name "UI_SYNC_E") (class "Default")
      (node (ref "CN7") (pin "6") (pinfunction "6_6") (pintype "bidirectional"))
      (node (ref "CN8") (pin "5") (pinfunction "5_5") (pintype "bidirectional"))
    )
    (net (code "244") (name "UI_SYNC_N") (class "Default")
      (node (ref "CN7") (pin "8") (pinfunction "8_8") (pintype "bidirectional"))
      (node (ref "CN8") (pin "7") (pinfunction "7_7") (pintype "bidirectional"))
    )
    (net (code "245") (name "UI_SYNC_P") (class "Default")
      (node (ref "CN7") (pin "7") (pinfunction "7_7") (pintype "bidirectional"))
      (node (ref "CN8") (pin "3") (pinfunction "3_3") (pintype "bidirectional"))
    )
    (net (code "246") (name "UI_VD+3V3") (class "Default")
      (node (ref "CN7") (pin "1") (pinfunction "1_1") (pintype "bidirectional"))
      (node (ref "R59") (pin "2") (pinfunction "2_2") (pintype "passive"))
      (node (ref "R60") (pin "2") (pinfunction "2_2") (pintype "passive"))
      (node (ref "R61") (pin "2") (pinfunction "2_2") (pintype "passive"))
    )
    (net (code "247") (name "UI_X1{slash}~{X2}") (class "Default")
      (node (ref "CN7") (pin "11") (pinfunction "11_11") (pintype "bidirectional"))
      (node (ref "SW3") (pin "2") (pinfunction "C_2") (pintype "passive"))
    )
    (net (code "248") (name "UI_X1{slash}~{X10}") (class "Default")
      (node (ref "CN7") (pin "10") (pinfunction "10_10") (pintype "bidirectional"))
      (node (ref "SW2") (pin "2") (pinfunction "C_2") (pintype "passive"))
    )
    (net (code "249") (name "UI_~{TEST}") (class "Default")
      (node (ref "CN10") (pin "2") (pinfunction "2_2") (pintype "bidirectional"))
      (node (ref "CN10") (pin "3") (pinfunction "3_3") (pintype "bidirectional"))
      (node (ref "CN7") (pin "9") (pinfunction "9_9") (pintype "bidirectional"))
    )
    (net (code "250") (name "VA+3V3") (class "Default")
      (node (ref "C13") (pin "1") (pinfunction "1_1") (pintype "passive"))
      (node (ref "C15") (pin "2") (pinfunction "2_2") (pintype "passive"))
      (node (ref "C16") (pin "1") (pinfunction "1_1") (pintype "passive"))
      (node (ref "C18") (pin "1") (pinfunction "1_1") (pintype "passive"))
      (node (ref "C21") (pin "1") (pinfunction "1_1") (pintype "passive"))
      (node (ref "C22") (pin "1") (pinfunction "1_1") (pintype "passive"))
      (node (ref "C24") (pin "1") (pinfunction "1_1") (pintype "passive"))
      (node (ref "C25") (pin "1") (pinfunction "1_1") (pintype "passive"))
      (node (ref "C27") (pin "1") (pinfunction "1_1") (pintype "passive"))
      (node (ref "C28") (pin "1") (pinfunction "1_1") (pintype "passive"))
      (node (ref "C29") (pin "1") (pinfunction "1_1") (pintype "passive"))
      (node (ref "C30") (pin "1") (pinfunction "1_1") (pintype "passive"))
      (node (ref "C31") (pin "1") (pinfunction "1_1") (pintype "passive"))
      (node (ref "C32") (pin "1") (pinfunction "1_1") (pintype "passive"))
      (node (ref "C33") (pin "1") (pinfunction "1_1") (pintype "passive"))
      (node (ref "C34") (pin "1") (pinfunction "1_1") (pintype "passive"))
      (node (ref "C35") (pin "1") (pinfunction "1_1") (pintype "passive"))
      (node (ref "C36") (pin "1") (pinfunction "1_1") (pintype "passive"))
      (node (ref "C37") (pin "1") (pinfunction "1_1") (pintype "passive"))
      (node (ref "C38") (pin "1") (pinfunction "1_1") (pintype "passive"))
      (node (ref "C39") (pin "1") (pinfunction "1_1") (pintype "passive"))
      (node (ref "C40") (pin "1") (pinfunction "1_1") (pintype "passive"))
      (node (ref "C41") (pin "1") (pinfunction "1_1") (pintype "passive"))
      (node (ref "D1") (pin "2") (pinfunction "C_2") (pintype "passive"))
      (node (ref "D2") (pin "2") (pinfunction "C_2") (pintype "passive"))
      (node (ref "R31") (pin "2") (pinfunction "2_2") (pintype "passive"))
      (node (ref "R42") (pin "2") (pinfunction "2_2") (pintype "passive"))
      (node (ref "U1") (pin "8") (pinfunction "V+_8") (pintype "power_in"))
      (node (ref "U10") (pin "16") (pinfunction "VCC_16") (pintype "power_in"))
      (node (ref "U12") (pin "16") (pinfunction "V+_16") (pintype "power_in"))
      (node (ref "U13") (pin "16") (pinfunction "V+_16") (pintype "power_in"))
      (node (ref "U14") (pin "16") (pinfunction "V+_16") (pintype "power_in"))
      (node (ref "U15") (pin "16") (pinfunction "V+_16") (pintype "power_in"))
      (node (ref "U16") (pin "16") (pinfunction "V+_16") (pintype "power_in"))
      (node (ref "U17") (pin "16") (pinfunction "V+_16") (pintype "power_in"))
      (node (ref "U18") (pin "16") (pinfunction "V+_16") (pintype "power_in"))
      (node (ref "U19") (pin "16") (pinfunction "V+_16") (pintype "power_in"))
      (node (ref "U2") (pin "8") (pinfunction "V+_8") (pintype "power_in"))
      (node (ref "U20") (pin "16") (pinfunction "V+_16") (pintype "power_in"))
      (node (ref "U21") (pin "16") (pinfunction "V+_16") (pintype "power_in"))
      (node (ref "U22") (pin "16") (pinfunction "V+_16") (pintype "power_in"))
      (node (ref "U23") (pin "16") (pinfunction "V+_16") (pintype "power_in"))
      (node (ref "U24") (pin "16") (pinfunction "V+_16") (pintype "power_in"))
      (node (ref "U25") (pin "16") (pinfunction "V+_16") (pintype "power_in"))
      (node (ref "U3") (pin "8") (pinfunction "V+_8") (pintype "power_in"))
      (node (ref "U4") (pin "5") (pinfunction "VO_5") (pintype "passive"))
      (node (ref "U5") (pin "8") (pinfunction "V+_8") (pintype "power_in"))
      (node (ref "U7") (pin "5") (pinfunction "V+_5") (pintype "power_in"))
      (node (ref "U8") (pin "8") (pinfunction "V+_8") (pintype "power_in"))
      (node (ref "U9") (pin "8") (pinfunction "V+_8") (pintype "power_in"))
    )
    (net (code "251") (name "VA+5") (class "Default")
      (node (ref "C26") (pin "2") (pinfunction "2_2") (pintype "passive"))
      (node (ref "C8") (pin "POS") (pinfunction "POS_POS") (pintype "passive"))
      (node (ref "C9") (pin "1") (pinfunction "1_1") (pintype "passive"))
      (node (ref "L3") (pin "1") (pinfunction "1_1") (pintype "passive"))
      (node (ref "R26") (pin "1") (pinfunction "1_1") (pintype "passive"))
      (node (ref "U11") (pin "8") (pinfunction "V+_8") (pintype "power_in"))
      (node (ref "U4") (pin "1") (pinfunction "VI_1") (pintype "input"))
    )
    (net (code "252") (name "VD+1V8") (class "Default")
      (node (ref "C49") (pin "2") (pinfunction "2_2") (pintype "passive"))
      (node (ref "C51") (pin "2") (pinfunction "2_2") (pintype "passive"))
      (node (ref "C57") (pin "1") (pinfunction "1_1") (pintype "passive"))
      (node (ref "U27") (pin "13") (pinfunction "VCCINT_1_13") (pintype "power_in"))
      (node (ref "U27") (pin "63") (pinfunction "VCCINT_2_63") (pintype "power_in"))
      (node (ref "U28") (pin "5") (pinfunction "VO_5") (pintype "passive"))
    )
    (net (code "253") (name "VD+3V3") (class "Default")
      (node (ref "C42") (pin "1") (pinfunction "1_1") (pintype "passive"))
      (node (ref "C43") (pin "1") (pinfunction "1_1") (pintype "passive"))
      (node (ref "C44") (pin "1") (pinfunction "1_1") (pintype "passive"))
      (node (ref "C45") (pin "1") (pinfunction "1_1") (pintype "passive"))
      (node (ref "C48") (pin "2") (pinfunction "2_2") (pintype "passive"))
      (node (ref "C50") (pin "2") (pinfunction "2_2") (pintype "passive"))
      (node (ref "C53") (pin "1") (pinfunction "1_1") (pintype "passive"))
      (node (ref "C54") (pin "1") (pinfunction "1_1") (pintype "passive"))
      (node (ref "C55") (pin "1") (pinfunction "1_1") (pintype "passive"))
      (node (ref "CN18") (pin "4") (pinfunction "4_4") (pintype "bidirectional"))
      (node (ref "CN19") (pin "6") (pinfunction "6_6") (pintype "bidirectional"))
      (node (ref "CN19") (pin "8") (pinfunction "8_8") (pintype "bidirectional"))
      (node (ref "CN20") (pin "1") (pinfunction "1_1") (pintype "bidirectional"))
      (node (ref "R36") (pin "2") (pinfunction "2_2") (pintype "passive"))
      (node (ref "R62") (pin "2") (pinfunction "2_2") (pintype "passive"))
      (node (ref "R63") (pin "2") (pinfunction "2_2") (pintype "passive"))
      (node (ref "R66") (pin "2") (pinfunction "2_2") (pintype "passive"))
      (node (ref "R72") (pin "2") (pinfunction "2_2") (pintype "passive"))
      (node (ref "R73") (pin "2") (pinfunction "2_2") (pintype "passive"))
      (node (ref "R74") (pin "2") (pinfunction "2_2") (pintype "passive"))
      (node (ref "R75") (pin "2") (pinfunction "2_2") (pintype "passive"))
      (node (ref "R76") (pin "2") (pinfunction "2_2") (pintype "passive"))
      (node (ref "U26") (pin "5") (pinfunction "VO_5") (pintype "passive"))
      (node (ref "U27") (pin "31") (pinfunction "VCCIO1_2_31") (pintype "power_in"))
      (node (ref "U27") (pin "45") (pinfunction "VCCIO1_3_45") (pintype "power_in"))
      (node (ref "U27") (pin "59") (pinfunction "VCCIO2_1_59") (pintype "power_in"))
      (node (ref "U27") (pin "80") (pinfunction "VCCIO2_2_80") (pintype "power_in"))
      (node (ref "U27") (pin "9") (pinfunction "VCCIO1_1_9") (pintype "power_in"))
      (node (ref "U27") (pin "94") (pinfunction "VCCIO2_3_94") (pintype "power_in"))
      (node (ref "U28") (pin "1") (pinfunction "VI_1") (pintype "input"))
      (node (ref "U28") (pin "3") (pinfunction "EN_3") (pintype "input"))
      (node (ref "U29") (pin "1") (pinfunction "CONT_1") (pintype "input"))
      (node (ref "U29") (pin "20") (pinfunction "VCC_20") (pintype "power_in"))
    )
    (net (code "254") (name "VD_BAT") (class "Default")
      (node (ref "C46") (pin "POS") (pinfunction "POS_POS") (pintype "passive"))
      (node (ref "C47") (pin "1") (pinfunction "1_1") (pintype "passive"))
      (node (ref "L5") (pin "4") (pinfunction "2_4") (pintype "passive"))
      (node (ref "R23") (pin "2") (pinfunction "2_2") (pintype "passive"))
      (node (ref "R64") (pin "1") (pinfunction "1_1") (pintype "passive"))
      (node (ref "U26") (pin "1") (pinfunction "VI_1") (pintype "input"))
      (node (ref "U6") (pin "6") (pinfunction "VDD_6") (pintype "power_in"))
    )
    (net (code "255") (name "ZOUT") (class "Default")
      (node (ref "U27") (pin "21") (pinfunction "1-16_21") (pintype "bidirectional"))
      (node (ref "U9") (pin "1") (pinfunction "IN_1") (pintype "input"))
      (node (ref "U9") (pin "5") (pinfunction "IN_5") (pintype "input"))
    )
    (net (code "256") (name "unconnected-(CN7-Pad14)") (class "Default")
      (node (ref "CN7") (pin "14") (pinfunction "14_14") (pintype "bidirectional"))
    )
    (net (code "257") (name "unconnected-(CN10-Pad1)") (class "Default")
      (node (ref "CN10") (pin "1") (pinfunction "1_1") (pintype "bidirectional"))
    )
    (net (code "258") (name "unconnected-(CN11-Pad1)") (class "Default")
      (node (ref "CN11") (pin "1") (pinfunction "1_1") (pintype "bidirectional"))
    )
    (net (code "259") (name "unconnected-(CN18-Pad6)") (class "Default")
      (node (ref "CN18") (pin "6") (pinfunction "6_6") (pintype "bidirectional"))
    )
    (net (code "260") (name "unconnected-(CN18-Pad7)") (class "Default")
      (node (ref "CN18") (pin "7") (pinfunction "7_7") (pintype "bidirectional"))
    )
    (net (code "261") (name "unconnected-(CN18-Pad8)") (class "Default")
      (node (ref "CN18") (pin "8") (pinfunction "8_8") (pintype "bidirectional"))
    )
    (net (code "262") (name "unconnected-(CN19-Pad7)") (class "Default")
      (node (ref "CN19") (pin "7") (pinfunction "7_7") (pintype "bidirectional"))
    )
    (net (code "263") (name "unconnected-(CN19-Pad14)") (class "Default")
      (node (ref "CN19") (pin "14") (pinfunction "14_14") (pintype "bidirectional"))
    )
    (net (code "264") (name "unconnected-(CN20-Pad14)") (class "Default")
      (node (ref "CN20") (pin "14") (pinfunction "14_14") (pintype "bidirectional"))
    )
    (net (code "265") (name "unconnected-(SW1A-NO-Pad1)") (class "Default")
      (node (ref "SW1") (pin "1") (pinfunction "NO_1") (pintype "passive"))
    )
    (net (code "266") (name "unconnected-(SW2A-NO-Pad1)") (class "Default")
      (node (ref "SW2") (pin "1") (pinfunction "NO_1") (pintype "passive"))
    )
    (net (code "267") (name "unconnected-(SW3A-NO-Pad1)") (class "Default")
      (node (ref "SW3") (pin "1") (pinfunction "NO_1") (pintype "passive"))
    )
    (net (code "268") (name "unconnected-(SW4A-NO-Pad1)") (class "Default")
      (node (ref "SW4") (pin "1") (pinfunction "NO_1") (pintype "passive"))
    )
    (net (code "269") (name "unconnected-(U6-~{MR}-Pad3)") (class "Default")
      (node (ref "U6") (pin "3") (pinfunction "~{MR}_3") (pintype "bidirectional"))
    )
    (net (code "270") (name "unconnected-(U10-Pad2)") (class "Default")
      (node (ref "U10") (pin "2") (pinfunction "2_2") (pintype "bidirectional"))
    )
    (net (code "271") (name "unconnected-(U10D-0-Pad1)") (class "Default")
      (node (ref "U10") (pin "1") (pinfunction "0_1") (pintype "bidirectional"))
    )
    (net (code "272") (name "unconnected-(U10D-1-Pad5)") (class "Default")
      (node (ref "U10") (pin "5") (pinfunction "1_5") (pintype "bidirectional"))
    )
    (net (code "273") (name "unconnected-(U10D-3-Pad4)") (class "Default")
      (node (ref "U10") (pin "4") (pinfunction "3_4") (pintype "bidirectional"))
    )
    (net (code "274") (name "unconnected-(U10D-COM-Pad3)") (class "Default")
      (node (ref "U10") (pin "3") (pinfunction "COM_3") (pintype "bidirectional"))
    )
    (net (code "275") (name "unconnected-(U23-Pad5)") (class "Default")
      (node (ref "U23") (pin "5") (pinfunction "5_5") (pintype "bidirectional"))
    )
    (net (code "276") (name "unconnected-(U23B-2-Pad15)") (class "Default")
      (node (ref "U23") (pin "15") (pinfunction "2_15") (pintype "bidirectional"))
    )
    (net (code "277") (name "unconnected-(U23B-3-Pad12)") (class "Default")
      (node (ref "U23") (pin "12") (pinfunction "3_12") (pintype "bidirectional"))
    )
    (net (code "278") (name "unconnected-(U23B-4-Pad1)") (class "Default")
      (node (ref "U23") (pin "1") (pinfunction "4_1") (pintype "bidirectional"))
    )
    (net (code "279") (name "unconnected-(U23B-6-Pad2)") (class "Default")
      (node (ref "U23") (pin "2") (pinfunction "6_2") (pintype "bidirectional"))
    )
    (net (code "280") (name "unconnected-(U23B-7-Pad4)") (class "Default")
      (node (ref "U23") (pin "4") (pinfunction "7_4") (pintype "bidirectional"))
    )
    (net (code "281") (name "unconnected-(U25-Pad5)") (class "Default")
      (node (ref "U25") (pin "5") (pinfunction "5_5") (pintype "bidirectional"))
    )
    (net (code "282") (name "unconnected-(U25B-2-Pad15)") (class "Default")
      (node (ref "U25") (pin "15") (pinfunction "2_15") (pintype "bidirectional"))
    )
    (net (code "283") (name "unconnected-(U25B-3-Pad12)") (class "Default")
      (node (ref "U25") (pin "12") (pinfunction "3_12") (pintype "bidirectional"))
    )
    (net (code "284") (name "unconnected-(U25B-4-Pad1)") (class "Default")
      (node (ref "U25") (pin "1") (pinfunction "4_1") (pintype "bidirectional"))
    )
    (net (code "285") (name "unconnected-(U25B-6-Pad2)") (class "Default")
      (node (ref "U25") (pin "2") (pinfunction "6_2") (pintype "bidirectional"))
    )
    (net (code "286") (name "unconnected-(U25B-7-Pad4)") (class "Default")
      (node (ref "U25") (pin "4") (pinfunction "7_4") (pintype "bidirectional"))
    )
    (net (code "287") (name "unconnected-(U27B-1-19-Pad28)") (class "Default")
      (node (ref "U27") (pin "28") (pinfunction "1-19_28") (pintype "bidirectional"))
    )
    (net (code "288") (name "unconnected-(U27B-1-20-Pad29)") (class "Default")
      (node (ref "U27") (pin "29") (pinfunction "1-20_29") (pintype "bidirectional"))
    )
    (net (code "289") (name "unconnected-(U27B-1-21-Pad30)") (class "Default")
      (node (ref "U27") (pin "30") (pinfunction "1-21_30") (pintype "bidirectional"))
    )
    (net (code "290") (name "unconnected-(U27B-1-22-Pad33)") (class "Default")
      (node (ref "U27") (pin "33") (pinfunction "1-22_33") (pintype "bidirectional"))
    )
    (net (code "291") (name "unconnected-(U27B-1-23-Pad34)") (class "Default")
      (node (ref "U27") (pin "34") (pinfunction "1-23_34") (pintype "bidirectional"))
    )
    (net (code "292") (name "unconnected-(U27B-1-24-Pad35)") (class "Default")
      (node (ref "U27") (pin "35") (pinfunction "1-24_35") (pintype "bidirectional"))
    )
    (net (code "293") (name "unconnected-(U27B-1-25-Pad36)") (class "Default")
      (node (ref "U27") (pin "36") (pinfunction "1-25_36") (pintype "bidirectional"))
    )
    (net (code "294") (name "unconnected-(U27B-1-26-Pad37)") (class "Default")
      (node (ref "U27") (pin "37") (pinfunction "1-26_37") (pintype "bidirectional"))
    )
    (net (code "295") (name "unconnected-(U27B-1-27-Pad38)") (class "Default")
      (node (ref "U27") (pin "38") (pinfunction "1-27_38") (pintype "bidirectional"))
    )
    (net (code "296") (name "unconnected-(U27B-1-28-Pad39)") (class "Default")
      (node (ref "U27") (pin "39") (pinfunction "1-28_39") (pintype "bidirectional"))
    )
    (net (code "297") (name "unconnected-(U27B-1-29-Pad40)") (class "Default")
      (node (ref "U27") (pin "40") (pinfunction "1-29_40") (pintype "bidirectional"))
    )
    (net (code "298") (name "unconnected-(U27B-1-30-Pad41)") (class "Default")
      (node (ref "U27") (pin "41") (pinfunction "1-30_41") (pintype "bidirectional"))
    )
    (net (code "299") (name "unconnected-(U27B-1-31-Pad42)") (class "Default")
      (node (ref "U27") (pin "42") (pinfunction "1-31_42") (pintype "bidirectional"))
    )
    (net (code "300") (name "unconnected-(U27B-1-34-Pad47)") (class "Default")
      (node (ref "U27") (pin "47") (pinfunction "1-34_47") (pintype "bidirectional"))
    )
    (net (code "301") (name "unconnected-(U27B-1-35-Pad48)") (class "Default")
      (node (ref "U27") (pin "48") (pinfunction "1-35_48") (pintype "bidirectional"))
    )
    (net (code "302") (name "unconnected-(U27B-1-36-Pad49)") (class "Default")
      (node (ref "U27") (pin "49") (pinfunction "1-36_49") (pintype "bidirectional"))
    )
    (net (code "303") (name "unconnected-(U27B-1-37-Pad50)") (class "Default")
      (node (ref "U27") (pin "50") (pinfunction "1-37_50") (pintype "bidirectional"))
    )
    (net (code "304") (name "unconnected-(U27B-2-9{slash}CLK2-Pad62)") (class "Default")
      (node (ref "U27") (pin "62") (pinfunction "2-9/CLK2_62") (pintype "bidirectional"))
    )
    (net (code "305") (name "unconnected-(U27B-2-12-Pad67)") (class "Default")
      (node (ref "U27") (pin "67") (pinfunction "2-12_67") (pintype "bidirectional"))
    )
    (net (code "306") (name "unconnected-(U27B-2-13-Pad68)") (class "Default")
      (node (ref "U27") (pin "68") (pinfunction "2-13_68") (pintype "bidirectional"))
    )
    (net (code "307") (name "unconnected-(U27B-2-14-Pad69)") (class "Default")
      (node (ref "U27") (pin "69") (pinfunction "2-14_69") (pintype "bidirectional"))
    )
    (net (code "308") (name "unconnected-(U27B-2-21-Pad76)") (class "Default")
      (node (ref "U27") (pin "76") (pinfunction "2-21_76") (pintype "bidirectional"))
    )
    (net (code "309") (name "unconnected-(U27B-2-22-Pad77)") (class "Default")
      (node (ref "U27") (pin "77") (pinfunction "2-22_77") (pintype "bidirectional"))
    )
    (net (code "310") (name "unconnected-(U27B-2-23-Pad78)") (class "Default")
      (node (ref "U27") (pin "78") (pinfunction "2-23_78") (pintype "bidirectional"))
    )
    (net (code "311") (name "unconnected-(U27B-2-24-Pad81)") (class "Default")
      (node (ref "U27") (pin "81") (pinfunction "2-24_81") (pintype "bidirectional"))
    )
    (net (code "312") (name "unconnected-(U27B-2-25-Pad82)") (class "Default")
      (node (ref "U27") (pin "82") (pinfunction "2-25_82") (pintype "bidirectional"))
    )
    (net (code "313") (name "unconnected-(U27B-2-26-Pad83)") (class "Default")
      (node (ref "U27") (pin "83") (pinfunction "2-26_83") (pintype "bidirectional"))
    )
    (net (code "314") (name "unconnected-(U27B-2-27-Pad84)") (class "Default")
      (node (ref "U27") (pin "84") (pinfunction "2-27_84") (pintype "bidirectional"))
    )
    (net (code "315") (name "unconnected-(U27B-2-28-Pad85)") (class "Default")
      (node (ref "U27") (pin "85") (pinfunction "2-28_85") (pintype "bidirectional"))
    )
    (net (code "316") (name "unconnected-(U27B-2-29-Pad86)") (class "Default")
      (node (ref "U27") (pin "86") (pinfunction "2-29_86") (pintype "bidirectional"))
    )
    (net (code "317") (name "unconnected-(U27B-2-30-Pad87)") (class "Default")
      (node (ref "U27") (pin "87") (pinfunction "2-30_87") (pintype "bidirectional"))
    )
    (net (code "318") (name "unconnected-(U27B-2-31-Pad88)") (class "Default")
      (node (ref "U27") (pin "88") (pinfunction "2-31_88") (pintype "bidirectional"))
    )
    (net (code "319") (name "unconnected-(U27B-2-32-Pad89)") (class "Default")
      (node (ref "U27") (pin "89") (pinfunction "2-32_89") (pintype "bidirectional"))
    )
    (net (code "320") (name "unconnected-(U27B-2-33-Pad90)") (class "Default")
      (node (ref "U27") (pin "90") (pinfunction "2-33_90") (pintype "bidirectional"))
    )
    (net (code "321") (name "unconnected-(U27B-2-34-Pad91)") (class "Default")
      (node (ref "U27") (pin "91") (pinfunction "2-34_91") (pintype "bidirectional"))
    )
    (net (code "322") (name "unconnected-(U27B-2-35-Pad92)") (class "Default")
      (node (ref "U27") (pin "92") (pinfunction "2-35_92") (pintype "bidirectional"))
    )
    (net (code "323") (name "unconnected-(U27B-2-36-Pad95)") (class "Default")
      (node (ref "U27") (pin "95") (pinfunction "2-36_95") (pintype "bidirectional"))
    )
    (net (code "324") (name "unconnected-(U27B-2-37-Pad96)") (class "Default")
      (node (ref "U27") (pin "96") (pinfunction "2-37_96") (pintype "bidirectional"))
    )
    (net (code "325") (name "unconnected-(U27B-2-38-Pad97)") (class "Default")
      (node (ref "U27") (pin "97") (pinfunction "2-38_97") (pintype "bidirectional"))
    )
    (net (code "326") (name "unconnected-(U27B-2-39-Pad98)") (class "Default")
      (node (ref "U27") (pin "98") (pinfunction "2-39_98") (pintype "bidirectional"))
    )
    (net (code "327") (name "unconnected-(U27B-2-40-Pad99)") (class "Default")
      (node (ref "U27") (pin "99") (pinfunction "2-40_99") (pintype "bidirectional"))
    )
    (net (code "328") (name "unconnected-(U27B-2-41-Pad100)") (class "Default")
      (node (ref "U27") (pin "100") (pinfunction "2-41_100") (pintype "bidirectional"))
    )
    (net (code "329") (name "unconnected-(U29A-Y3-Pad16)") (class "Default")
      (node (ref "U29") (pin "16") (pinfunction "Y3_16") (pintype "output"))
    )
    (net (code "330") (name "unconnected-(U29A-Y4-Pad15)") (class "Default")
      (node (ref "U29") (pin "15") (pinfunction "Y4_15") (pintype "output"))
    )
    (net (code "331") (name "~{CS0}") (class "Default")
      (node (ref "U12") (pin "6") (pinfunction "EN_6") (pintype "input"))
      (node (ref "U18") (pin "6") (pinfunction "EN_6") (pintype "input"))
      (node (ref "U27") (pin "2") (pinfunction "1-1_2") (pintype "bidirectional"))
    )
    (net (code "332") (name "~{CS1}") (class "Default")
      (node (ref "U14") (pin "6") (pinfunction "EN_6") (pintype "input"))
      (node (ref "U20") (pin "6") (pinfunction "EN_6") (pintype "input"))
      (node (ref "U27") (pin "3") (pinfunction "1-2_3") (pintype "bidirectional"))
    )
    (net (code "333") (name "~{CS2}") (class "Default")
      (node (ref "U16") (pin "6") (pinfunction "EN_6") (pintype "input"))
      (node (ref "U22") (pin "6") (pinfunction "EN_6") (pintype "input"))
      (node (ref "U27") (pin "4") (pinfunction "1-3_4") (pintype "bidirectional"))
    )
    (net (code "334") (name "~{CS3}") (class "Default")
      (node (ref "U17") (pin "6") (pinfunction "EN_6") (pintype "input"))
      (node (ref "U24") (pin "6") (pinfunction "EN_6") (pintype "input"))
      (node (ref "U27") (pin "5") (pinfunction "1-4_5") (pintype "bidirectional"))
    )
    (net (code "335") (name "~{CS4}") (class "Default")
      (node (ref "U13") (pin "6") (pinfunction "EN_6") (pintype "input"))
      (node (ref "U19") (pin "6") (pinfunction "EN_6") (pintype "input"))
      (node (ref "U27") (pin "6") (pinfunction "1-5_6") (pintype "bidirectional"))
    )
    (net (code "336") (name "~{CS5}") (class "Default")
      (node (ref "U15") (pin "6") (pinfunction "EN_6") (pintype "input"))
      (node (ref "U21") (pin "6") (pinfunction "EN_6") (pintype "input"))
      (node (ref "U27") (pin "7") (pinfunction "1-6_7") (pintype "bidirectional"))
    )
    (net (code "337") (name "~{CS6}") (class "Default")
      (node (ref "U23") (pin "6") (pinfunction "EN_6") (pintype "input"))
      (node (ref "U25") (pin "6") (pinfunction "EN_6") (pintype "input"))
      (node (ref "U27") (pin "8") (pinfunction "1-7_8") (pintype "bidirectional"))
    )
    (net (code "338") (name "~{LOW_BAT}") (class "Default")
      (node (ref "CN20") (pin "3") (pinfunction "3_3") (pintype "bidirectional"))
      (node (ref "R36") (pin "1") (pinfunction "1_1") (pintype "passive"))
      (node (ref "U27") (pin "12") (pinfunction "1-8/CLK0_12") (pintype "bidirectional"))
      (node (ref "U6") (pin "1") (pinfunction "~{RESET}_1") (pintype "output"))
    )
    (net (code "339") (name "~{OE}") (class "Default")
      (node (ref "U27") (pin "17") (pinfunction "1-12_17") (pintype "bidirectional"))
    )
  )
)
